# Talos_ES_CTRL_Schematics.net
KiCad netlist of a schematic drawn in EasyEDA
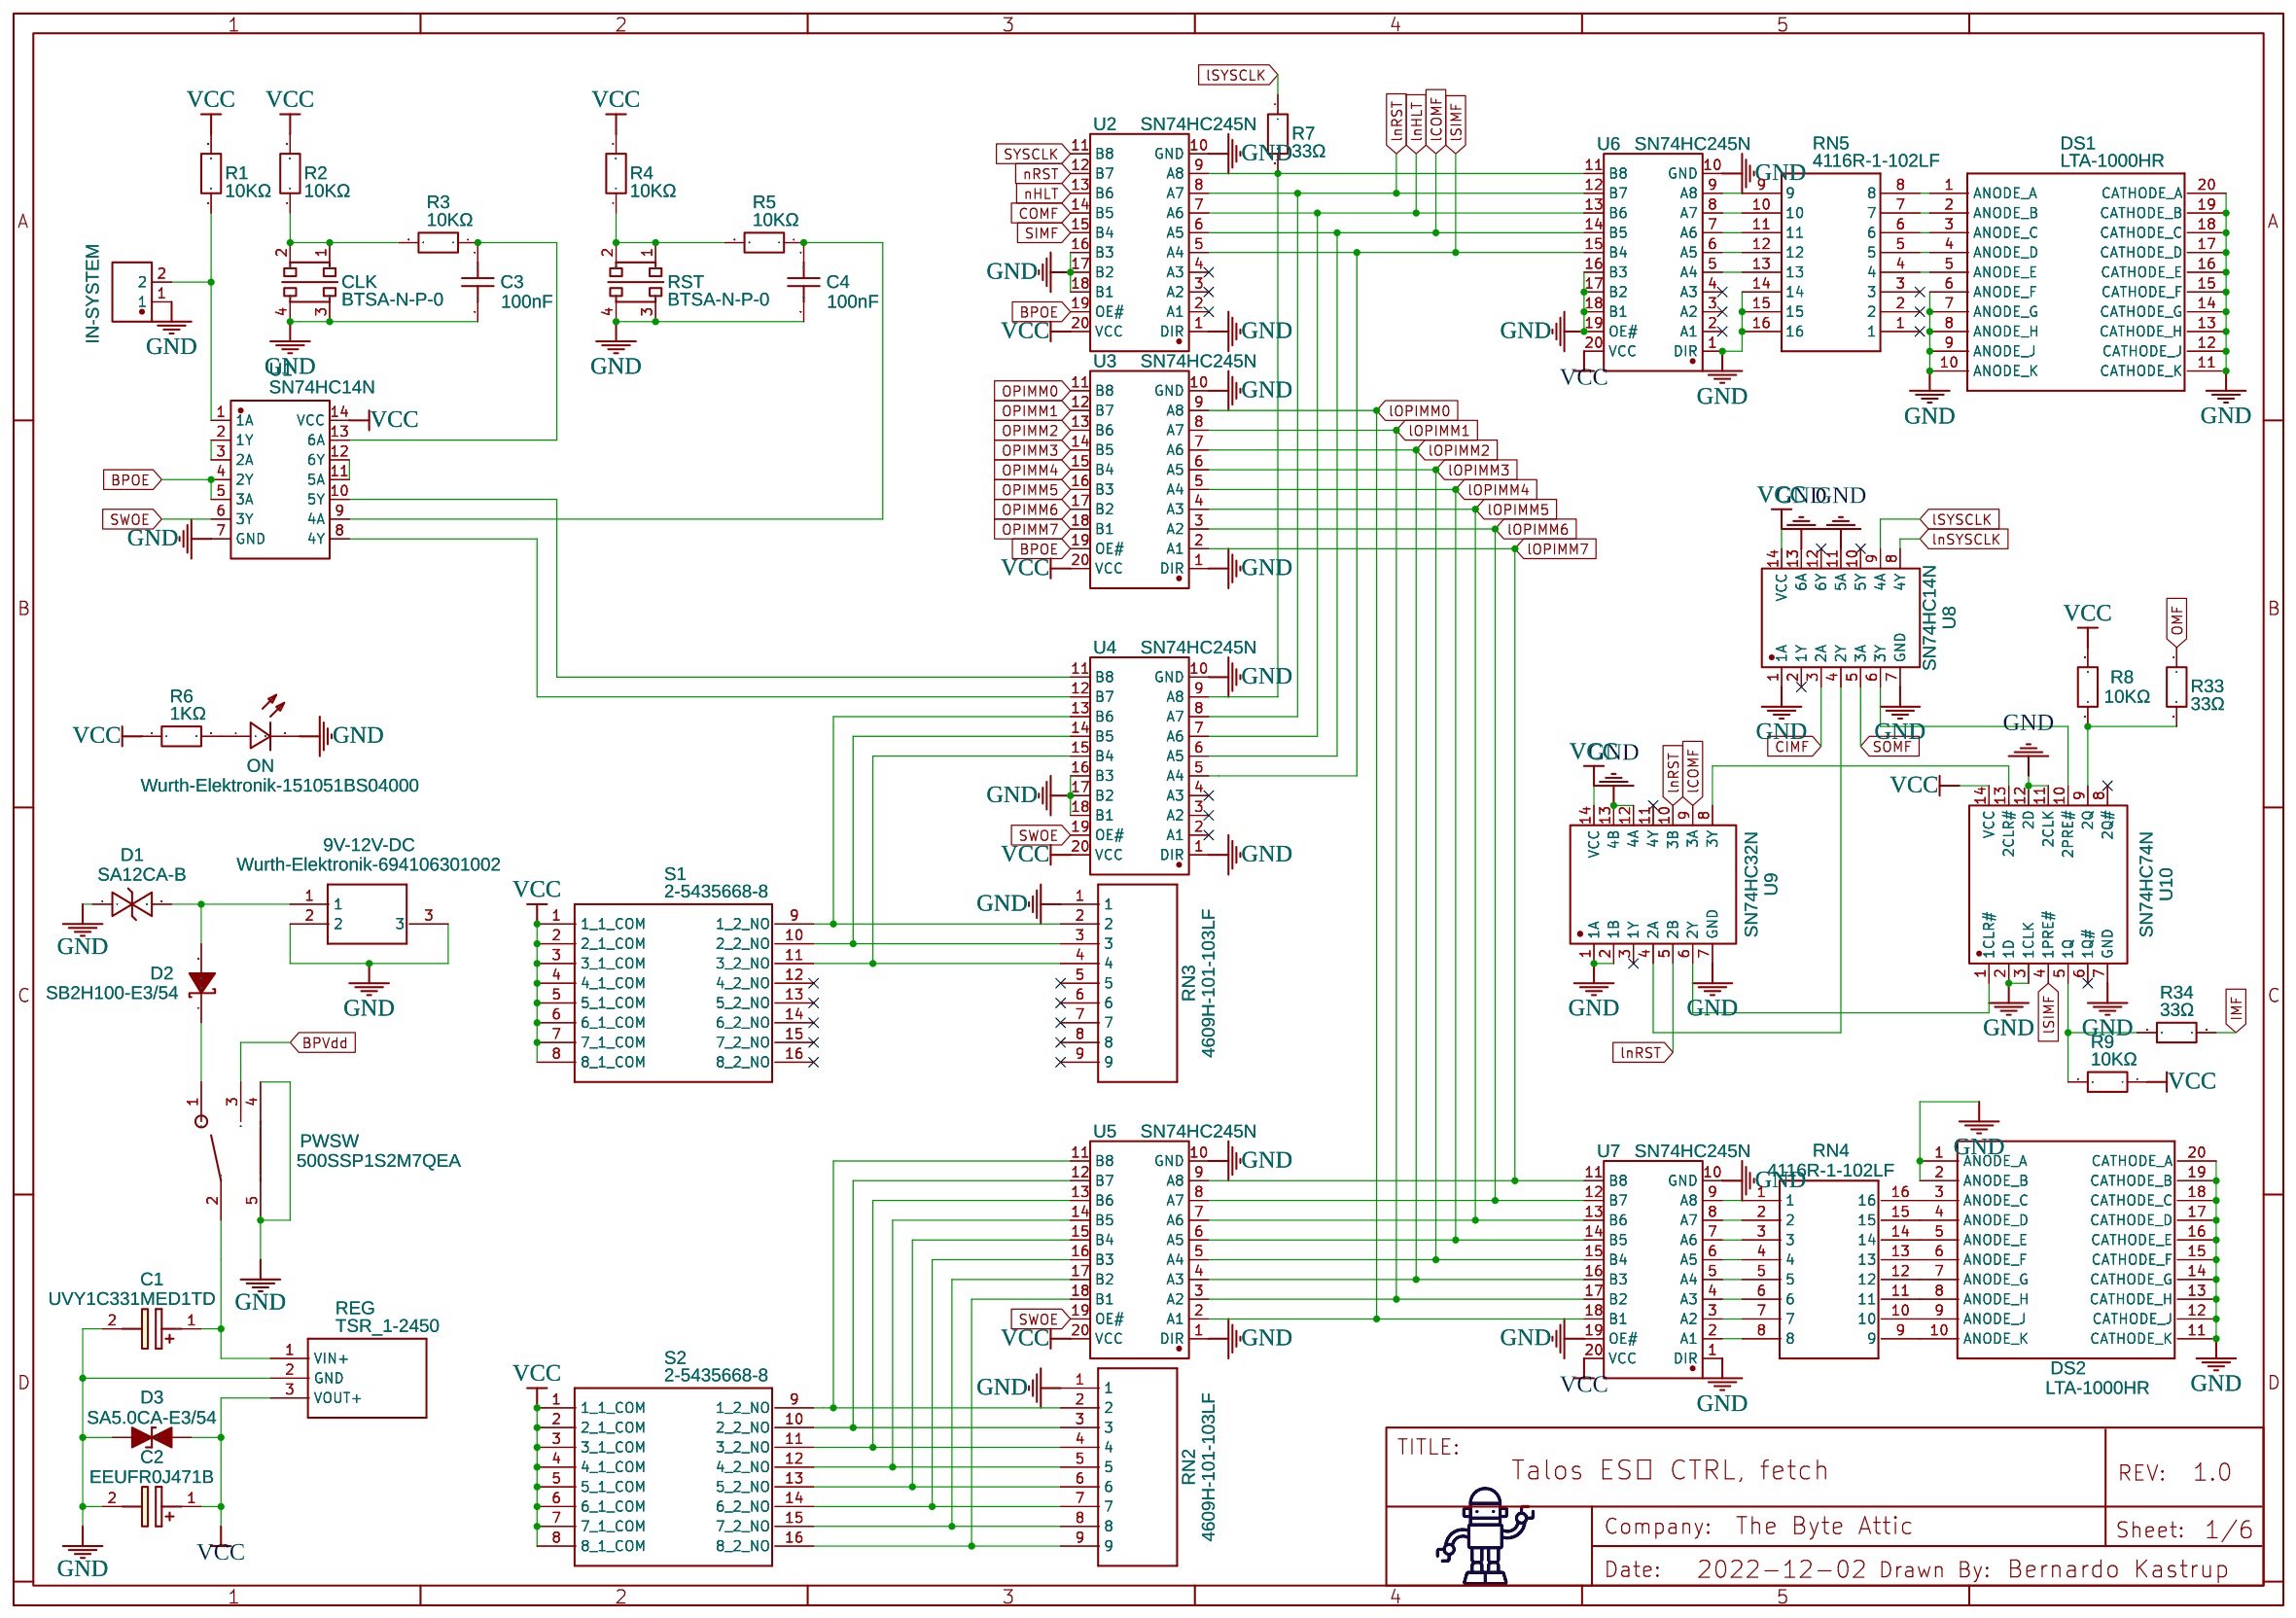
[diagram p0: FETCH]
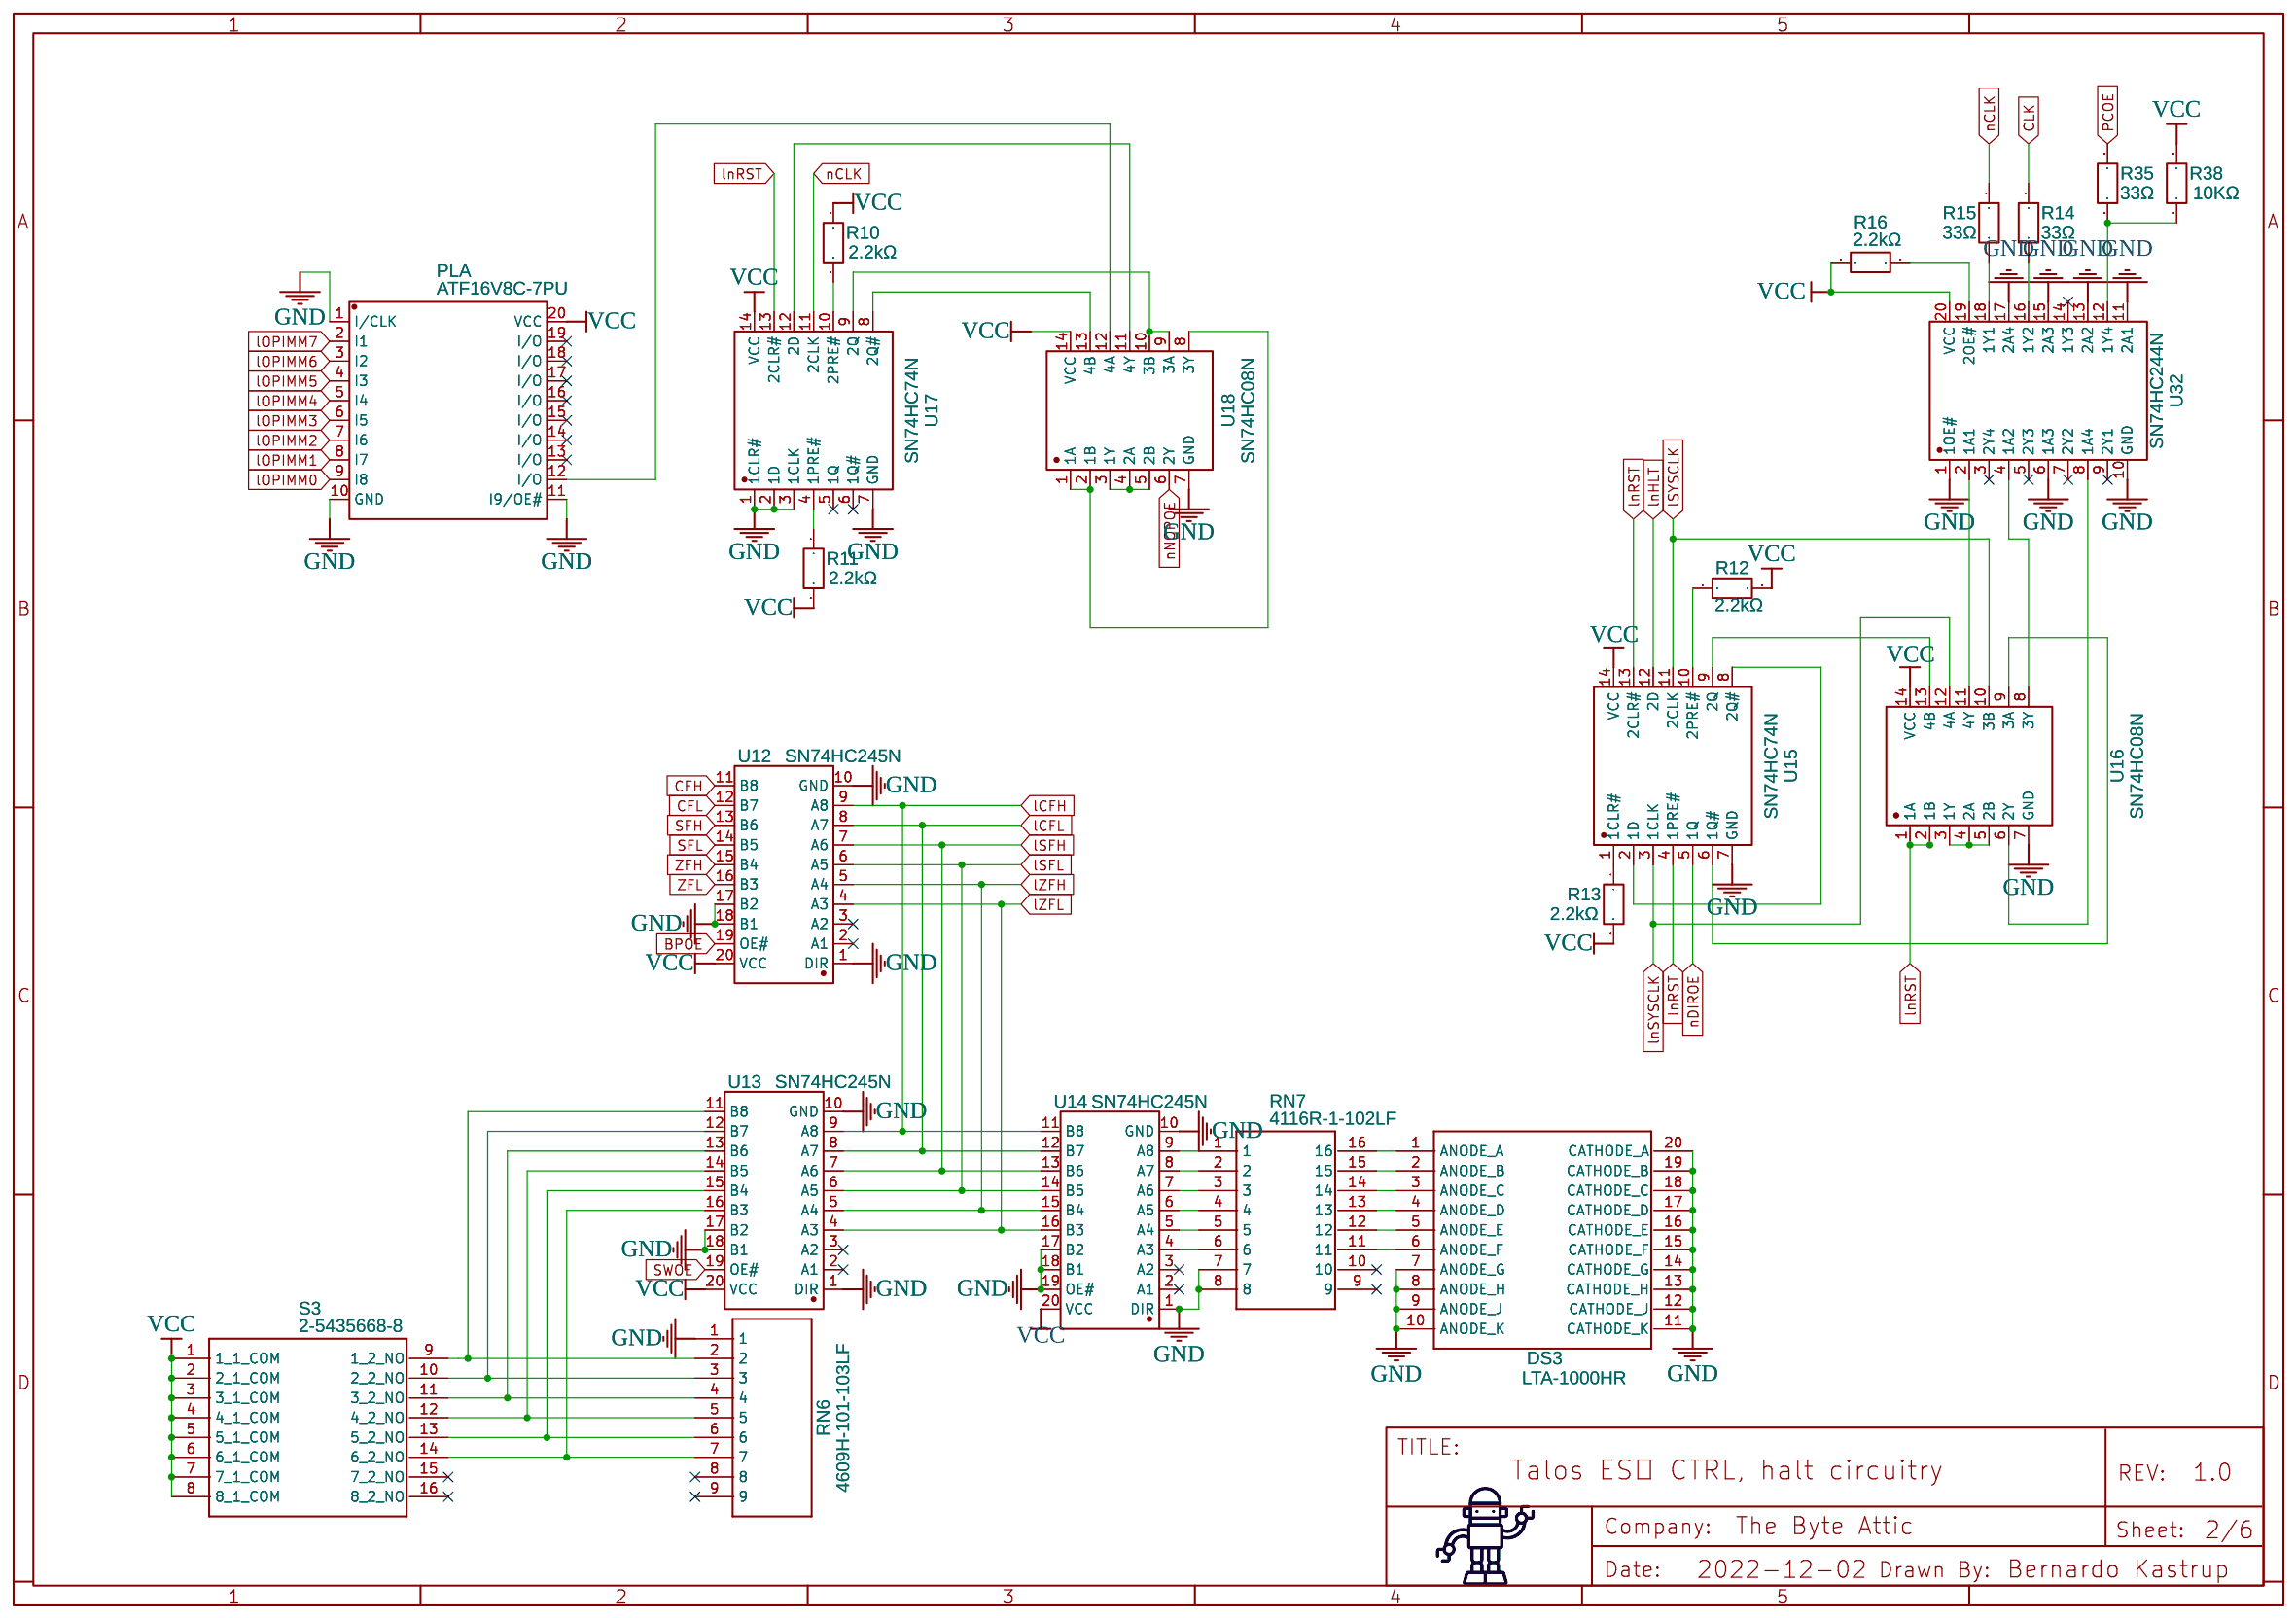
[diagram p1: HALT]
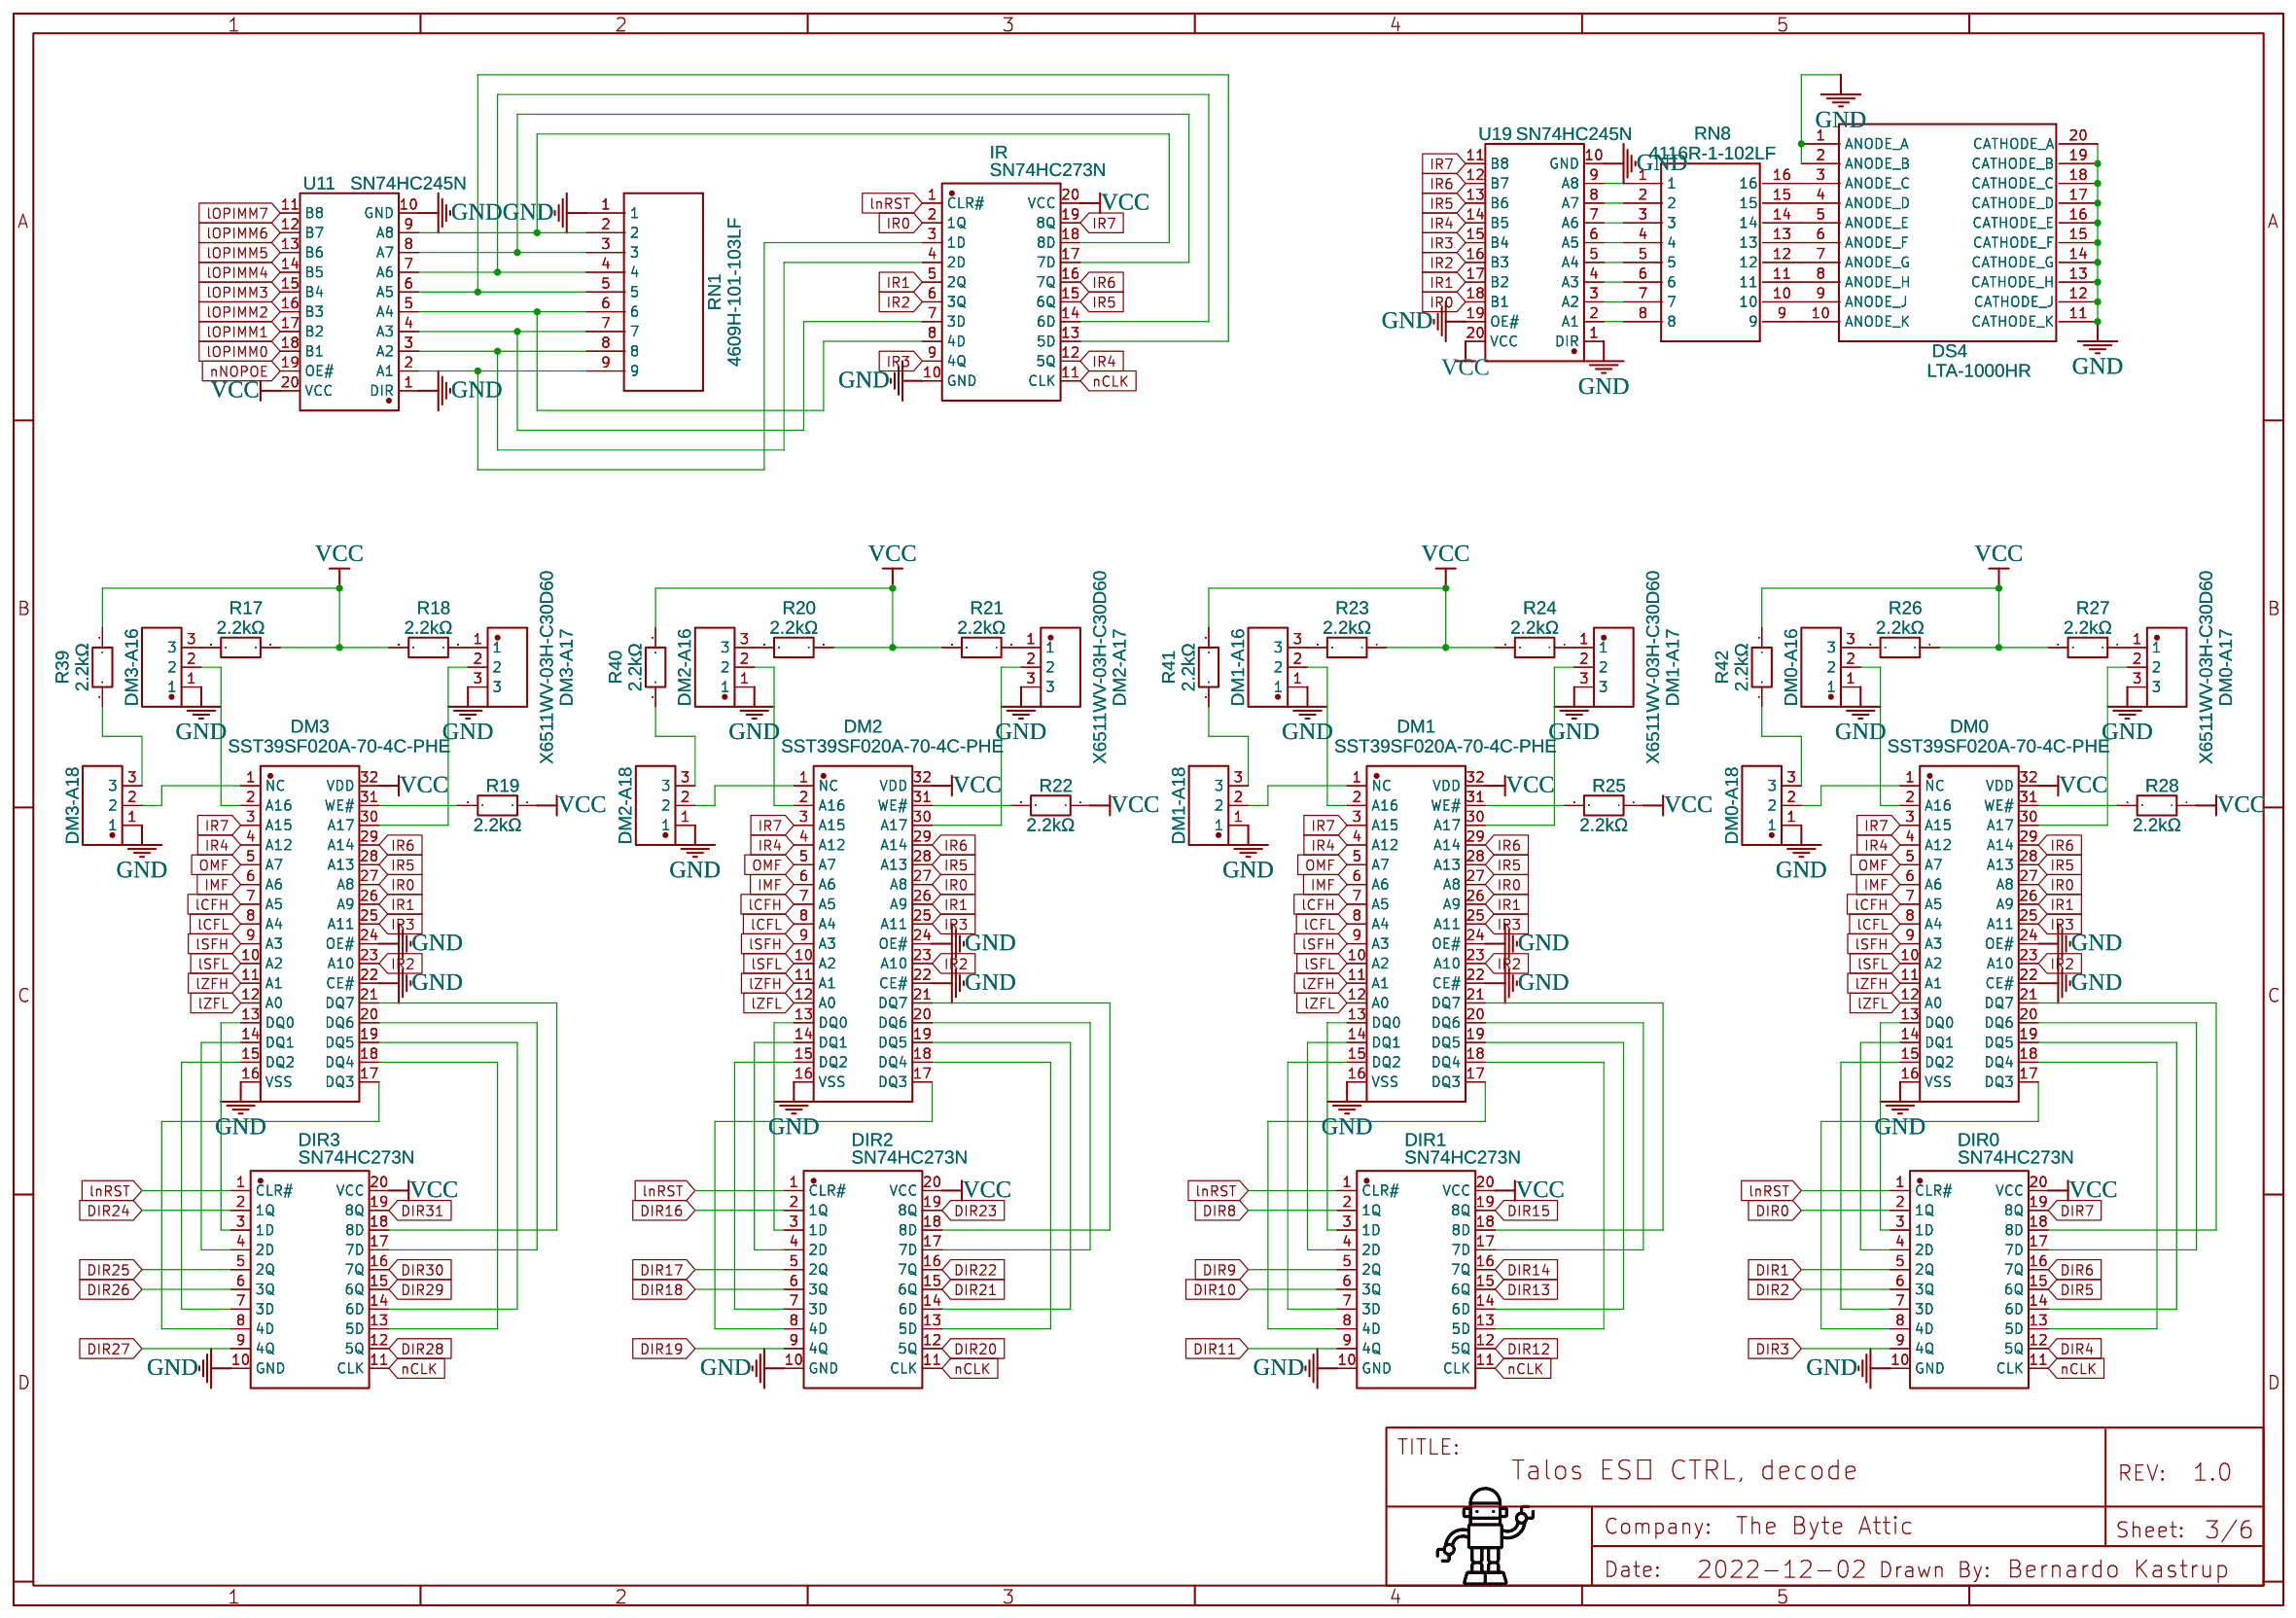
[diagram p2: DECODE]
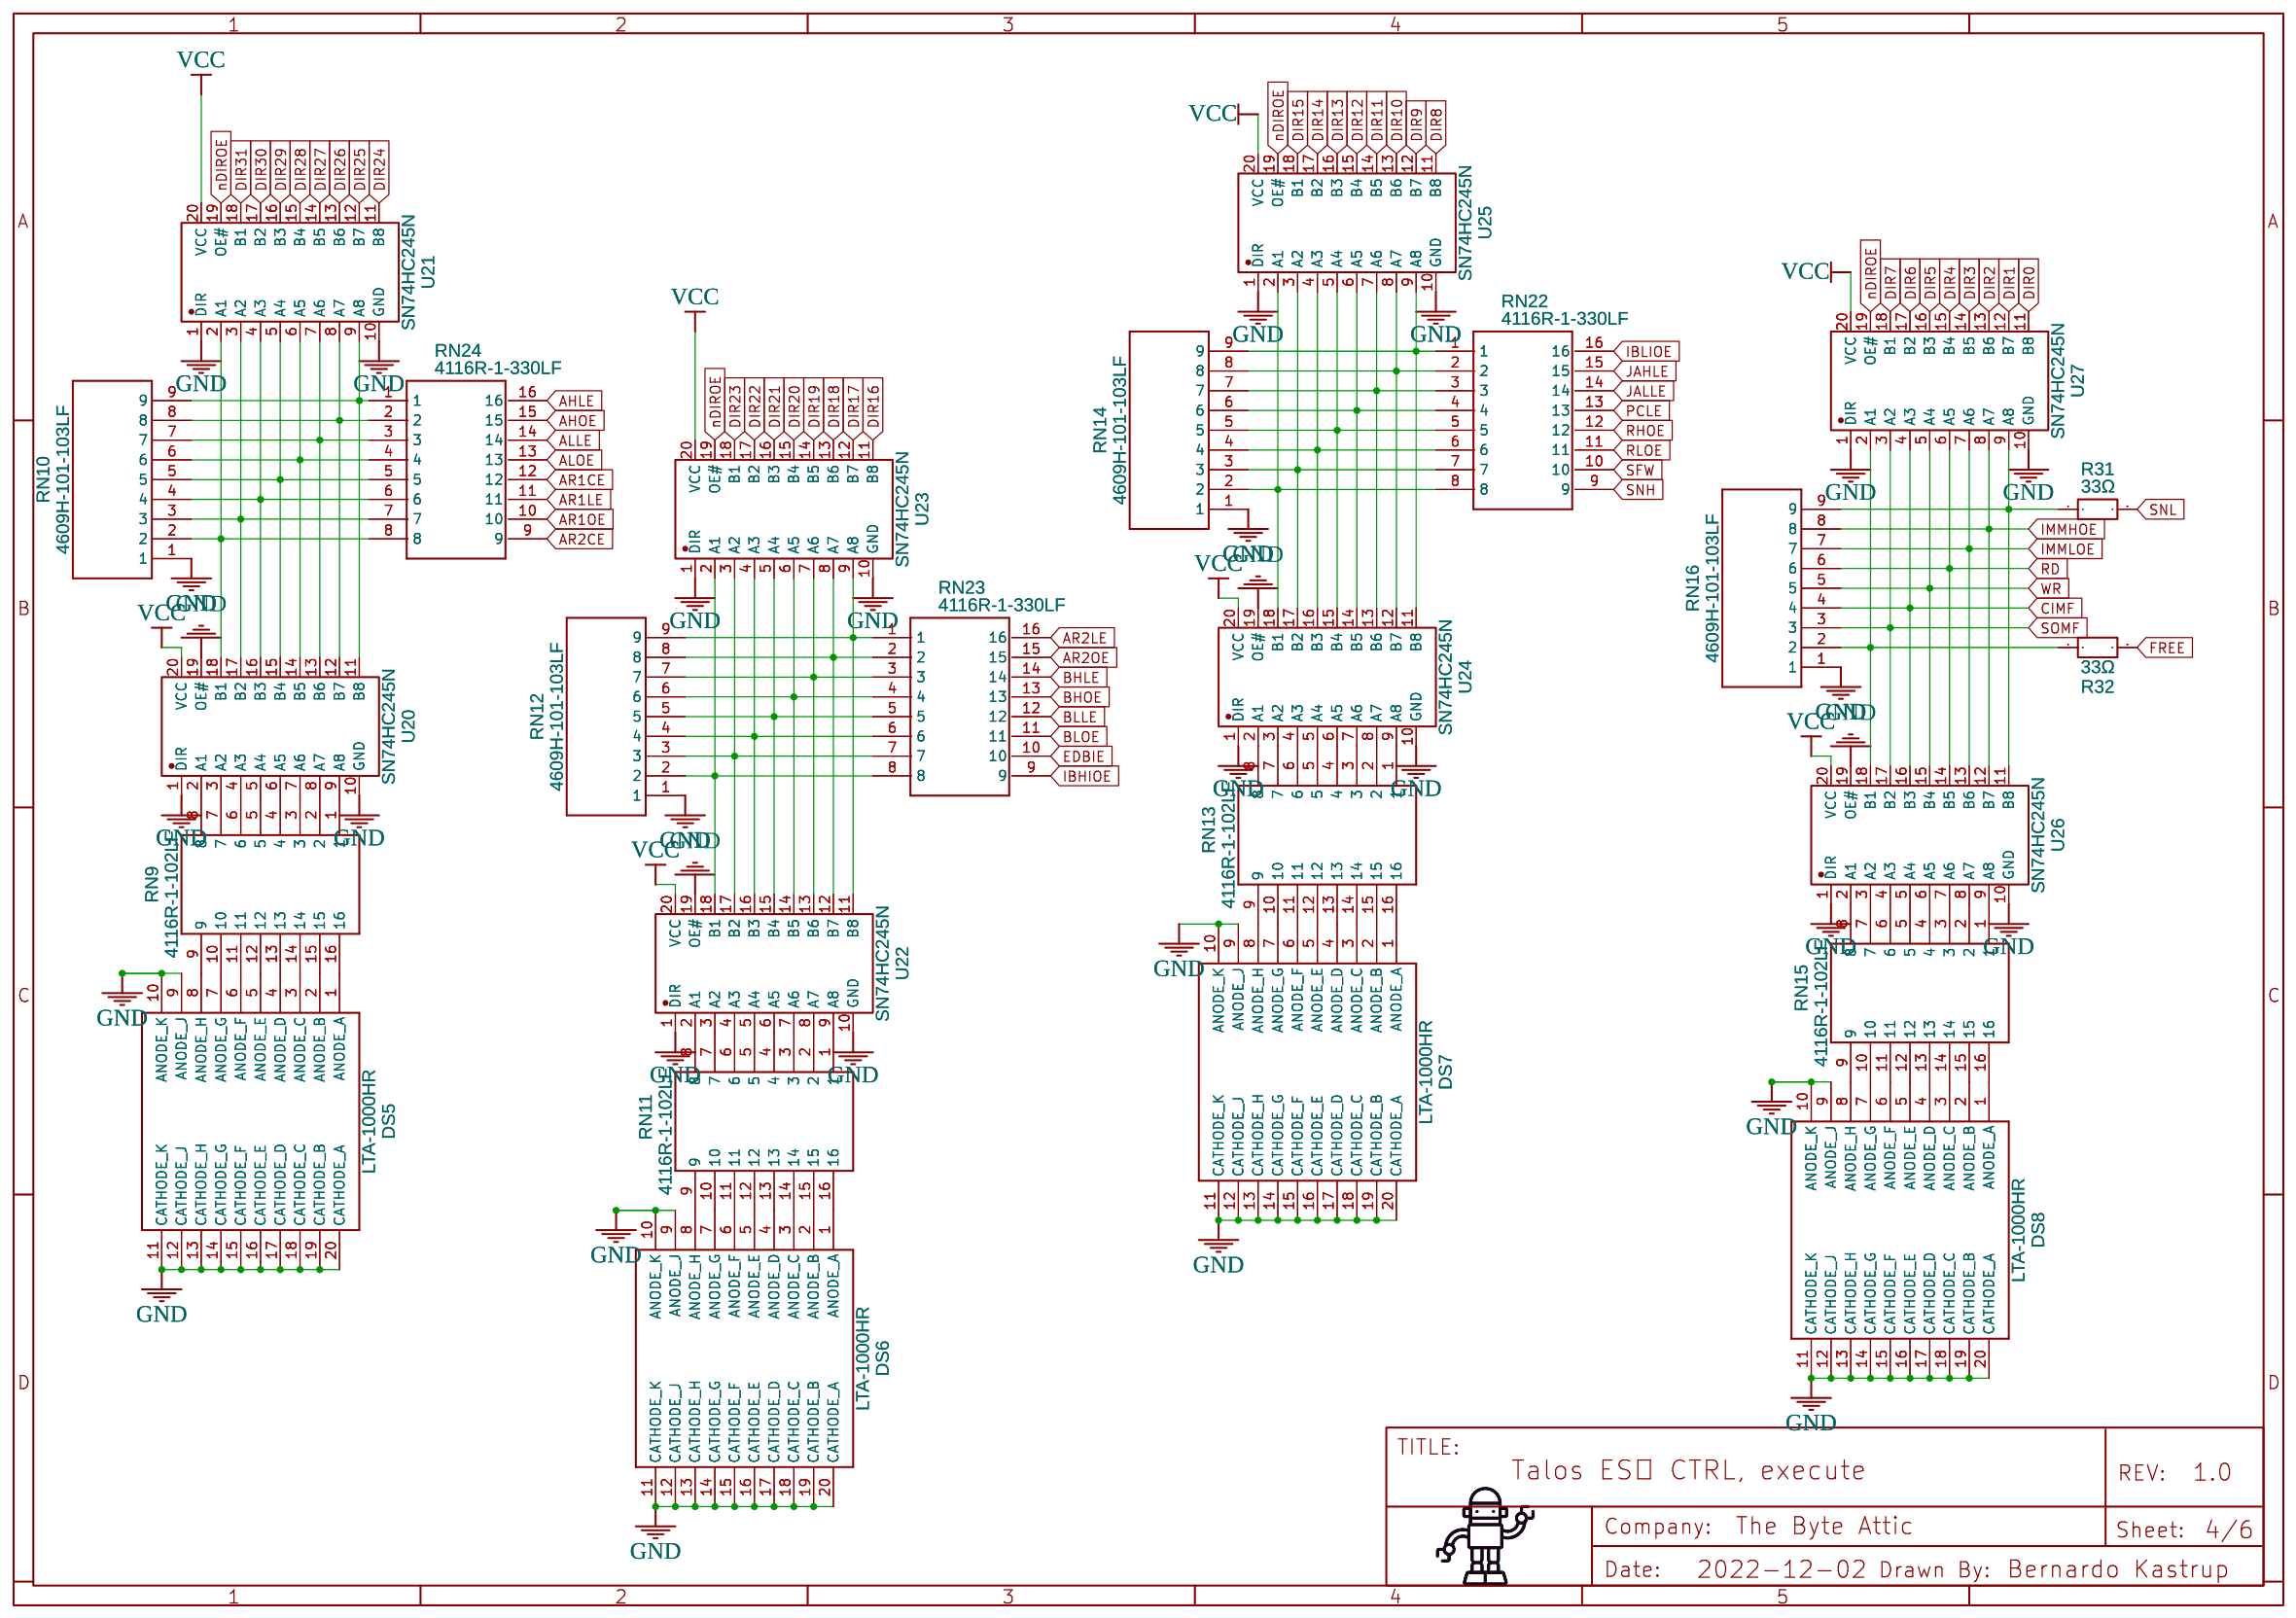
[diagram p3: EXECUTE]
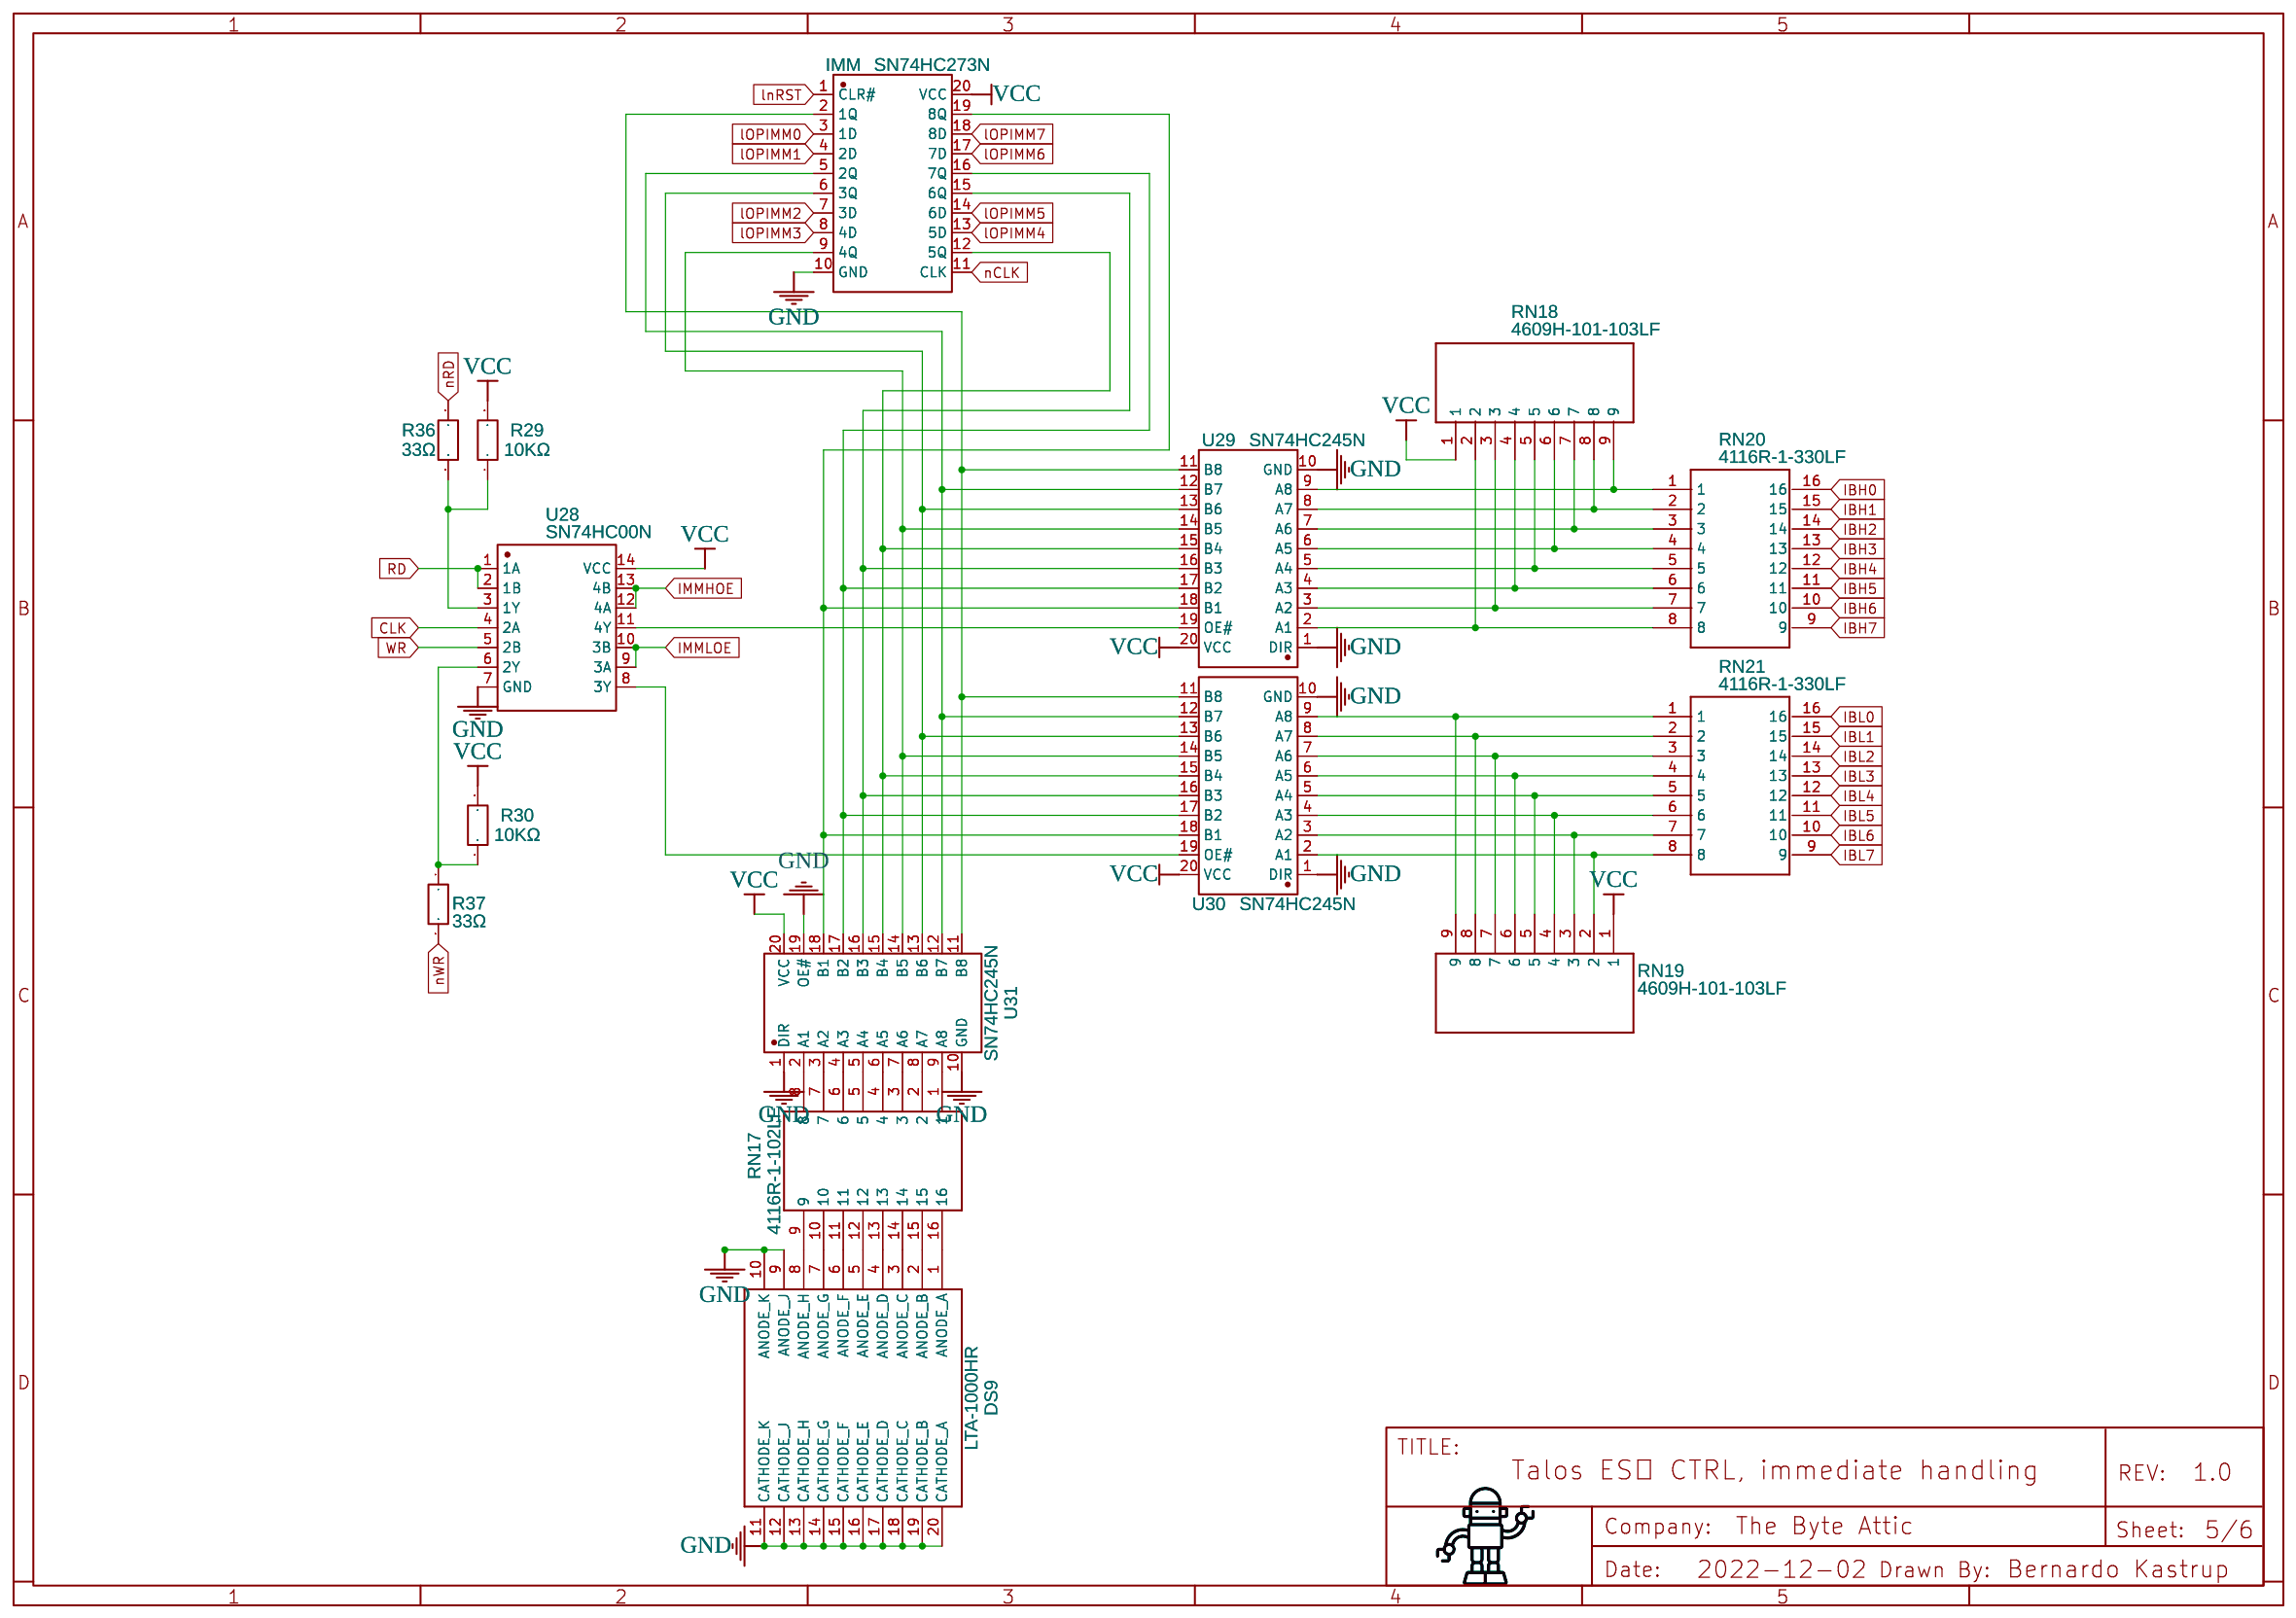
[diagram p4: IMMEDIATE]
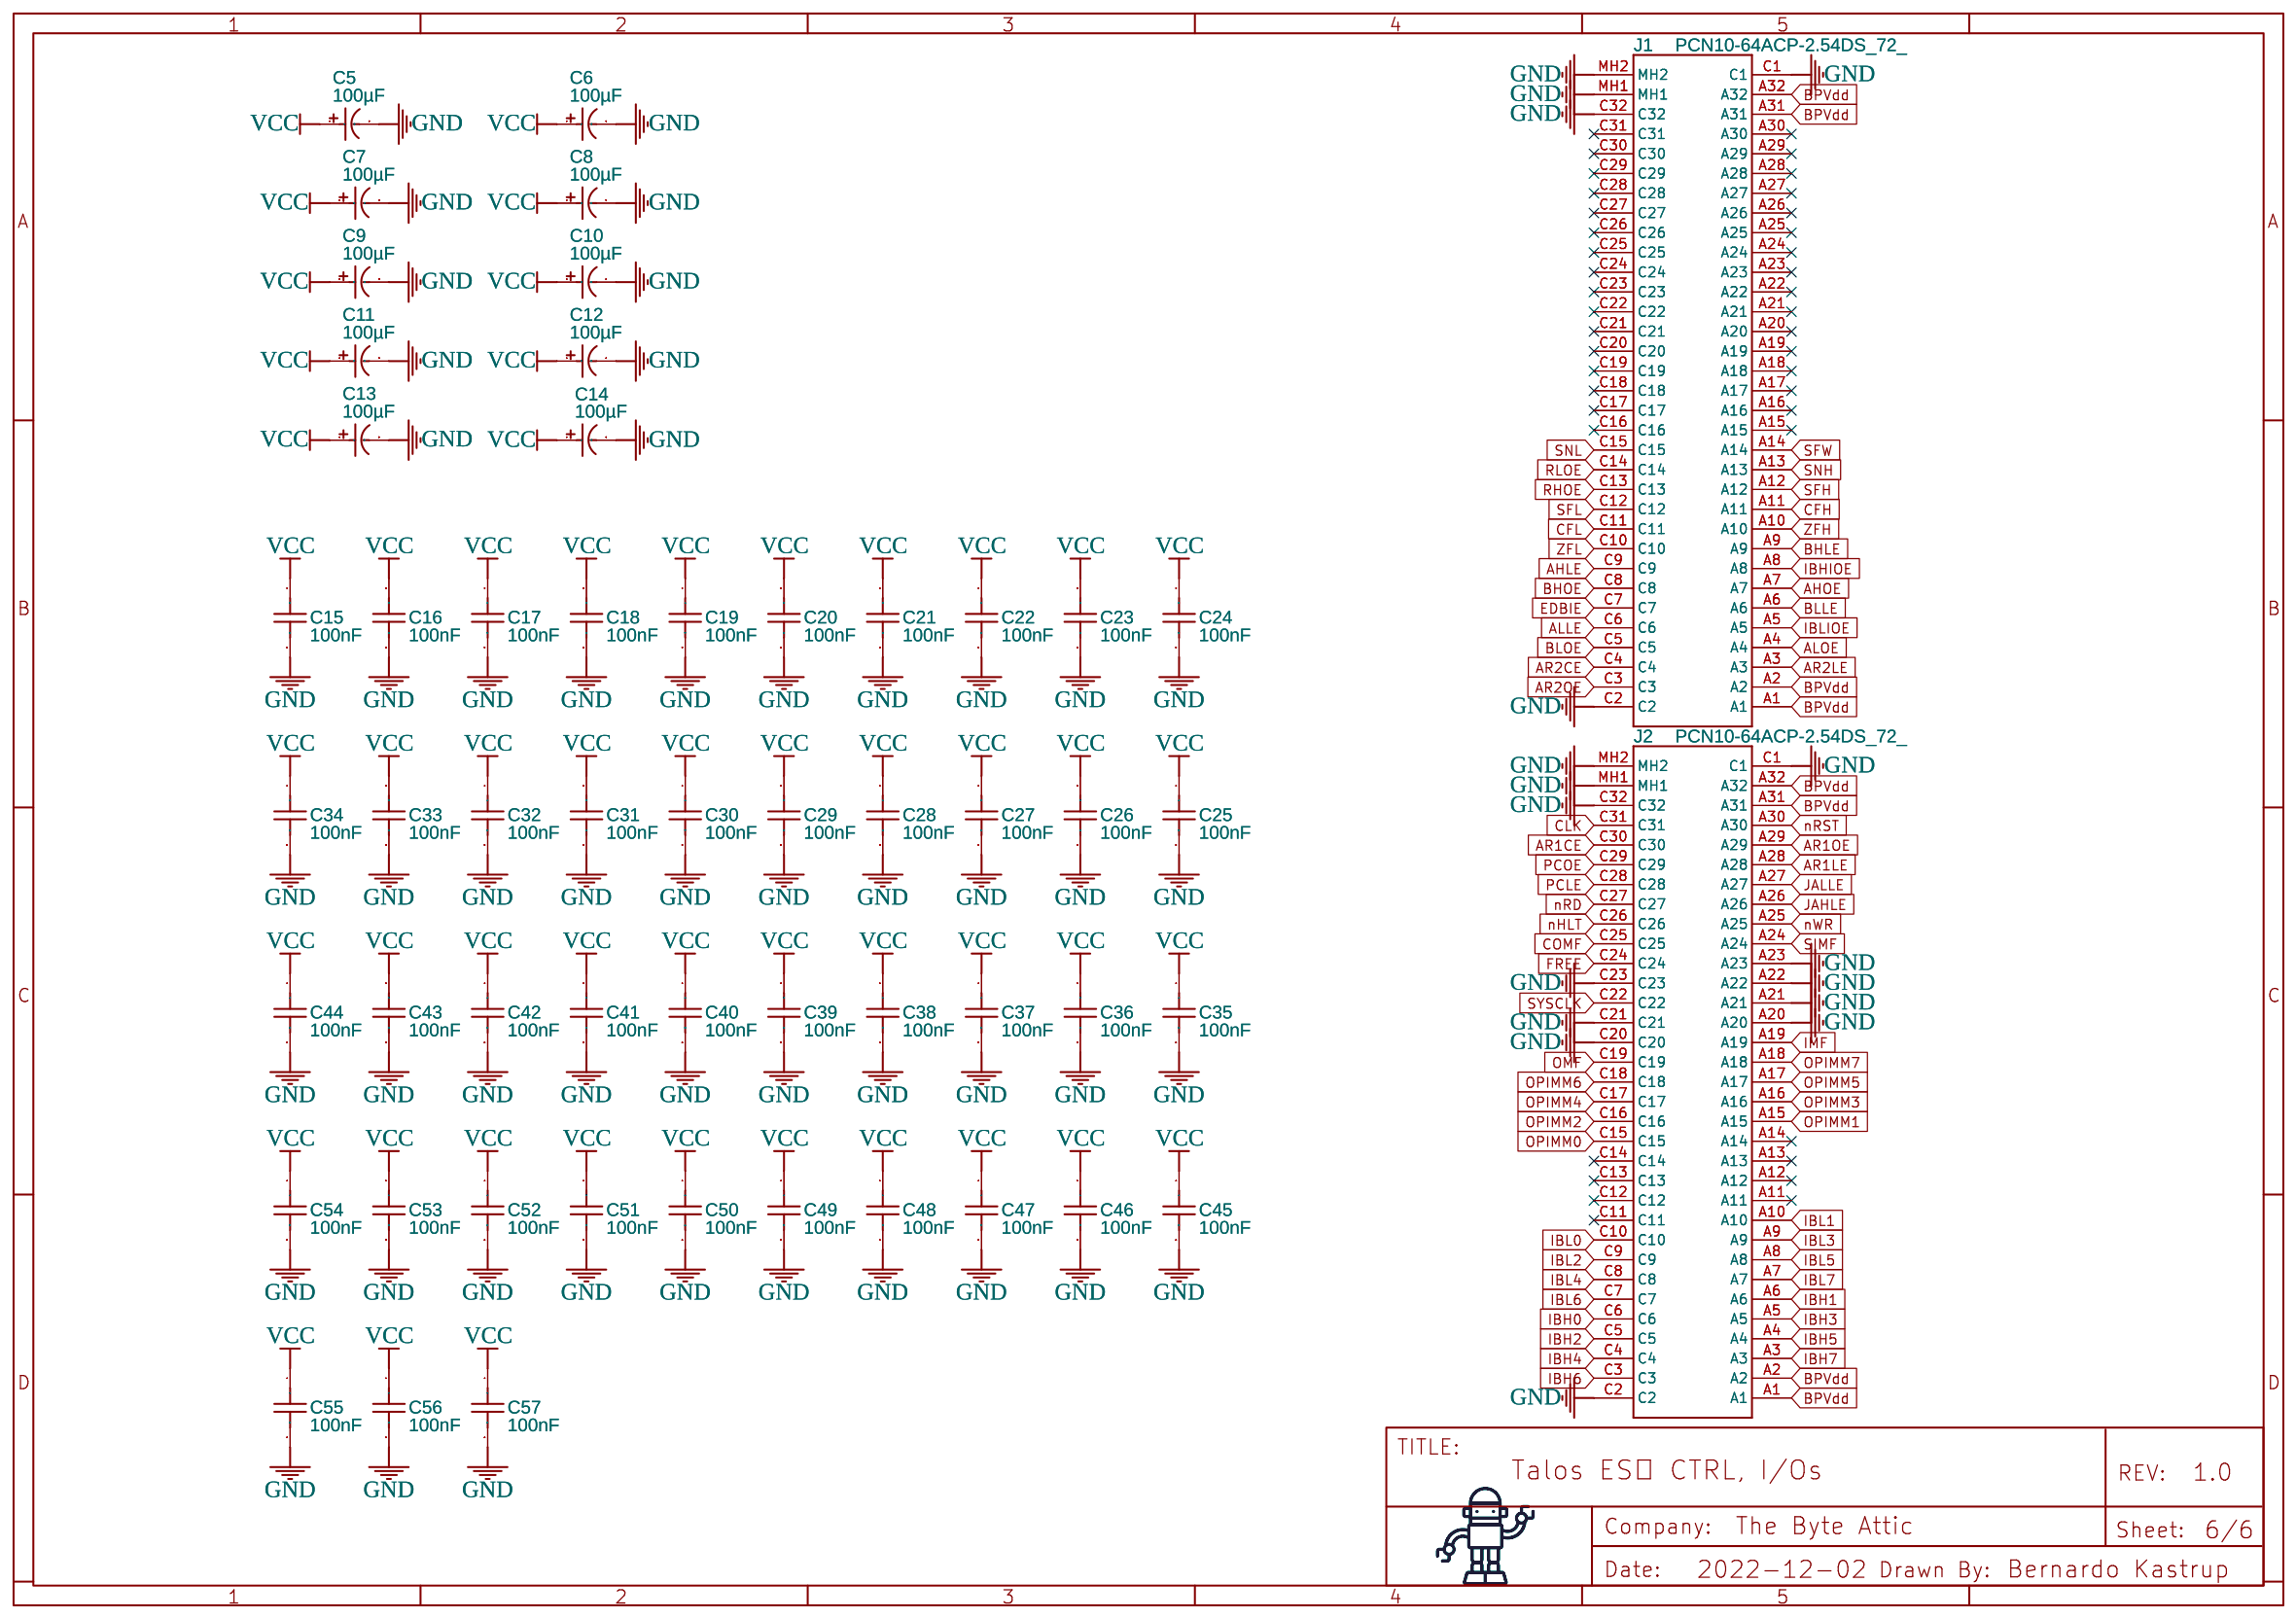
[diagram p5: I/O]

(export (version "E")
  (design (tool "Eeschema 10.0.6"))
  (components
    (comp (ref "9V-12V-DC")
      (value "Wurth-Elektronik-694106301002")
      (libsource (lib "") (part "KLDX-0202-AP-LT"))
    )
    (comp (ref "C1")
      (value "UVY1C331MED1TD")
      (fields (field (name "BOM_Supplier Part") "647-UVY1C331MED1TD"))
      (libsource (lib "") (part "EEUFR0J471B"))
    )
    (comp (ref "C2")
      (value "EEUFR0J471B")
      (fields
        (field (name "BOM_Manufacturer Part") "EEU-FR0J471B")
        (field (name "BOM_Supplier Part") "667-EEU-FR0J471B")
      )
      (libsource (lib "") (part "EEUFR0J471B"))
    )
    (comp (ref "C3")
      (value "100nF")
      (fields
        (field (name "BOM_Manufacturer Part") "K104M15X7RF5TH5")
        (field (name "BOM_Supplier Part") "C499573")
      )
      (libsource (lib "") (part "K104M15X7RF5TH5"))
    )
    (comp (ref "C4")
      (value "100nF")
      (fields
        (field (name "BOM_Manufacturer Part") "K104M15X7RF5TH5")
        (field (name "BOM_Supplier Part") "C499573")
      )
      (libsource (lib "") (part "K104M15X7RF5TH5"))
    )
    (comp (ref "CLK")
      (value "BTSA-N-P-0")
      (fields (field (name "BOM_Supplier Part") "C2693689"))
      (libsource (lib "") (part "BTSA-N-P-0_1"))
    )
    (comp (ref "D1")
      (value "SA12CA-B")
      (fields (field (name "BOM_Supplier Part") "C1666306"))
      (libsource (lib "") (part "SA12CA-B"))
    )
    (comp (ref "D2")
      (value "SB2H100-E3/54")
      (fields (field (name "BOM_Manufacturer Part") "1N5818G") (field (name "BOM_Supplier Part") "C232462"))
      (libsource (lib "") (part "1N5818G"))
    )
    (comp (ref "D3")
      (value "SA5.0CA-E3/54")
      (fields (field (name "BOM_Supplier Part") "C1973200"))
      (libsource (lib "") (part "SA5.0CA-E3/54"))
    )
    (comp (ref "DS1") (value "LTA-1000HR") (libsource (lib "") (part "LTA-1000HR")))
    (comp (ref "DS2") (value "LTA-1000HR") (libsource (lib "") (part "LTA-1000HR")))
    (comp (ref "IN-SYSTEM")
      (value "22-28-4020")
      (fields (field (name "BOM_Supplier Part") "C234182"))
      (libsource (lib "") (part "22-28-4020"))
    )
    (comp (ref "ON")
      (value "Wurth-Elektronik-151051BS04000")
      (fields
        (field (name "BOM_Manufacturer Part") "TJ-L3FYWGHRMFCSFLC2R-A5")
        (field (name "BOM_Supplier Part") "C331041")
      )
      (libsource (lib "") (part "TJ-L3FYWGHRMFCSFLC2R-A5"))
    )
    (comp (ref "PWSW")
      (value "500SSP1S2M7QEA")
      (fields (field (name "BOM_Supplier Part") "C273380"))
      (libsource (lib "") (part "500SSP1S2M7QEA"))
    )
    (comp (ref "R1")
      (value "10KΩ")
      (fields
        (field (name "BOM_Manufacturer Part") "MF1/4W-1Ω±1%T52")
        (field (name "BOM_Supplier Part") "C713947")
      )
      (libsource (lib "") (part "MF1/4W-1Ω±1%T52_1"))
    )
    (comp (ref "R2")
      (value "10KΩ")
      (fields
        (field (name "BOM_Manufacturer Part") "MF1/4W-1Ω±1%T52")
        (field (name "BOM_Supplier Part") "C713947")
      )
      (libsource (lib "") (part "MF1/4W-1Ω±1%T52_1"))
    )
    (comp (ref "R3")
      (value "10KΩ")
      (fields
        (field (name "BOM_Manufacturer Part") "MF1/4W-1Ω±1%T52")
        (field (name "BOM_Supplier Part") "C713947")
      )
      (libsource (lib "") (part "MF1/4W-1Ω±1%T52_3"))
    )
    (comp (ref "R4")
      (value "10KΩ")
      (fields
        (field (name "BOM_Manufacturer Part") "MF1/4W-1Ω±1%T52")
        (field (name "BOM_Supplier Part") "C713947")
      )
      (libsource (lib "") (part "MF1/4W-1Ω±1%T52_1"))
    )
    (comp (ref "R5")
      (value "10KΩ")
      (fields
        (field (name "BOM_Manufacturer Part") "MF1/4W-1Ω±1%T52")
        (field (name "BOM_Supplier Part") "C713947")
      )
      (libsource (lib "") (part "MF1/4W-1Ω±1%T52_3"))
    )
    (comp (ref "R6")
      (value "1KΩ")
      (fields
        (field (name "BOM_Manufacturer Part") "YR1B1K0CC")
        (field (name "BOM_Supplier Part") "C1364308")
      )
      (libsource (lib "") (part "YR1B1K0CC"))
    )
    (comp (ref "R7") (value "33Ω") (libsource (lib "") (part "MF1/4W-1Ω±1%T52")))
    (comp (ref "R8")
      (value "10KΩ")
      (fields
        (field (name "BOM_Manufacturer Part") "MF1/4W-1Ω±1%T52")
        (field (name "BOM_Supplier Part") "C713947")
      )
      (libsource (lib "") (part "MF1/4W-1Ω±1%T52_1"))
    )
    (comp (ref "R9")
      (value "10KΩ")
      (fields
        (field (name "BOM_Manufacturer Part") "MF1/4W-1Ω±1%T52")
        (field (name "BOM_Supplier Part") "C713947")
      )
      (libsource (lib "") (part "MF1/4W-1Ω±1%T52_3"))
    )
    (comp (ref "R33") (value "33Ω") (libsource (lib "") (part "MF1/4W-1Ω±1%T52")))
    (comp (ref "R34") (value "33Ω") (libsource (lib "") (part "MF1/4W-1Ω±1%T52_2")))
    (comp (ref "REG") (value "TSR_1-2450") (libsource (lib "") (part "TSR_1-2450")))
    (comp (ref "RN2") (value "4609H-101-103LF") (libsource (lib "") (part "4609H-101-103LF")))
    (comp (ref "RN3") (value "4609H-101-103LF") (libsource (lib "") (part "4609H-101-103LF")))
    (comp (ref "RN4") (value "4116R-1-102LF") (libsource (lib "") (part "4116R-1-102LF")))
    (comp (ref "RN5") (value "4116R-1-102LF") (libsource (lib "") (part "4116R-1-102LF_1")))
    (comp (ref "RST")
      (value "BTSA-N-P-0")
      (fields (field (name "BOM_Supplier Part") "C2693689"))
      (libsource (lib "") (part "BTSA-N-P-0"))
    )
    (comp (ref "S1") (value "2-5435668-8") (libsource (lib "") (part "2-5435668-8")))
    (comp (ref "S2") (value "2-5435668-8") (libsource (lib "") (part "2-5435668-8")))
    (comp (ref "U1")
      (value "SN74HC14N")
      (fields (field (name "BOM_Supplier Part") "C2907"))
      (libsource (lib "") (part "SN74HC14N_1"))
    )
    (comp (ref "U2")
      (value "SN74HC245N")
      (fields (field (name "BOM_Supplier Part") "C2899"))
      (libsource (lib "") (part "SN74HC245N"))
    )
    (comp (ref "U3")
      (value "SN74HC245N")
      (fields (field (name "BOM_Supplier Part") "C2899"))
      (libsource (lib "") (part "SN74HC245N"))
    )
    (comp (ref "U4")
      (value "SN74HC245N")
      (fields (field (name "BOM_Supplier Part") "C2899"))
      (libsource (lib "") (part "SN74HC245N"))
    )
    (comp (ref "U5")
      (value "SN74HC245N")
      (fields (field (name "BOM_Supplier Part") "C2899"))
      (libsource (lib "") (part "SN74HC245N"))
    )
    (comp (ref "U6")
      (value "SN74HC245N")
      (fields (field (name "BOM_Supplier Part") "C2899"))
      (libsource (lib "") (part "SN74HC245N"))
    )
    (comp (ref "U7")
      (value "SN74HC245N")
      (fields (field (name "BOM_Supplier Part") "C2899"))
      (libsource (lib "") (part "SN74HC245N"))
    )
    (comp (ref "U8")
      (value "SN74HC14N")
      (fields (field (name "BOM_Supplier Part") "C2907"))
      (libsource (lib "") (part "SN74HC14N"))
    )
    (comp (ref "U9")
      (value "SN74HC32N")
      (fields (field (name "BOM_Supplier Part") "C2894"))
      (libsource (lib "") (part "SN74HC32N"))
    )
    (comp (ref "U10")
      (value "SN74HC74N")
      (fields (field (name "BOM_Supplier Part") "C2895"))
      (libsource (lib "") (part "SN74HC74N"))
    )
    (comp (ref "DS3") (value "LTA-1000HR") (libsource (lib "") (part "LTA-1000HR")))
    (comp (ref "PLA")
      (value "ATF16V8C-7PU")
      (fields (field (name "BOM_Supplier Part") "C613484"))
      (libsource (lib "") (part "ATF16V8C-7PU"))
    )
    (comp (ref "R10")
      (value "2.2kΩ")
      (fields
        (field (name "BOM_Manufacturer Part") "MF1/4W-2.2KΩ±1%T52")
        (field (name "BOM_Supplier Part") "C714002")
      )
      (libsource (lib "") (part "MF1/4W-2.2KΩ±1%T52_1"))
    )
    (comp (ref "R11")
      (value "2.2kΩ")
      (fields
        (field (name "BOM_Manufacturer Part") "MF1/4W-2.2KΩ±1%T52")
        (field (name "BOM_Supplier Part") "C714002")
      )
      (libsource (lib "") (part "MF1/4W-2.2KΩ±1%T52_1"))
    )
    (comp (ref "R12")
      (value "2.2kΩ")
      (fields
        (field (name "BOM_Manufacturer Part") "MF1/4W-2.2KΩ±1%T52")
        (field (name "BOM_Supplier Part") "C714002")
      )
      (libsource (lib "") (part "MF1/4W-2.2KΩ±1%T52"))
    )
    (comp (ref "R13")
      (value "2.2kΩ")
      (fields
        (field (name "BOM_Manufacturer Part") "MF1/4W-2.2KΩ±1%T52")
        (field (name "BOM_Supplier Part") "C714002")
      )
      (libsource (lib "") (part "MF1/4W-2.2KΩ±1%T52_1"))
    )
    (comp (ref "R14") (value "33Ω") (libsource (lib "") (part "MF1/4W-1Ω±1%T52")))
    (comp (ref "R15") (value "33Ω") (libsource (lib "") (part "MF1/4W-1Ω±1%T52")))
    (comp (ref "R16")
      (value "2.2kΩ")
      (fields
        (field (name "BOM_Manufacturer Part") "MF1/4W-2.2KΩ±1%T52")
        (field (name "BOM_Supplier Part") "C714002")
      )
      (libsource (lib "") (part "MF1/4W-2.2KΩ±1%T52"))
    )
    (comp (ref "R35") (value "33Ω") (libsource (lib "") (part "MF1/4W-1Ω±1%T52_1")))
    (comp (ref "R38")
      (value "10KΩ")
      (fields
        (field (name "BOM_Manufacturer Part") "MF1/4W-1Ω±1%T52")
        (field (name "BOM_Supplier Part") "C713947")
      )
      (libsource (lib "") (part "MF1/4W-1Ω±1%T52_1"))
    )
    (comp (ref "RN6") (value "4609H-101-103LF") (libsource (lib "") (part "4609H-101-103LF")))
    (comp (ref "RN7") (value "4116R-1-102LF") (libsource (lib "") (part "4116R-1-102LF")))
    (comp (ref "S3") (value "2-5435668-8") (libsource (lib "") (part "2-5435668-8")))
    (comp (ref "U12")
      (value "SN74HC245N")
      (fields (field (name "BOM_Supplier Part") "C2899"))
      (libsource (lib "") (part "SN74HC245N"))
    )
    (comp (ref "U13")
      (value "SN74HC245N")
      (fields (field (name "BOM_Supplier Part") "C2899"))
      (libsource (lib "") (part "SN74HC245N"))
    )
    (comp (ref "U14")
      (value "SN74HC245N")
      (fields (field (name "BOM_Supplier Part") "C2899"))
      (libsource (lib "") (part "SN74HC245N"))
    )
    (comp (ref "U15")
      (value "SN74HC74N")
      (fields (field (name "BOM_Supplier Part") "C2895"))
      (libsource (lib "") (part "SN74HC74N"))
    )
    (comp (ref "U16")
      (value "SN74HC08N")
      (fields (field (name "BOM_Supplier Part") "C2887"))
      (libsource (lib "") (part "SN74HC08N"))
    )
    (comp (ref "U17")
      (value "SN74HC74N")
      (fields (field (name "BOM_Supplier Part") "C2895"))
      (libsource (lib "") (part "SN74HC74N"))
    )
    (comp (ref "U18")
      (value "SN74HC08N")
      (fields (field (name "BOM_Supplier Part") "C2887"))
      (libsource (lib "") (part "SN74HC08N"))
    )
    (comp (ref "U32")
      (value "SN74HC244N")
      (fields (field (name "BOM_Supplier Part") "C2912"))
      (libsource (lib "") (part "SN74HC244N"))
    )
    (comp (ref "DIR0")
      (value "SN74HC273N")
      (fields (field (name "BOM_Supplier Part") "C5238"))
      (libsource (lib "") (part "SN74HC273N_1"))
    )
    (comp (ref "DIR1")
      (value "SN74HC273N")
      (fields (field (name "BOM_Supplier Part") "C5238"))
      (libsource (lib "") (part "SN74HC273N_1"))
    )
    (comp (ref "DIR2")
      (value "SN74HC273N")
      (fields (field (name "BOM_Supplier Part") "C5238"))
      (libsource (lib "") (part "SN74HC273N_1"))
    )
    (comp (ref "DIR3")
      (value "SN74HC273N")
      (fields (field (name "BOM_Supplier Part") "C5238"))
      (libsource (lib "") (part "SN74HC273N_1"))
    )
    (comp (ref "DM0")
      (value "SST39SF020A-70-4C-PHE")
      (fields (field (name "BOM_Supplier Part") "C643681"))
      (libsource (lib "") (part "SST39SF020A-70-4C-PHE"))
    )
    (comp (ref "DM0-A16")
      (value "X6511WV-03H-C30D60")
      (fields (field (name "BOM_Supplier Part") "C706875"))
      (libsource (lib "") (part "X6511WV-03H-C30D60_1"))
    )
    (comp (ref "DM0-A17")
      (value "X6511WV-03H-C30D60")
      (fields (field (name "BOM_Supplier Part") "C706875"))
      (libsource (lib "") (part "X6511WV-03H-C30D60_6"))
    )
    (comp (ref "DM0-A18")
      (value "X6511WV-03H-C30D60")
      (fields (field (name "BOM_Supplier Part") "C706875"))
      (libsource (lib "") (part "X6511WV-03H-C30D60_1"))
    )
    (comp (ref "DM1")
      (value "SST39SF020A-70-4C-PHE")
      (fields (field (name "BOM_Supplier Part") "C643681"))
      (libsource (lib "") (part "SST39SF020A-70-4C-PHE"))
    )
    (comp (ref "DM1-A16")
      (value "X6511WV-03H-C30D60")
      (fields (field (name "BOM_Supplier Part") "C706875"))
      (libsource (lib "") (part "X6511WV-03H-C30D60_2"))
    )
    (comp (ref "DM1-A17")
      (value "X6511WV-03H-C30D60")
      (fields (field (name "BOM_Supplier Part") "C706875"))
      (libsource (lib "") (part "X6511WV-03H-C30D60_5"))
    )
    (comp (ref "DM1-A18")
      (value "X6511WV-03H-C30D60")
      (fields (field (name "BOM_Supplier Part") "C706875"))
      (libsource (lib "") (part "X6511WV-03H-C30D60_2"))
    )
    (comp (ref "DM2")
      (value "SST39SF020A-70-4C-PHE")
      (fields (field (name "BOM_Supplier Part") "C643681"))
      (libsource (lib "") (part "SST39SF020A-70-4C-PHE"))
    )
    (comp (ref "DM2-A16")
      (value "X6511WV-03H-C30D60")
      (fields (field (name "BOM_Supplier Part") "C706875"))
      (libsource (lib "") (part "X6511WV-03H-C30D60_4"))
    )
    (comp (ref "DM2-A17")
      (value "X6511WV-03H-C30D60")
      (fields (field (name "BOM_Supplier Part") "C706875"))
      (libsource (lib "") (part "X6511WV-03H-C30D60_7"))
    )
    (comp (ref "DM2-A18")
      (value "X6511WV-03H-C30D60")
      (fields (field (name "BOM_Supplier Part") "C706875"))
      (libsource (lib "") (part "X6511WV-03H-C30D60_4"))
    )
    (comp (ref "DM3")
      (value "SST39SF020A-70-4C-PHE")
      (fields (field (name "BOM_Supplier Part") "C643681"))
      (libsource (lib "") (part "SST39SF020A-70-4C-PHE"))
    )
    (comp (ref "DM3-A16")
      (value "X6511WV-03H-C30D60")
      (fields (field (name "BOM_Supplier Part") "C706875"))
      (libsource (lib "") (part "X6511WV-03H-C30D60"))
    )
    (comp (ref "DM3-A17")
      (value "X6511WV-03H-C30D60")
      (fields (field (name "BOM_Supplier Part") "C706875"))
      (libsource (lib "") (part "X6511WV-03H-C30D60_3"))
    )
    (comp (ref "DM3-A18")
      (value "X6511WV-03H-C30D60")
      (fields (field (name "BOM_Supplier Part") "C706875"))
      (libsource (lib "") (part "X6511WV-03H-C30D60"))
    )
    (comp (ref "DS4") (value "LTA-1000HR") (libsource (lib "") (part "LTA-1000HR")))
    (comp (ref "IR")
      (value "SN74HC273N")
      (fields (field (name "BOM_Supplier Part") "C5238"))
      (libsource (lib "") (part "SN74HC273N"))
    )
    (comp (ref "R17")
      (value "2.2kΩ")
      (fields
        (field (name "BOM_Manufacturer Part") "MF1/4W-2.2KΩ±1%T52")
        (field (name "BOM_Supplier Part") "C714002")
      )
      (libsource (lib "") (part "MF1/4W-2.2KΩ±1%T52_1"))
    )
    (comp (ref "R18")
      (value "2.2kΩ")
      (fields
        (field (name "BOM_Manufacturer Part") "MF1/4W-2.2KΩ±1%T52")
        (field (name "BOM_Supplier Part") "C714002")
      )
      (libsource (lib "") (part "MF1/4W-2.2KΩ±1%T52_1"))
    )
    (comp (ref "R19")
      (value "2.2kΩ")
      (fields
        (field (name "BOM_Manufacturer Part") "MF1/4W-2.2KΩ±1%T52")
        (field (name "BOM_Supplier Part") "C714002")
      )
      (libsource (lib "") (part "MF1/4W-2.2KΩ±1%T52_1"))
    )
    (comp (ref "R20")
      (value "2.2kΩ")
      (fields
        (field (name "BOM_Manufacturer Part") "MF1/4W-2.2KΩ±1%T52")
        (field (name "BOM_Supplier Part") "C714002")
      )
      (libsource (lib "") (part "MF1/4W-2.2KΩ±1%T52_1"))
    )
    (comp (ref "R21")
      (value "2.2kΩ")
      (fields
        (field (name "BOM_Manufacturer Part") "MF1/4W-2.2KΩ±1%T52")
        (field (name "BOM_Supplier Part") "C714002")
      )
      (libsource (lib "") (part "MF1/4W-2.2KΩ±1%T52_1"))
    )
    (comp (ref "R22")
      (value "2.2kΩ")
      (fields
        (field (name "BOM_Manufacturer Part") "MF1/4W-2.2KΩ±1%T52")
        (field (name "BOM_Supplier Part") "C714002")
      )
      (libsource (lib "") (part "MF1/4W-2.2KΩ±1%T52_1"))
    )
    (comp (ref "R23")
      (value "2.2kΩ")
      (fields
        (field (name "BOM_Manufacturer Part") "MF1/4W-2.2KΩ±1%T52")
        (field (name "BOM_Supplier Part") "C714002")
      )
      (libsource (lib "") (part "MF1/4W-2.2KΩ±1%T52_1"))
    )
    (comp (ref "R24")
      (value "2.2kΩ")
      (fields
        (field (name "BOM_Manufacturer Part") "MF1/4W-2.2KΩ±1%T52")
        (field (name "BOM_Supplier Part") "C714002")
      )
      (libsource (lib "") (part "MF1/4W-2.2KΩ±1%T52_1"))
    )
    (comp (ref "R25")
      (value "2.2kΩ")
      (fields
        (field (name "BOM_Manufacturer Part") "MF1/4W-2.2KΩ±1%T52")
        (field (name "BOM_Supplier Part") "C714002")
      )
      (libsource (lib "") (part "MF1/4W-2.2KΩ±1%T52_1"))
    )
    (comp (ref "R26")
      (value "2.2kΩ")
      (fields
        (field (name "BOM_Manufacturer Part") "MF1/4W-2.2KΩ±1%T52")
        (field (name "BOM_Supplier Part") "C714002")
      )
      (libsource (lib "") (part "MF1/4W-2.2KΩ±1%T52_1"))
    )
    (comp (ref "R27")
      (value "2.2kΩ")
      (fields
        (field (name "BOM_Manufacturer Part") "MF1/4W-2.2KΩ±1%T52")
        (field (name "BOM_Supplier Part") "C714002")
      )
      (libsource (lib "") (part "MF1/4W-2.2KΩ±1%T52_1"))
    )
    (comp (ref "R28")
      (value "2.2kΩ")
      (fields
        (field (name "BOM_Manufacturer Part") "MF1/4W-2.2KΩ±1%T52")
        (field (name "BOM_Supplier Part") "C714002")
      )
      (libsource (lib "") (part "MF1/4W-2.2KΩ±1%T52_1"))
    )
    (comp (ref "R39")
      (value "2.2kΩ")
      (fields
        (field (name "BOM_Manufacturer Part") "MF1/4W-2.2KΩ±1%T52")
        (field (name "BOM_Supplier Part") "C714002")
      )
      (libsource (lib "") (part "MF1/4W-2.2KΩ±1%T52"))
    )
    (comp (ref "R40")
      (value "2.2kΩ")
      (fields
        (field (name "BOM_Manufacturer Part") "MF1/4W-2.2KΩ±1%T52")
        (field (name "BOM_Supplier Part") "C714002")
      )
      (libsource (lib "") (part "MF1/4W-2.2KΩ±1%T52"))
    )
    (comp (ref "R41")
      (value "2.2kΩ")
      (fields
        (field (name "BOM_Manufacturer Part") "MF1/4W-2.2KΩ±1%T52")
        (field (name "BOM_Supplier Part") "C714002")
      )
      (libsource (lib "") (part "MF1/4W-2.2KΩ±1%T52"))
    )
    (comp (ref "R42")
      (value "2.2kΩ")
      (fields
        (field (name "BOM_Manufacturer Part") "MF1/4W-2.2KΩ±1%T52")
        (field (name "BOM_Supplier Part") "C714002")
      )
      (libsource (lib "") (part "MF1/4W-2.2KΩ±1%T52"))
    )
    (comp (ref "RN1") (value "4609H-101-103LF") (libsource (lib "") (part "4609H-101-103LF")))
    (comp (ref "RN8") (value "4116R-1-102LF") (libsource (lib "") (part "4116R-1-102LF")))
    (comp (ref "U11")
      (value "SN74HC245N")
      (fields (field (name "BOM_Supplier Part") "C2899"))
      (libsource (lib "") (part "SN74HC245N"))
    )
    (comp (ref "U19")
      (value "SN74HC245N")
      (fields (field (name "BOM_Supplier Part") "C2899"))
      (libsource (lib "") (part "SN74HC245N"))
    )
    (comp (ref "DS5") (value "LTA-1000HR") (libsource (lib "") (part "LTA-1000HR")))
    (comp (ref "DS6") (value "LTA-1000HR") (libsource (lib "") (part "LTA-1000HR")))
    (comp (ref "DS7") (value "LTA-1000HR") (libsource (lib "") (part "LTA-1000HR")))
    (comp (ref "DS8") (value "LTA-1000HR") (libsource (lib "") (part "LTA-1000HR")))
    (comp (ref "R31") (value "33Ω") (libsource (lib "") (part "MF1/4W-1Ω±1%T52")))
    (comp (ref "R32") (value "33Ω") (libsource (lib "") (part "MF1/4W-1Ω±1%T52")))
    (comp (ref "RN9") (value "4116R-1-102LF") (libsource (lib "") (part "4116R-1-102LF")))
    (comp (ref "RN10") (value "4609H-101-103LF") (libsource (lib "") (part "4609H-101-103LF")))
    (comp (ref "RN11") (value "4116R-1-102LF") (libsource (lib "") (part "4116R-1-102LF")))
    (comp (ref "RN12") (value "4609H-101-103LF") (libsource (lib "") (part "4609H-101-103LF")))
    (comp (ref "RN13") (value "4116R-1-102LF") (libsource (lib "") (part "4116R-1-102LF")))
    (comp (ref "RN14") (value "4609H-101-103LF") (libsource (lib "") (part "4609H-101-103LF")))
    (comp (ref "RN15") (value "4116R-1-102LF") (libsource (lib "") (part "4116R-1-102LF")))
    (comp (ref "RN16") (value "4609H-101-103LF") (libsource (lib "") (part "4609H-101-103LF")))
    (comp (ref "RN22") (value "4116R-1-330LF") (libsource (lib "") (part "4116R-1-330LF")))
    (comp (ref "RN23") (value "4116R-1-330LF") (libsource (lib "") (part "4116R-1-330LF")))
    (comp (ref "RN24") (value "4116R-1-330LF") (libsource (lib "") (part "4116R-1-330LF")))
    (comp (ref "U20")
      (value "SN74HC245N")
      (fields (field (name "BOM_Supplier Part") "C2899"))
      (libsource (lib "") (part "SN74HC245N"))
    )
    (comp (ref "U21")
      (value "SN74HC245N")
      (fields (field (name "BOM_Supplier Part") "C2899"))
      (libsource (lib "") (part "SN74HC245N"))
    )
    (comp (ref "U22")
      (value "SN74HC245N")
      (fields (field (name "BOM_Supplier Part") "C2899"))
      (libsource (lib "") (part "SN74HC245N"))
    )
    (comp (ref "U23")
      (value "SN74HC245N")
      (fields (field (name "BOM_Supplier Part") "C2899"))
      (libsource (lib "") (part "SN74HC245N"))
    )
    (comp (ref "U24")
      (value "SN74HC245N")
      (fields (field (name "BOM_Supplier Part") "C2899"))
      (libsource (lib "") (part "SN74HC245N"))
    )
    (comp (ref "U25")
      (value "SN74HC245N")
      (fields (field (name "BOM_Supplier Part") "C2899"))
      (libsource (lib "") (part "SN74HC245N"))
    )
    (comp (ref "U26")
      (value "SN74HC245N")
      (fields (field (name "BOM_Supplier Part") "C2899"))
      (libsource (lib "") (part "SN74HC245N"))
    )
    (comp (ref "U27")
      (value "SN74HC245N")
      (fields (field (name "BOM_Supplier Part") "C2899"))
      (libsource (lib "") (part "SN74HC245N"))
    )
    (comp (ref "DS9") (value "LTA-1000HR") (libsource (lib "") (part "LTA-1000HR")))
    (comp (ref "IMM")
      (value "SN74HC273N")
      (fields (field (name "BOM_Supplier Part") "C5238"))
      (libsource (lib "") (part "SN74HC273N"))
    )
    (comp (ref "R29")
      (value "10KΩ")
      (fields
        (field (name "BOM_Manufacturer Part") "MF1/4W-1Ω±1%T52")
        (field (name "BOM_Supplier Part") "C713947")
      )
      (libsource (lib "") (part "MF1/4W-1Ω±1%T52"))
    )
    (comp (ref "R30")
      (value "10KΩ")
      (fields
        (field (name "BOM_Manufacturer Part") "MF1/4W-1Ω±1%T52")
        (field (name "BOM_Supplier Part") "C713947")
      )
      (libsource (lib "") (part "MF1/4W-1Ω±1%T52"))
    )
    (comp (ref "R36") (value "33Ω") (libsource (lib "") (part "MF1/4W-1Ω±1%T52_1")))
    (comp (ref "R37") (value "33Ω") (libsource (lib "") (part "MF1/4W-1Ω±1%T52_1")))
    (comp (ref "RN17") (value "4116R-1-102LF") (libsource (lib "") (part "4116R-1-102LF")))
    (comp (ref "RN18") (value "4609H-101-103LF") (libsource (lib "") (part "4609H-101-103LF")))
    (comp (ref "RN19") (value "4609H-101-103LF") (libsource (lib "") (part "4609H-101-103LF_1")))
    (comp (ref "RN20") (value "4116R-1-330LF") (libsource (lib "") (part "4116R-1-330LF")))
    (comp (ref "RN21") (value "4116R-1-330LF") (libsource (lib "") (part "4116R-1-330LF")))
    (comp (ref "U28")
      (value "SN74HC00N")
      (fields (field (name "BOM_Supplier Part") "C2902"))
      (libsource (lib "") (part "SN74HC00N"))
    )
    (comp (ref "U29")
      (value "SN74HC245N")
      (fields (field (name "BOM_Supplier Part") "C2899"))
      (libsource (lib "") (part "SN74HC245N"))
    )
    (comp (ref "U30")
      (value "SN74HC245N")
      (fields (field (name "BOM_Supplier Part") "C2899"))
      (libsource (lib "") (part "SN74HC245N"))
    )
    (comp (ref "U31")
      (value "SN74HC245N")
      (fields (field (name "BOM_Supplier Part") "C2899"))
      (libsource (lib "") (part "SN74HC245N_1"))
    )
    (comp (ref "C5")
      (value "100µF")
      (fields
        (field (name "BOM_Manufacturer Part") "UHE1E101MED1TD")
        (field (name "BOM_Supplier Part") "C116227")
      )
      (libsource (lib "") (part "UHE1E101MED1TD"))
    )
    (comp (ref "C6")
      (value "100µF")
      (fields
        (field (name "BOM_Manufacturer Part") "UHE1E101MED1TD")
        (field (name "BOM_Supplier Part") "C116227")
      )
      (libsource (lib "") (part "UHE1E101MED1TD"))
    )
    (comp (ref "C7")
      (value "100µF")
      (fields
        (field (name "BOM_Manufacturer Part") "UHE1E101MED1TD")
        (field (name "BOM_Supplier Part") "C116227")
      )
      (libsource (lib "") (part "UHE1E101MED1TD"))
    )
    (comp (ref "C8")
      (value "100µF")
      (fields
        (field (name "BOM_Manufacturer Part") "UHE1E101MED1TD")
        (field (name "BOM_Supplier Part") "C116227")
      )
      (libsource (lib "") (part "UHE1E101MED1TD"))
    )
    (comp (ref "C9")
      (value "100µF")
      (fields
        (field (name "BOM_Manufacturer Part") "UHE1E101MED1TD")
        (field (name "BOM_Supplier Part") "C116227")
      )
      (libsource (lib "") (part "UHE1E101MED1TD"))
    )
    (comp (ref "C10")
      (value "100µF")
      (fields
        (field (name "BOM_Manufacturer Part") "UHE1E101MED1TD")
        (field (name "BOM_Supplier Part") "C116227")
      )
      (libsource (lib "") (part "UHE1E101MED1TD"))
    )
    (comp (ref "C11")
      (value "100µF")
      (fields
        (field (name "BOM_Manufacturer Part") "UHE1E101MED1TD")
        (field (name "BOM_Supplier Part") "C116227")
      )
      (libsource (lib "") (part "UHE1E101MED1TD"))
    )
    (comp (ref "C12")
      (value "100µF")
      (fields
        (field (name "BOM_Manufacturer Part") "UHE1E101MED1TD")
        (field (name "BOM_Supplier Part") "C116227")
      )
      (libsource (lib "") (part "UHE1E101MED1TD"))
    )
    (comp (ref "C13")
      (value "100µF")
      (fields
        (field (name "BOM_Manufacturer Part") "UHE1E101MED1TD")
        (field (name "BOM_Supplier Part") "C116227")
      )
      (libsource (lib "") (part "UHE1E101MED1TD"))
    )
    (comp (ref "C14")
      (value "100µF")
      (fields
        (field (name "BOM_Manufacturer Part") "UHE1E101MED1TD")
        (field (name "BOM_Supplier Part") "C116227")
      )
      (libsource (lib "") (part "UHE1E101MED1TD"))
    )
    (comp (ref "C15")
      (value "100nF")
      (fields
        (field (name "BOM_Manufacturer Part") "K104M15X7RF5TH5")
        (field (name "BOM_Supplier Part") "C499573")
      )
      (libsource (lib "") (part "K104M15X7RF5TH5"))
    )
    (comp (ref "C16")
      (value "100nF")
      (fields
        (field (name "BOM_Manufacturer Part") "K104M15X7RF5TH5")
        (field (name "BOM_Supplier Part") "C499573")
      )
      (libsource (lib "") (part "K104M15X7RF5TH5"))
    )
    (comp (ref "C17")
      (value "100nF")
      (fields
        (field (name "BOM_Manufacturer Part") "K104M15X7RF5TH5")
        (field (name "BOM_Supplier Part") "C499573")
      )
      (libsource (lib "") (part "K104M15X7RF5TH5"))
    )
    (comp (ref "C18")
      (value "100nF")
      (fields
        (field (name "BOM_Manufacturer Part") "K104M15X7RF5TH5")
        (field (name "BOM_Supplier Part") "C499573")
      )
      (libsource (lib "") (part "K104M15X7RF5TH5"))
    )
    (comp (ref "C19")
      (value "100nF")
      (fields
        (field (name "BOM_Manufacturer Part") "K104M15X7RF5TH5")
        (field (name "BOM_Supplier Part") "C499573")
      )
      (libsource (lib "") (part "K104M15X7RF5TH5"))
    )
    (comp (ref "C20")
      (value "100nF")
      (fields
        (field (name "BOM_Manufacturer Part") "K104M15X7RF5TH5")
        (field (name "BOM_Supplier Part") "C499573")
      )
      (libsource (lib "") (part "K104M15X7RF5TH5"))
    )
    (comp (ref "C21")
      (value "100nF")
      (fields
        (field (name "BOM_Manufacturer Part") "K104M15X7RF5TH5")
        (field (name "BOM_Supplier Part") "C499573")
      )
      (libsource (lib "") (part "K104M15X7RF5TH5"))
    )
    (comp (ref "C22")
      (value "100nF")
      (fields
        (field (name "BOM_Manufacturer Part") "K104M15X7RF5TH5")
        (field (name "BOM_Supplier Part") "C499573")
      )
      (libsource (lib "") (part "K104M15X7RF5TH5"))
    )
    (comp (ref "C23")
      (value "100nF")
      (fields
        (field (name "BOM_Manufacturer Part") "K104M15X7RF5TH5")
        (field (name "BOM_Supplier Part") "C499573")
      )
      (libsource (lib "") (part "K104M15X7RF5TH5"))
    )
    (comp (ref "C24")
      (value "100nF")
      (fields
        (field (name "BOM_Manufacturer Part") "K104M15X7RF5TH5")
        (field (name "BOM_Supplier Part") "C499573")
      )
      (libsource (lib "") (part "K104M15X7RF5TH5"))
    )
    (comp (ref "C25")
      (value "100nF")
      (fields
        (field (name "BOM_Manufacturer Part") "K104M15X7RF5TH5")
        (field (name "BOM_Supplier Part") "C499573")
      )
      (libsource (lib "") (part "K104M15X7RF5TH5"))
    )
    (comp (ref "C26")
      (value "100nF")
      (fields
        (field (name "BOM_Manufacturer Part") "K104M15X7RF5TH5")
        (field (name "BOM_Supplier Part") "C499573")
      )
      (libsource (lib "") (part "K104M15X7RF5TH5"))
    )
    (comp (ref "C27")
      (value "100nF")
      (fields
        (field (name "BOM_Manufacturer Part") "K104M15X7RF5TH5")
        (field (name "BOM_Supplier Part") "C499573")
      )
      (libsource (lib "") (part "K104M15X7RF5TH5"))
    )
    (comp (ref "C28")
      (value "100nF")
      (fields
        (field (name "BOM_Manufacturer Part") "K104M15X7RF5TH5")
        (field (name "BOM_Supplier Part") "C499573")
      )
      (libsource (lib "") (part "K104M15X7RF5TH5"))
    )
    (comp (ref "C29")
      (value "100nF")
      (fields
        (field (name "BOM_Manufacturer Part") "K104M15X7RF5TH5")
        (field (name "BOM_Supplier Part") "C499573")
      )
      (libsource (lib "") (part "K104M15X7RF5TH5"))
    )
    (comp (ref "C30")
      (value "100nF")
      (fields
        (field (name "BOM_Manufacturer Part") "K104M15X7RF5TH5")
        (field (name "BOM_Supplier Part") "C499573")
      )
      (libsource (lib "") (part "K104M15X7RF5TH5"))
    )
    (comp (ref "C31")
      (value "100nF")
      (fields
        (field (name "BOM_Manufacturer Part") "K104M15X7RF5TH5")
        (field (name "BOM_Supplier Part") "C499573")
      )
      (libsource (lib "") (part "K104M15X7RF5TH5"))
    )
    (comp (ref "C32")
      (value "100nF")
      (fields
        (field (name "BOM_Manufacturer Part") "K104M15X7RF5TH5")
        (field (name "BOM_Supplier Part") "C499573")
      )
      (libsource (lib "") (part "K104M15X7RF5TH5"))
    )
    (comp (ref "C33")
      (value "100nF")
      (fields
        (field (name "BOM_Manufacturer Part") "K104M15X7RF5TH5")
        (field (name "BOM_Supplier Part") "C499573")
      )
      (libsource (lib "") (part "K104M15X7RF5TH5"))
    )
    (comp (ref "C34")
      (value "100nF")
      (fields
        (field (name "BOM_Manufacturer Part") "K104M15X7RF5TH5")
        (field (name "BOM_Supplier Part") "C499573")
      )
      (libsource (lib "") (part "K104M15X7RF5TH5"))
    )
    (comp (ref "C35")
      (value "100nF")
      (fields
        (field (name "BOM_Manufacturer Part") "K104M15X7RF5TH5")
        (field (name "BOM_Supplier Part") "C499573")
      )
      (libsource (lib "") (part "K104M15X7RF5TH5"))
    )
    (comp (ref "C36")
      (value "100nF")
      (fields
        (field (name "BOM_Manufacturer Part") "K104M15X7RF5TH5")
        (field (name "BOM_Supplier Part") "C499573")
      )
      (libsource (lib "") (part "K104M15X7RF5TH5"))
    )
    (comp (ref "C37")
      (value "100nF")
      (fields
        (field (name "BOM_Manufacturer Part") "K104M15X7RF5TH5")
        (field (name "BOM_Supplier Part") "C499573")
      )
      (libsource (lib "") (part "K104M15X7RF5TH5"))
    )
    (comp (ref "C38")
      (value "100nF")
      (fields
        (field (name "BOM_Manufacturer Part") "K104M15X7RF5TH5")
        (field (name "BOM_Supplier Part") "C499573")
      )
      (libsource (lib "") (part "K104M15X7RF5TH5"))
    )
    (comp (ref "C39")
      (value "100nF")
      (fields
        (field (name "BOM_Manufacturer Part") "K104M15X7RF5TH5")
        (field (name "BOM_Supplier Part") "C499573")
      )
      (libsource (lib "") (part "K104M15X7RF5TH5"))
    )
    (comp (ref "C40")
      (value "100nF")
      (fields
        (field (name "BOM_Manufacturer Part") "K104M15X7RF5TH5")
        (field (name "BOM_Supplier Part") "C499573")
      )
      (libsource (lib "") (part "K104M15X7RF5TH5"))
    )
    (comp (ref "C41")
      (value "100nF")
      (fields
        (field (name "BOM_Manufacturer Part") "K104M15X7RF5TH5")
        (field (name "BOM_Supplier Part") "C499573")
      )
      (libsource (lib "") (part "K104M15X7RF5TH5"))
    )
    (comp (ref "C42")
      (value "100nF")
      (fields
        (field (name "BOM_Manufacturer Part") "K104M15X7RF5TH5")
        (field (name "BOM_Supplier Part") "C499573")
      )
      (libsource (lib "") (part "K104M15X7RF5TH5"))
    )
    (comp (ref "C43")
      (value "100nF")
      (fields
        (field (name "BOM_Manufacturer Part") "K104M15X7RF5TH5")
        (field (name "BOM_Supplier Part") "C499573")
      )
      (libsource (lib "") (part "K104M15X7RF5TH5"))
    )
    (comp (ref "C44")
      (value "100nF")
      (fields
        (field (name "BOM_Manufacturer Part") "K104M15X7RF5TH5")
        (field (name "BOM_Supplier Part") "C499573")
      )
      (libsource (lib "") (part "K104M15X7RF5TH5"))
    )
    (comp (ref "C45")
      (value "100nF")
      (fields
        (field (name "BOM_Manufacturer Part") "K104M15X7RF5TH5")
        (field (name "BOM_Supplier Part") "C499573")
      )
      (libsource (lib "") (part "K104M15X7RF5TH5"))
    )
    (comp (ref "C46")
      (value "100nF")
      (fields
        (field (name "BOM_Manufacturer Part") "K104M15X7RF5TH5")
        (field (name "BOM_Supplier Part") "C499573")
      )
      (libsource (lib "") (part "K104M15X7RF5TH5"))
    )
    (comp (ref "C47")
      (value "100nF")
      (fields
        (field (name "BOM_Manufacturer Part") "K104M15X7RF5TH5")
        (field (name "BOM_Supplier Part") "C499573")
      )
      (libsource (lib "") (part "K104M15X7RF5TH5"))
    )
    (comp (ref "C48")
      (value "100nF")
      (fields
        (field (name "BOM_Manufacturer Part") "K104M15X7RF5TH5")
        (field (name "BOM_Supplier Part") "C499573")
      )
      (libsource (lib "") (part "K104M15X7RF5TH5"))
    )
    (comp (ref "C49")
      (value "100nF")
      (fields
        (field (name "BOM_Manufacturer Part") "K104M15X7RF5TH5")
        (field (name "BOM_Supplier Part") "C499573")
      )
      (libsource (lib "") (part "K104M15X7RF5TH5"))
    )
    (comp (ref "C50")
      (value "100nF")
      (fields
        (field (name "BOM_Manufacturer Part") "K104M15X7RF5TH5")
        (field (name "BOM_Supplier Part") "C499573")
      )
      (libsource (lib "") (part "K104M15X7RF5TH5"))
    )
    (comp (ref "C51")
      (value "100nF")
      (fields
        (field (name "BOM_Manufacturer Part") "K104M15X7RF5TH5")
        (field (name "BOM_Supplier Part") "C499573")
      )
      (libsource (lib "") (part "K104M15X7RF5TH5"))
    )
    (comp (ref "C52")
      (value "100nF")
      (fields
        (field (name "BOM_Manufacturer Part") "K104M15X7RF5TH5")
        (field (name "BOM_Supplier Part") "C499573")
      )
      (libsource (lib "") (part "K104M15X7RF5TH5"))
    )
    (comp (ref "C53")
      (value "100nF")
      (fields
        (field (name "BOM_Manufacturer Part") "K104M15X7RF5TH5")
        (field (name "BOM_Supplier Part") "C499573")
      )
      (libsource (lib "") (part "K104M15X7RF5TH5"))
    )
    (comp (ref "C54")
      (value "100nF")
      (fields
        (field (name "BOM_Manufacturer Part") "K104M15X7RF5TH5")
        (field (name "BOM_Supplier Part") "C499573")
      )
      (libsource (lib "") (part "K104M15X7RF5TH5"))
    )
    (comp (ref "C55")
      (value "100nF")
      (fields
        (field (name "BOM_Manufacturer Part") "K104M15X7RF5TH5")
        (field (name "BOM_Supplier Part") "C499573")
      )
      (libsource (lib "") (part "K104M15X7RF5TH5"))
    )
    (comp (ref "C56")
      (value "100nF")
      (fields
        (field (name "BOM_Manufacturer Part") "K104M15X7RF5TH5")
        (field (name "BOM_Supplier Part") "C499573")
      )
      (libsource (lib "") (part "K104M15X7RF5TH5"))
    )
    (comp (ref "C57")
      (value "100nF")
      (fields
        (field (name "BOM_Manufacturer Part") "K104M15X7RF5TH5")
        (field (name "BOM_Supplier Part") "C499573")
      )
      (libsource (lib "") (part "K104M15X7RF5TH5"))
    )
    (comp (ref "J1") (value "PCN10-64ACP-2.54DS_72_") (libsource (lib "") (part "PCN10-64ACP-2.54DS_72_")))
    (comp (ref "J2") (value "PCN10-64ACP-2.54DS_72_") (libsource (lib "") (part "PCN10-64ACP-2.54DS_72_")))
  )
  (nets
    (net (code "1") (name "AHLE") (class "Default")
      (node (ref "J1") (pin "C9") (pinfunction "C9_C9") (pintype "bidirectional"))
      (node (ref "RN24") (pin "16") (pinfunction "16_16") (pintype "bidirectional"))
    )
    (net (code "2") (name "AHOE") (class "Default")
      (node (ref "J1") (pin "A7") (pinfunction "A7_A7") (pintype "bidirectional"))
      (node (ref "RN24") (pin "15") (pinfunction "15_15") (pintype "bidirectional"))
    )
    (net (code "3") (name "ALLE") (class "Default")
      (node (ref "J1") (pin "C6") (pinfunction "C6_C6") (pintype "bidirectional"))
      (node (ref "RN24") (pin "14") (pinfunction "14_14") (pintype "bidirectional"))
    )
    (net (code "4") (name "ALOE") (class "Default")
      (node (ref "J1") (pin "A4") (pinfunction "A4_A4") (pintype "bidirectional"))
      (node (ref "RN24") (pin "13") (pinfunction "13_13") (pintype "bidirectional"))
    )
    (net (code "5") (name "AR1CE") (class "Default")
      (node (ref "J2") (pin "C30") (pinfunction "C30_C30") (pintype "bidirectional"))
      (node (ref "RN24") (pin "12") (pinfunction "12_12") (pintype "bidirectional"))
    )
    (net (code "6") (name "AR1LE") (class "Default")
      (node (ref "J2") (pin "A28") (pinfunction "A28_A28") (pintype "bidirectional"))
      (node (ref "RN24") (pin "11") (pinfunction "11_11") (pintype "bidirectional"))
    )
    (net (code "7") (name "AR1OE") (class "Default")
      (node (ref "J2") (pin "A29") (pinfunction "A29_A29") (pintype "bidirectional"))
      (node (ref "RN24") (pin "10") (pinfunction "10_10") (pintype "bidirectional"))
    )
    (net (code "8") (name "AR2CE") (class "Default")
      (node (ref "J1") (pin "C4") (pinfunction "C4_C4") (pintype "bidirectional"))
      (node (ref "RN24") (pin "9") (pinfunction "9_9") (pintype "bidirectional"))
    )
    (net (code "9") (name "AR2LE") (class "Default")
      (node (ref "J1") (pin "A3") (pinfunction "A3_A3") (pintype "bidirectional"))
      (node (ref "RN23") (pin "16") (pinfunction "16_16") (pintype "bidirectional"))
    )
    (net (code "10") (name "AR2OE") (class "Default")
      (node (ref "J1") (pin "C3") (pinfunction "C3_C3") (pintype "bidirectional"))
      (node (ref "RN23") (pin "15") (pinfunction "15_15") (pintype "bidirectional"))
    )
    (net (code "11") (name "BHLE") (class "Default")
      (node (ref "J1") (pin "A9") (pinfunction "A9_A9") (pintype "bidirectional"))
      (node (ref "RN23") (pin "14") (pinfunction "14_14") (pintype "bidirectional"))
    )
    (net (code "12") (name "BHOE") (class "Default")
      (node (ref "J1") (pin "C8") (pinfunction "C8_C8") (pintype "bidirectional"))
      (node (ref "RN23") (pin "13") (pinfunction "13_13") (pintype "bidirectional"))
    )
    (net (code "13") (name "BLLE") (class "Default")
      (node (ref "J1") (pin "A6") (pinfunction "A6_A6") (pintype "bidirectional"))
      (node (ref "RN23") (pin "12") (pinfunction "12_12") (pintype "bidirectional"))
    )
    (net (code "14") (name "BLOE") (class "Default")
      (node (ref "J1") (pin "C5") (pinfunction "C5_C5") (pintype "bidirectional"))
      (node (ref "RN23") (pin "11") (pinfunction "11_11") (pintype "bidirectional"))
    )
    (net (code "15") (name "BPOE") (class "Default")
      (node (ref "U1") (pin "4") (pinfunction "2Y_4") (pintype "unspecified"))
      (node (ref "U1") (pin "5") (pinfunction "3A_5") (pintype "unspecified"))
      (node (ref "U12") (pin "19") (pinfunction "OE#_19") (pintype "unspecified"))
      (node (ref "U2") (pin "19") (pinfunction "OE#_19") (pintype "unspecified"))
      (node (ref "U3") (pin "19") (pinfunction "OE#_19") (pintype "unspecified"))
    )
    (net (code "16") (name "BPVdd") (class "Default")
      (node (ref "J1") (pin "A1") (pinfunction "A1_A1") (pintype "bidirectional"))
      (node (ref "J1") (pin "A2") (pinfunction "A2_A2") (pintype "bidirectional"))
      (node (ref "J1") (pin "A31") (pinfunction "A31_A31") (pintype "bidirectional"))
      (node (ref "J1") (pin "A32") (pinfunction "A32_A32") (pintype "bidirectional"))
      (node (ref "J2") (pin "A1") (pinfunction "A1_A1") (pintype "bidirectional"))
      (node (ref "J2") (pin "A2") (pinfunction "A2_A2") (pintype "bidirectional"))
      (node (ref "J2") (pin "A31") (pinfunction "A31_A31") (pintype "bidirectional"))
      (node (ref "J2") (pin "A32") (pinfunction "A32_A32") (pintype "bidirectional"))
      (node (ref "PWSW") (pin "3") (pinfunction "3_3") (pintype "input"))
    )
    (net (code "17") (name "CFH") (class "Default")
      (node (ref "J1") (pin "A11") (pinfunction "A11_A11") (pintype "bidirectional"))
      (node (ref "U12") (pin "11") (pinfunction "B8_11") (pintype "unspecified"))
    )
    (net (code "18") (name "CFL") (class "Default")
      (node (ref "J1") (pin "C11") (pinfunction "C11_C11") (pintype "bidirectional"))
      (node (ref "U12") (pin "12") (pinfunction "B7_12") (pintype "unspecified"))
    )
    (net (code "19") (name "CIMF") (class "Default")
      (node (ref "RN16") (pin "4") (pinfunction "4_4") (pintype "bidirectional"))
      (node (ref "U26") (pin "16") (pinfunction "B3_16") (pintype "unspecified"))
      (node (ref "U27") (pin "4") (pinfunction "A3_4") (pintype "unspecified"))
      (node (ref "U8") (pin "3") (pinfunction "2A_3") (pintype "unspecified"))
    )
    (net (code "20") (name "CLK") (class "Default")
      (node (ref "J2") (pin "C31") (pinfunction "C31_C31") (pintype "bidirectional"))
      (node (ref "R14") (pin "1") (pinfunction "1_1") (pintype "unspecified"))
      (node (ref "U28") (pin "4") (pinfunction "2A_4") (pintype "unspecified"))
    )
    (net (code "21") (name "COMF") (class "Default")
      (node (ref "J2") (pin "C25") (pinfunction "C25_C25") (pintype "bidirectional"))
      (node (ref "U2") (pin "14") (pinfunction "B5_14") (pintype "unspecified"))
    )
    (net (code "22") (name "DIR0") (class "Default")
      (node (ref "DIR0") (pin "2") (pinfunction "1Q_2") (pintype "unspecified"))
      (node (ref "U27") (pin "11") (pinfunction "B8_11") (pintype "unspecified"))
    )
    (net (code "23") (name "DIR1") (class "Default")
      (node (ref "DIR0") (pin "5") (pinfunction "2Q_5") (pintype "unspecified"))
      (node (ref "U27") (pin "12") (pinfunction "B7_12") (pintype "unspecified"))
    )
    (net (code "24") (name "DIR2") (class "Default")
      (node (ref "DIR0") (pin "6") (pinfunction "3Q_6") (pintype "unspecified"))
      (node (ref "U27") (pin "13") (pinfunction "B6_13") (pintype "unspecified"))
    )
    (net (code "25") (name "DIR3") (class "Default")
      (node (ref "DIR0") (pin "9") (pinfunction "4Q_9") (pintype "unspecified"))
      (node (ref "U27") (pin "14") (pinfunction "B5_14") (pintype "unspecified"))
    )
    (net (code "26") (name "DIR4") (class "Default")
      (node (ref "DIR0") (pin "12") (pinfunction "5Q_12") (pintype "unspecified"))
      (node (ref "U27") (pin "15") (pinfunction "B4_15") (pintype "unspecified"))
    )
    (net (code "27") (name "DIR5") (class "Default")
      (node (ref "DIR0") (pin "15") (pinfunction "6Q_15") (pintype "unspecified"))
      (node (ref "U27") (pin "16") (pinfunction "B3_16") (pintype "unspecified"))
    )
    (net (code "28") (name "DIR6") (class "Default")
      (node (ref "DIR0") (pin "16") (pinfunction "7Q_16") (pintype "unspecified"))
      (node (ref "U27") (pin "17") (pinfunction "B2_17") (pintype "unspecified"))
    )
    (net (code "29") (name "DIR7") (class "Default")
      (node (ref "DIR0") (pin "19") (pinfunction "8Q_19") (pintype "unspecified"))
      (node (ref "U27") (pin "18") (pinfunction "B1_18") (pintype "unspecified"))
    )
    (net (code "30") (name "DIR8") (class "Default")
      (node (ref "DIR1") (pin "2") (pinfunction "1Q_2") (pintype "unspecified"))
      (node (ref "U25") (pin "11") (pinfunction "B8_11") (pintype "unspecified"))
    )
    (net (code "31") (name "DIR9") (class "Default")
      (node (ref "DIR1") (pin "5") (pinfunction "2Q_5") (pintype "unspecified"))
      (node (ref "U25") (pin "12") (pinfunction "B7_12") (pintype "unspecified"))
    )
    (net (code "32") (name "DIR10") (class "Default")
      (node (ref "DIR1") (pin "6") (pinfunction "3Q_6") (pintype "unspecified"))
      (node (ref "U25") (pin "13") (pinfunction "B6_13") (pintype "unspecified"))
    )
    (net (code "33") (name "DIR11") (class "Default")
      (node (ref "DIR1") (pin "9") (pinfunction "4Q_9") (pintype "unspecified"))
      (node (ref "U25") (pin "14") (pinfunction "B5_14") (pintype "unspecified"))
    )
    (net (code "34") (name "DIR12") (class "Default")
      (node (ref "DIR1") (pin "12") (pinfunction "5Q_12") (pintype "unspecified"))
      (node (ref "U25") (pin "15") (pinfunction "B4_15") (pintype "unspecified"))
    )
    (net (code "35") (name "DIR13") (class "Default")
      (node (ref "DIR1") (pin "15") (pinfunction "6Q_15") (pintype "unspecified"))
      (node (ref "U25") (pin "16") (pinfunction "B3_16") (pintype "unspecified"))
    )
    (net (code "36") (name "DIR14") (class "Default")
      (node (ref "DIR1") (pin "16") (pinfunction "7Q_16") (pintype "unspecified"))
      (node (ref "U25") (pin "17") (pinfunction "B2_17") (pintype "unspecified"))
    )
    (net (code "37") (name "DIR15") (class "Default")
      (node (ref "DIR1") (pin "19") (pinfunction "8Q_19") (pintype "unspecified"))
      (node (ref "U25") (pin "18") (pinfunction "B1_18") (pintype "unspecified"))
    )
    (net (code "38") (name "DIR16") (class "Default")
      (node (ref "DIR2") (pin "2") (pinfunction "1Q_2") (pintype "unspecified"))
      (node (ref "U23") (pin "11") (pinfunction "B8_11") (pintype "unspecified"))
    )
    (net (code "39") (name "DIR17") (class "Default")
      (node (ref "DIR2") (pin "5") (pinfunction "2Q_5") (pintype "unspecified"))
      (node (ref "U23") (pin "12") (pinfunction "B7_12") (pintype "unspecified"))
    )
    (net (code "40") (name "DIR18") (class "Default")
      (node (ref "DIR2") (pin "6") (pinfunction "3Q_6") (pintype "unspecified"))
      (node (ref "U23") (pin "13") (pinfunction "B6_13") (pintype "unspecified"))
    )
    (net (code "41") (name "DIR19") (class "Default")
      (node (ref "DIR2") (pin "9") (pinfunction "4Q_9") (pintype "unspecified"))
      (node (ref "U23") (pin "14") (pinfunction "B5_14") (pintype "unspecified"))
    )
    (net (code "42") (name "DIR20") (class "Default")
      (node (ref "DIR2") (pin "12") (pinfunction "5Q_12") (pintype "unspecified"))
      (node (ref "U23") (pin "15") (pinfunction "B4_15") (pintype "unspecified"))
    )
    (net (code "43") (name "DIR21") (class "Default")
      (node (ref "DIR2") (pin "15") (pinfunction "6Q_15") (pintype "unspecified"))
      (node (ref "U23") (pin "16") (pinfunction "B3_16") (pintype "unspecified"))
    )
    (net (code "44") (name "DIR22") (class "Default")
      (node (ref "DIR2") (pin "16") (pinfunction "7Q_16") (pintype "unspecified"))
      (node (ref "U23") (pin "17") (pinfunction "B2_17") (pintype "unspecified"))
    )
    (net (code "45") (name "DIR23") (class "Default")
      (node (ref "DIR2") (pin "19") (pinfunction "8Q_19") (pintype "unspecified"))
      (node (ref "U23") (pin "18") (pinfunction "B1_18") (pintype "unspecified"))
    )
    (net (code "46") (name "DIR24") (class "Default")
      (node (ref "DIR3") (pin "2") (pinfunction "1Q_2") (pintype "unspecified"))
      (node (ref "U21") (pin "11") (pinfunction "B8_11") (pintype "unspecified"))
    )
    (net (code "47") (name "DIR25") (class "Default")
      (node (ref "DIR3") (pin "5") (pinfunction "2Q_5") (pintype "unspecified"))
      (node (ref "U21") (pin "12") (pinfunction "B7_12") (pintype "unspecified"))
    )
    (net (code "48") (name "DIR26") (class "Default")
      (node (ref "DIR3") (pin "6") (pinfunction "3Q_6") (pintype "unspecified"))
      (node (ref "U21") (pin "13") (pinfunction "B6_13") (pintype "unspecified"))
    )
    (net (code "49") (name "DIR27") (class "Default")
      (node (ref "DIR3") (pin "9") (pinfunction "4Q_9") (pintype "unspecified"))
      (node (ref "U21") (pin "14") (pinfunction "B5_14") (pintype "unspecified"))
    )
    (net (code "50") (name "DIR28") (class "Default")
      (node (ref "DIR3") (pin "12") (pinfunction "5Q_12") (pintype "unspecified"))
      (node (ref "U21") (pin "15") (pinfunction "B4_15") (pintype "unspecified"))
    )
    (net (code "51") (name "DIR29") (class "Default")
      (node (ref "DIR3") (pin "15") (pinfunction "6Q_15") (pintype "unspecified"))
      (node (ref "U21") (pin "16") (pinfunction "B3_16") (pintype "unspecified"))
    )
    (net (code "52") (name "DIR30") (class "Default")
      (node (ref "DIR3") (pin "16") (pinfunction "7Q_16") (pintype "unspecified"))
      (node (ref "U21") (pin "17") (pinfunction "B2_17") (pintype "unspecified"))
    )
    (net (code "53") (name "DIR31") (class "Default")
      (node (ref "DIR3") (pin "19") (pinfunction "8Q_19") (pintype "unspecified"))
      (node (ref "U21") (pin "18") (pinfunction "B1_18") (pintype "unspecified"))
    )
    (net (code "54") (name "EDBIE") (class "Default")
      (node (ref "J1") (pin "C7") (pinfunction "C7_C7") (pintype "bidirectional"))
      (node (ref "RN23") (pin "10") (pinfunction "10_10") (pintype "bidirectional"))
    )
    (net (code "55") (name "FREE") (class "Default")
      (node (ref "J2") (pin "C24") (pinfunction "C24_C24") (pintype "bidirectional"))
      (node (ref "R32") (pin "2") (pinfunction "2_2") (pintype "unspecified"))
    )
    (net (code "56") (name "GND") (class "Default")
      (node (ref "9V-12V-DC") (pin "2") (pinfunction "2_2") (pintype "bidirectional"))
      (node (ref "9V-12V-DC") (pin "3") (pinfunction "3_3") (pintype "bidirectional"))
      (node (ref "C1") (pin "2") (pinfunction "-_2") (pintype "bidirectional"))
      (node (ref "C10") (pin "2") (pinfunction "2_2") (pintype "input"))
      (node (ref "C11") (pin "2") (pinfunction "2_2") (pintype "input"))
      (node (ref "C12") (pin "2") (pinfunction "2_2") (pintype "input"))
      (node (ref "C13") (pin "2") (pinfunction "2_2") (pintype "input"))
      (node (ref "C14") (pin "2") (pinfunction "2_2") (pintype "input"))
      (node (ref "C15") (pin "2") (pinfunction "2_2") (pintype "unspecified"))
      (node (ref "C16") (pin "2") (pinfunction "2_2") (pintype "unspecified"))
      (node (ref "C17") (pin "2") (pinfunction "2_2") (pintype "unspecified"))
      (node (ref "C18") (pin "2") (pinfunction "2_2") (pintype "unspecified"))
      (node (ref "C19") (pin "2") (pinfunction "2_2") (pintype "unspecified"))
      (node (ref "C2") (pin "2") (pinfunction "-_2") (pintype "bidirectional"))
      (node (ref "C20") (pin "2") (pinfunction "2_2") (pintype "unspecified"))
      (node (ref "C21") (pin "2") (pinfunction "2_2") (pintype "unspecified"))
      (node (ref "C22") (pin "2") (pinfunction "2_2") (pintype "unspecified"))
      (node (ref "C23") (pin "2") (pinfunction "2_2") (pintype "unspecified"))
      (node (ref "C24") (pin "2") (pinfunction "2_2") (pintype "unspecified"))
      (node (ref "C25") (pin "2") (pinfunction "2_2") (pintype "unspecified"))
      (node (ref "C26") (pin "2") (pinfunction "2_2") (pintype "unspecified"))
      (node (ref "C27") (pin "2") (pinfunction "2_2") (pintype "unspecified"))
      (node (ref "C28") (pin "2") (pinfunction "2_2") (pintype "unspecified"))
      (node (ref "C29") (pin "2") (pinfunction "2_2") (pintype "unspecified"))
      (node (ref "C3") (pin "2") (pinfunction "2_2") (pintype "unspecified"))
      (node (ref "C30") (pin "2") (pinfunction "2_2") (pintype "unspecified"))
      (node (ref "C31") (pin "2") (pinfunction "2_2") (pintype "unspecified"))
      (node (ref "C32") (pin "2") (pinfunction "2_2") (pintype "unspecified"))
      (node (ref "C33") (pin "2") (pinfunction "2_2") (pintype "unspecified"))
      (node (ref "C34") (pin "2") (pinfunction "2_2") (pintype "unspecified"))
      (node (ref "C35") (pin "2") (pinfunction "2_2") (pintype "unspecified"))
      (node (ref "C36") (pin "2") (pinfunction "2_2") (pintype "unspecified"))
      (node (ref "C37") (pin "2") (pinfunction "2_2") (pintype "unspecified"))
      (node (ref "C38") (pin "2") (pinfunction "2_2") (pintype "unspecified"))
      (node (ref "C39") (pin "2") (pinfunction "2_2") (pintype "unspecified"))
      (node (ref "C4") (pin "2") (pinfunction "2_2") (pintype "unspecified"))
      (node (ref "C40") (pin "2") (pinfunction "2_2") (pintype "unspecified"))
      (node (ref "C41") (pin "2") (pinfunction "2_2") (pintype "unspecified"))
      (node (ref "C42") (pin "2") (pinfunction "2_2") (pintype "unspecified"))
      (node (ref "C43") (pin "2") (pinfunction "2_2") (pintype "unspecified"))
      (node (ref "C44") (pin "2") (pinfunction "2_2") (pintype "unspecified"))
      (node (ref "C45") (pin "2") (pinfunction "2_2") (pintype "unspecified"))
      (node (ref "C46") (pin "2") (pinfunction "2_2") (pintype "unspecified"))
      (node (ref "C47") (pin "2") (pinfunction "2_2") (pintype "unspecified"))
      (node (ref "C48") (pin "2") (pinfunction "2_2") (pintype "unspecified"))
      (node (ref "C49") (pin "2") (pinfunction "2_2") (pintype "unspecified"))
      (node (ref "C5") (pin "2") (pinfunction "2_2") (pintype "input"))
      (node (ref "C50") (pin "2") (pinfunction "2_2") (pintype "unspecified"))
      (node (ref "C51") (pin "2") (pinfunction "2_2") (pintype "unspecified"))
      (node (ref "C52") (pin "2") (pinfunction "2_2") (pintype "unspecified"))
      (node (ref "C53") (pin "2") (pinfunction "2_2") (pintype "unspecified"))
      (node (ref "C54") (pin "2") (pinfunction "2_2") (pintype "unspecified"))
      (node (ref "C55") (pin "2") (pinfunction "2_2") (pintype "unspecified"))
      (node (ref "C56") (pin "2") (pinfunction "2_2") (pintype "unspecified"))
      (node (ref "C57") (pin "2") (pinfunction "2_2") (pintype "unspecified"))
      (node (ref "C6") (pin "2") (pinfunction "2_2") (pintype "input"))
      (node (ref "C7") (pin "2") (pinfunction "2_2") (pintype "input"))
      (node (ref "C8") (pin "2") (pinfunction "2_2") (pintype "input"))
      (node (ref "C9") (pin "2") (pinfunction "2_2") (pintype "input"))
      (node (ref "CLK") (pin "3") (pinfunction "3_3") (pintype "unspecified"))
      (node (ref "CLK") (pin "4") (pinfunction "4_4") (pintype "unspecified"))
      (node (ref "D1") (pin "1") (pinfunction "1_1") (pintype "unspecified"))
      (node (ref "D3") (pin "2") (pinfunction "A_2") (pintype "unspecified"))
      (node (ref "DIR0") (pin "10") (pinfunction "GND_10") (pintype "unspecified"))
      (node (ref "DIR1") (pin "10") (pinfunction "GND_10") (pintype "unspecified"))
      (node (ref "DIR2") (pin "10") (pinfunction "GND_10") (pintype "unspecified"))
      (node (ref "DIR3") (pin "10") (pinfunction "GND_10") (pintype "unspecified"))
      (node (ref "DM0") (pin "16") (pinfunction "VSS_16") (pintype "unspecified"))
      (node (ref "DM0") (pin "22") (pinfunction "CE#_22") (pintype "unspecified"))
      (node (ref "DM0") (pin "24") (pinfunction "OE#_24") (pintype "unspecified"))
      (node (ref "DM0-A16") (pin "1") (pinfunction "1_1") (pintype "unspecified"))
      (node (ref "DM0-A17") (pin "3") (pinfunction "3_3") (pintype "unspecified"))
      (node (ref "DM0-A18") (pin "1") (pinfunction "1_1") (pintype "unspecified"))
      (node (ref "DM1") (pin "16") (pinfunction "VSS_16") (pintype "unspecified"))
      (node (ref "DM1") (pin "22") (pinfunction "CE#_22") (pintype "unspecified"))
      (node (ref "DM1") (pin "24") (pinfunction "OE#_24") (pintype "unspecified"))
      (node (ref "DM1-A16") (pin "1") (pinfunction "1_1") (pintype "unspecified"))
      (node (ref "DM1-A17") (pin "3") (pinfunction "3_3") (pintype "unspecified"))
      (node (ref "DM1-A18") (pin "1") (pinfunction "1_1") (pintype "unspecified"))
      (node (ref "DM2") (pin "16") (pinfunction "VSS_16") (pintype "unspecified"))
      (node (ref "DM2") (pin "22") (pinfunction "CE#_22") (pintype "unspecified"))
      (node (ref "DM2") (pin "24") (pinfunction "OE#_24") (pintype "unspecified"))
      (node (ref "DM2-A16") (pin "1") (pinfunction "1_1") (pintype "unspecified"))
      (node (ref "DM2-A17") (pin "3") (pinfunction "3_3") (pintype "unspecified"))
      (node (ref "DM2-A18") (pin "1") (pinfunction "1_1") (pintype "unspecified"))
      (node (ref "DM3") (pin "16") (pinfunction "VSS_16") (pintype "unspecified"))
      (node (ref "DM3") (pin "22") (pinfunction "CE#_22") (pintype "unspecified"))
      (node (ref "DM3") (pin "24") (pinfunction "OE#_24") (pintype "unspecified"))
      (node (ref "DM3-A16") (pin "1") (pinfunction "1_1") (pintype "unspecified"))
      (node (ref "DM3-A17") (pin "3") (pinfunction "3_3") (pintype "unspecified"))
      (node (ref "DM3-A18") (pin "1") (pinfunction "1_1") (pintype "unspecified"))
      (node (ref "DS1") (pin "10") (pinfunction "ANODE_K_10") (pintype "bidirectional"))
      (node (ref "DS1") (pin "11") (pinfunction "CATHODE_K_11") (pintype "bidirectional"))
      (node (ref "DS1") (pin "12") (pinfunction "CATHODE_J_12") (pintype "bidirectional"))
      (node (ref "DS1") (pin "13") (pinfunction "CATHODE_H_13") (pintype "bidirectional"))
      (node (ref "DS1") (pin "14") (pinfunction "CATHODE_G_14") (pintype "bidirectional"))
      (node (ref "DS1") (pin "15") (pinfunction "CATHODE_F_15") (pintype "bidirectional"))
      (node (ref "DS1") (pin "16") (pinfunction "CATHODE_E_16") (pintype "bidirectional"))
      (node (ref "DS1") (pin "17") (pinfunction "CATHODE_D_17") (pintype "bidirectional"))
      (node (ref "DS1") (pin "18") (pinfunction "CATHODE_C_18") (pintype "bidirectional"))
      (node (ref "DS1") (pin "19") (pinfunction "CATHODE_B_19") (pintype "bidirectional"))
      (node (ref "DS1") (pin "20") (pinfunction "CATHODE_A_20") (pintype "bidirectional"))
      (node (ref "DS1") (pin "6") (pinfunction "ANODE_F_6") (pintype "bidirectional"))
      (node (ref "DS1") (pin "7") (pinfunction "ANODE_G_7") (pintype "bidirectional"))
      (node (ref "DS1") (pin "8") (pinfunction "ANODE_H_8") (pintype "bidirectional"))
      (node (ref "DS1") (pin "9") (pinfunction "ANODE_J_9") (pintype "bidirectional"))
      (node (ref "DS2") (pin "1") (pinfunction "ANODE_A_1") (pintype "bidirectional"))
      (node (ref "DS2") (pin "11") (pinfunction "CATHODE_K_11") (pintype "bidirectional"))
      (node (ref "DS2") (pin "12") (pinfunction "CATHODE_J_12") (pintype "bidirectional"))
      (node (ref "DS2") (pin "13") (pinfunction "CATHODE_H_13") (pintype "bidirectional"))
      (node (ref "DS2") (pin "14") (pinfunction "CATHODE_G_14") (pintype "bidirectional"))
      (node (ref "DS2") (pin "15") (pinfunction "CATHODE_F_15") (pintype "bidirectional"))
      (node (ref "DS2") (pin "16") (pinfunction "CATHODE_E_16") (pintype "bidirectional"))
      (node (ref "DS2") (pin "17") (pinfunction "CATHODE_D_17") (pintype "bidirectional"))
      (node (ref "DS2") (pin "18") (pinfunction "CATHODE_C_18") (pintype "bidirectional"))
      (node (ref "DS2") (pin "19") (pinfunction "CATHODE_B_19") (pintype "bidirectional"))
      (node (ref "DS2") (pin "2") (pinfunction "ANODE_B_2") (pintype "bidirectional"))
      (node (ref "DS2") (pin "20") (pinfunction "CATHODE_A_20") (pintype "bidirectional"))
      (node (ref "DS3") (pin "10") (pinfunction "ANODE_K_10") (pintype "bidirectional"))
      (node (ref "DS3") (pin "11") (pinfunction "CATHODE_K_11") (pintype "bidirectional"))
      (node (ref "DS3") (pin "12") (pinfunction "CATHODE_J_12") (pintype "bidirectional"))
      (node (ref "DS3") (pin "13") (pinfunction "CATHODE_H_13") (pintype "bidirectional"))
      (node (ref "DS3") (pin "14") (pinfunction "CATHODE_G_14") (pintype "bidirectional"))
      (node (ref "DS3") (pin "15") (pinfunction "CATHODE_F_15") (pintype "bidirectional"))
      (node (ref "DS3") (pin "16") (pinfunction "CATHODE_E_16") (pintype "bidirectional"))
      (node (ref "DS3") (pin "17") (pinfunction "CATHODE_D_17") (pintype "bidirectional"))
      (node (ref "DS3") (pin "18") (pinfunction "CATHODE_C_18") (pintype "bidirectional"))
      (node (ref "DS3") (pin "19") (pinfunction "CATHODE_B_19") (pintype "bidirectional"))
      (node (ref "DS3") (pin "20") (pinfunction "CATHODE_A_20") (pintype "bidirectional"))
      (node (ref "DS3") (pin "7") (pinfunction "ANODE_G_7") (pintype "bidirectional"))
      (node (ref "DS3") (pin "8") (pinfunction "ANODE_H_8") (pintype "bidirectional"))
      (node (ref "DS3") (pin "9") (pinfunction "ANODE_J_9") (pintype "bidirectional"))
      (node (ref "DS4") (pin "1") (pinfunction "ANODE_A_1") (pintype "bidirectional"))
      (node (ref "DS4") (pin "11") (pinfunction "CATHODE_K_11") (pintype "bidirectional"))
      (node (ref "DS4") (pin "12") (pinfunction "CATHODE_J_12") (pintype "bidirectional"))
      (node (ref "DS4") (pin "13") (pinfunction "CATHODE_H_13") (pintype "bidirectional"))
      (node (ref "DS4") (pin "14") (pinfunction "CATHODE_G_14") (pintype "bidirectional"))
      (node (ref "DS4") (pin "15") (pinfunction "CATHODE_F_15") (pintype "bidirectional"))
      (node (ref "DS4") (pin "16") (pinfunction "CATHODE_E_16") (pintype "bidirectional"))
      (node (ref "DS4") (pin "17") (pinfunction "CATHODE_D_17") (pintype "bidirectional"))
      (node (ref "DS4") (pin "18") (pinfunction "CATHODE_C_18") (pintype "bidirectional"))
      (node (ref "DS4") (pin "19") (pinfunction "CATHODE_B_19") (pintype "bidirectional"))
      (node (ref "DS4") (pin "2") (pinfunction "ANODE_B_2") (pintype "bidirectional"))
      (node (ref "DS4") (pin "20") (pinfunction "CATHODE_A_20") (pintype "bidirectional"))
      (node (ref "DS5") (pin "10") (pinfunction "ANODE_K_10") (pintype "bidirectional"))
      (node (ref "DS5") (pin "11") (pinfunction "CATHODE_K_11") (pintype "bidirectional"))
      (node (ref "DS5") (pin "12") (pinfunction "CATHODE_J_12") (pintype "bidirectional"))
      (node (ref "DS5") (pin "13") (pinfunction "CATHODE_H_13") (pintype "bidirectional"))
      (node (ref "DS5") (pin "14") (pinfunction "CATHODE_G_14") (pintype "bidirectional"))
      (node (ref "DS5") (pin "15") (pinfunction "CATHODE_F_15") (pintype "bidirectional"))
      (node (ref "DS5") (pin "16") (pinfunction "CATHODE_E_16") (pintype "bidirectional"))
      (node (ref "DS5") (pin "17") (pinfunction "CATHODE_D_17") (pintype "bidirectional"))
      (node (ref "DS5") (pin "18") (pinfunction "CATHODE_C_18") (pintype "bidirectional"))
      (node (ref "DS5") (pin "19") (pinfunction "CATHODE_B_19") (pintype "bidirectional"))
      (node (ref "DS5") (pin "20") (pinfunction "CATHODE_A_20") (pintype "bidirectional"))
      (node (ref "DS5") (pin "9") (pinfunction "ANODE_J_9") (pintype "bidirectional"))
      (node (ref "DS6") (pin "10") (pinfunction "ANODE_K_10") (pintype "bidirectional"))
      (node (ref "DS6") (pin "11") (pinfunction "CATHODE_K_11") (pintype "bidirectional"))
      (node (ref "DS6") (pin "12") (pinfunction "CATHODE_J_12") (pintype "bidirectional"))
      (node (ref "DS6") (pin "13") (pinfunction "CATHODE_H_13") (pintype "bidirectional"))
      (node (ref "DS6") (pin "14") (pinfunction "CATHODE_G_14") (pintype "bidirectional"))
      (node (ref "DS6") (pin "15") (pinfunction "CATHODE_F_15") (pintype "bidirectional"))
      (node (ref "DS6") (pin "16") (pinfunction "CATHODE_E_16") (pintype "bidirectional"))
      (node (ref "DS6") (pin "17") (pinfunction "CATHODE_D_17") (pintype "bidirectional"))
      (node (ref "DS6") (pin "18") (pinfunction "CATHODE_C_18") (pintype "bidirectional"))
      (node (ref "DS6") (pin "19") (pinfunction "CATHODE_B_19") (pintype "bidirectional"))
      (node (ref "DS6") (pin "20") (pinfunction "CATHODE_A_20") (pintype "bidirectional"))
      (node (ref "DS6") (pin "9") (pinfunction "ANODE_J_9") (pintype "bidirectional"))
      (node (ref "DS7") (pin "10") (pinfunction "ANODE_K_10") (pintype "bidirectional"))
      (node (ref "DS7") (pin "11") (pinfunction "CATHODE_K_11") (pintype "bidirectional"))
      (node (ref "DS7") (pin "12") (pinfunction "CATHODE_J_12") (pintype "bidirectional"))
      (node (ref "DS7") (pin "13") (pinfunction "CATHODE_H_13") (pintype "bidirectional"))
      (node (ref "DS7") (pin "14") (pinfunction "CATHODE_G_14") (pintype "bidirectional"))
      (node (ref "DS7") (pin "15") (pinfunction "CATHODE_F_15") (pintype "bidirectional"))
      (node (ref "DS7") (pin "16") (pinfunction "CATHODE_E_16") (pintype "bidirectional"))
      (node (ref "DS7") (pin "17") (pinfunction "CATHODE_D_17") (pintype "bidirectional"))
      (node (ref "DS7") (pin "18") (pinfunction "CATHODE_C_18") (pintype "bidirectional"))
      (node (ref "DS7") (pin "19") (pinfunction "CATHODE_B_19") (pintype "bidirectional"))
      (node (ref "DS7") (pin "20") (pinfunction "CATHODE_A_20") (pintype "bidirectional"))
      (node (ref "DS7") (pin "9") (pinfunction "ANODE_J_9") (pintype "bidirectional"))
      (node (ref "DS8") (pin "10") (pinfunction "ANODE_K_10") (pintype "bidirectional"))
      (node (ref "DS8") (pin "11") (pinfunction "CATHODE_K_11") (pintype "bidirectional"))
      (node (ref "DS8") (pin "12") (pinfunction "CATHODE_J_12") (pintype "bidirectional"))
      (node (ref "DS8") (pin "13") (pinfunction "CATHODE_H_13") (pintype "bidirectional"))
      (node (ref "DS8") (pin "14") (pinfunction "CATHODE_G_14") (pintype "bidirectional"))
      (node (ref "DS8") (pin "15") (pinfunction "CATHODE_F_15") (pintype "bidirectional"))
      (node (ref "DS8") (pin "16") (pinfunction "CATHODE_E_16") (pintype "bidirectional"))
      (node (ref "DS8") (pin "17") (pinfunction "CATHODE_D_17") (pintype "bidirectional"))
      (node (ref "DS8") (pin "18") (pinfunction "CATHODE_C_18") (pintype "bidirectional"))
      (node (ref "DS8") (pin "19") (pinfunction "CATHODE_B_19") (pintype "bidirectional"))
      (node (ref "DS8") (pin "20") (pinfunction "CATHODE_A_20") (pintype "bidirectional"))
      (node (ref "DS8") (pin "9") (pinfunction "ANODE_J_9") (pintype "bidirectional"))
      (node (ref "DS9") (pin "10") (pinfunction "ANODE_K_10") (pintype "bidirectional"))
      (node (ref "DS9") (pin "11") (pinfunction "CATHODE_K_11") (pintype "bidirectional"))
      (node (ref "DS9") (pin "12") (pinfunction "CATHODE_J_12") (pintype "bidirectional"))
      (node (ref "DS9") (pin "13") (pinfunction "CATHODE_H_13") (pintype "bidirectional"))
      (node (ref "DS9") (pin "14") (pinfunction "CATHODE_G_14") (pintype "bidirectional"))
      (node (ref "DS9") (pin "15") (pinfunction "CATHODE_F_15") (pintype "bidirectional"))
      (node (ref "DS9") (pin "16") (pinfunction "CATHODE_E_16") (pintype "bidirectional"))
      (node (ref "DS9") (pin "17") (pinfunction "CATHODE_D_17") (pintype "bidirectional"))
      (node (ref "DS9") (pin "18") (pinfunction "CATHODE_C_18") (pintype "bidirectional"))
      (node (ref "DS9") (pin "19") (pinfunction "CATHODE_B_19") (pintype "bidirectional"))
      (node (ref "DS9") (pin "20") (pinfunction "CATHODE_A_20") (pintype "bidirectional"))
      (node (ref "DS9") (pin "9") (pinfunction "ANODE_J_9") (pintype "bidirectional"))
      (node (ref "IMM") (pin "10") (pinfunction "GND_10") (pintype "unspecified"))
      (node (ref "IN-SYSTEM") (pin "1") (pinfunction "1_1") (pintype "unspecified"))
      (node (ref "IR") (pin "10") (pinfunction "GND_10") (pintype "unspecified"))
      (node (ref "J1") (pin "C1") (pinfunction "C1_C1") (pintype "bidirectional"))
      (node (ref "J1") (pin "C2") (pinfunction "C2_C2") (pintype "bidirectional"))
      (node (ref "J1") (pin "C32") (pinfunction "C32_C32") (pintype "bidirectional"))
      (node (ref "J1") (pin "MH1") (pinfunction "MH1_MH1") (pintype "bidirectional"))
      (node (ref "J1") (pin "MH2") (pinfunction "MH2_MH2") (pintype "bidirectional"))
      (node (ref "J2") (pin "A20") (pinfunction "A20_A20") (pintype "bidirectional"))
      (node (ref "J2") (pin "A21") (pinfunction "A21_A21") (pintype "bidirectional"))
      (node (ref "J2") (pin "A22") (pinfunction "A22_A22") (pintype "bidirectional"))
      (node (ref "J2") (pin "A23") (pinfunction "A23_A23") (pintype "bidirectional"))
      (node (ref "J2") (pin "C1") (pinfunction "C1_C1") (pintype "bidirectional"))
      (node (ref "J2") (pin "C2") (pinfunction "C2_C2") (pintype "bidirectional"))
      (node (ref "J2") (pin "C20") (pinfunction "C20_C20") (pintype "bidirectional"))
      (node (ref "J2") (pin "C21") (pinfunction "C21_C21") (pintype "bidirectional"))
      (node (ref "J2") (pin "C23") (pinfunction "C23_C23") (pintype "bidirectional"))
      (node (ref "J2") (pin "C32") (pinfunction "C32_C32") (pintype "bidirectional"))
      (node (ref "J2") (pin "MH1") (pinfunction "MH1_MH1") (pintype "bidirectional"))
      (node (ref "J2") (pin "MH2") (pinfunction "MH2_MH2") (pintype "bidirectional"))
      (node (ref "ON") (pin "2") (pinfunction "2_2") (pintype "unspecified"))
      (node (ref "PLA") (pin "1") (pinfunction "I/CLK_1") (pintype "unspecified"))
      (node (ref "PLA") (pin "10") (pinfunction "GND_10") (pintype "unspecified"))
      (node (ref "PLA") (pin "11") (pinfunction "I9/OE#_11") (pintype "unspecified"))
      (node (ref "PWSW") (pin "4") (pinfunction "4_4") (pintype "unspecified"))
      (node (ref "PWSW") (pin "5") (pinfunction "5_5") (pintype "unspecified"))
      (node (ref "REG") (pin "2") (pinfunction "GND_2") (pintype "bidirectional"))
      (node (ref "RN1") (pin "1") (pinfunction "1_1") (pintype "bidirectional"))
      (node (ref "RN10") (pin "1") (pinfunction "1_1") (pintype "bidirectional"))
      (node (ref "RN12") (pin "1") (pinfunction "1_1") (pintype "bidirectional"))
      (node (ref "RN14") (pin "1") (pinfunction "1_1") (pintype "bidirectional"))
      (node (ref "RN16") (pin "1") (pinfunction "1_1") (pintype "bidirectional"))
      (node (ref "RN2") (pin "1") (pinfunction "1_1") (pintype "bidirectional"))
      (node (ref "RN3") (pin "1") (pinfunction "1_1") (pintype "bidirectional"))
      (node (ref "RN5") (pin "14") (pinfunction "14_14") (pintype "bidirectional"))
      (node (ref "RN5") (pin "15") (pinfunction "15_15") (pintype "bidirectional"))
      (node (ref "RN5") (pin "16") (pinfunction "16_16") (pintype "bidirectional"))
      (node (ref "RN6") (pin "1") (pinfunction "1_1") (pintype "bidirectional"))
      (node (ref "RN7") (pin "7") (pinfunction "7_7") (pintype "bidirectional"))
      (node (ref "RN7") (pin "8") (pinfunction "8_8") (pintype "bidirectional"))
      (node (ref "RST") (pin "3") (pinfunction "3_3") (pintype "unspecified"))
      (node (ref "RST") (pin "4") (pinfunction "4_4") (pintype "unspecified"))
      (node (ref "U1") (pin "7") (pinfunction "GND_7") (pintype "unspecified"))
      (node (ref "U10") (pin "11") (pinfunction "2CLK_11") (pintype "unspecified"))
      (node (ref "U10") (pin "12") (pinfunction "2D_12") (pintype "unspecified"))
      (node (ref "U10") (pin "2") (pinfunction "1D_2") (pintype "unspecified"))
      (node (ref "U10") (pin "3") (pinfunction "1CLK_3") (pintype "unspecified"))
      (node (ref "U10") (pin "7") (pinfunction "GND_7") (pintype "unspecified"))
      (node (ref "U11") (pin "1") (pinfunction "DIR_1") (pintype "unspecified"))
      (node (ref "U11") (pin "10") (pinfunction "GND_10") (pintype "unspecified"))
      (node (ref "U12") (pin "1") (pinfunction "DIR_1") (pintype "unspecified"))
      (node (ref "U12") (pin "10") (pinfunction "GND_10") (pintype "unspecified"))
      (node (ref "U12") (pin "17") (pinfunction "B2_17") (pintype "unspecified"))
      (node (ref "U12") (pin "18") (pinfunction "B1_18") (pintype "unspecified"))
      (node (ref "U13") (pin "1") (pinfunction "DIR_1") (pintype "unspecified"))
      (node (ref "U13") (pin "10") (pinfunction "GND_10") (pintype "unspecified"))
      (node (ref "U13") (pin "17") (pinfunction "B2_17") (pintype "unspecified"))
      (node (ref "U13") (pin "18") (pinfunction "B1_18") (pintype "unspecified"))
      (node (ref "U14") (pin "1") (pinfunction "DIR_1") (pintype "unspecified"))
      (node (ref "U14") (pin "10") (pinfunction "GND_10") (pintype "unspecified"))
      (node (ref "U14") (pin "17") (pinfunction "B2_17") (pintype "unspecified"))
      (node (ref "U14") (pin "18") (pinfunction "B1_18") (pintype "unspecified"))
      (node (ref "U14") (pin "19") (pinfunction "OE#_19") (pintype "unspecified"))
      (node (ref "U15") (pin "7") (pinfunction "GND_7") (pintype "unspecified"))
      (node (ref "U16") (pin "7") (pinfunction "GND_7") (pintype "unspecified"))
      (node (ref "U17") (pin "1") (pinfunction "1CLR#_1") (pintype "unspecified"))
      (node (ref "U17") (pin "2") (pinfunction "1D_2") (pintype "unspecified"))
      (node (ref "U17") (pin "3") (pinfunction "1CLK_3") (pintype "unspecified"))
      (node (ref "U17") (pin "7") (pinfunction "GND_7") (pintype "unspecified"))
      (node (ref "U18") (pin "7") (pinfunction "GND_7") (pintype "unspecified"))
      (node (ref "U19") (pin "1") (pinfunction "DIR_1") (pintype "unspecified"))
      (node (ref "U19") (pin "10") (pinfunction "GND_10") (pintype "unspecified"))
      (node (ref "U19") (pin "19") (pinfunction "OE#_19") (pintype "unspecified"))
      (node (ref "U2") (pin "1") (pinfunction "DIR_1") (pintype "unspecified"))
      (node (ref "U2") (pin "10") (pinfunction "GND_10") (pintype "unspecified"))
      (node (ref "U2") (pin "16") (pinfunction "B3_16") (pintype "unspecified"))
      (node (ref "U2") (pin "17") (pinfunction "B2_17") (pintype "unspecified"))
      (node (ref "U2") (pin "18") (pinfunction "B1_18") (pintype "unspecified"))
      (node (ref "U20") (pin "1") (pinfunction "DIR_1") (pintype "unspecified"))
      (node (ref "U20") (pin "10") (pinfunction "GND_10") (pintype "unspecified"))
      (node (ref "U20") (pin "19") (pinfunction "OE#_19") (pintype "unspecified"))
      (node (ref "U21") (pin "1") (pinfunction "DIR_1") (pintype "unspecified"))
      (node (ref "U21") (pin "10") (pinfunction "GND_10") (pintype "unspecified"))
      (node (ref "U22") (pin "1") (pinfunction "DIR_1") (pintype "unspecified"))
      (node (ref "U22") (pin "10") (pinfunction "GND_10") (pintype "unspecified"))
      (node (ref "U22") (pin "19") (pinfunction "OE#_19") (pintype "unspecified"))
      (node (ref "U23") (pin "1") (pinfunction "DIR_1") (pintype "unspecified"))
      (node (ref "U23") (pin "10") (pinfunction "GND_10") (pintype "unspecified"))
      (node (ref "U24") (pin "1") (pinfunction "DIR_1") (pintype "unspecified"))
      (node (ref "U24") (pin "10") (pinfunction "GND_10") (pintype "unspecified"))
      (node (ref "U24") (pin "19") (pinfunction "OE#_19") (pintype "unspecified"))
      (node (ref "U25") (pin "1") (pinfunction "DIR_1") (pintype "unspecified"))
      (node (ref "U25") (pin "10") (pinfunction "GND_10") (pintype "unspecified"))
      (node (ref "U26") (pin "1") (pinfunction "DIR_1") (pintype "unspecified"))
      (node (ref "U26") (pin "10") (pinfunction "GND_10") (pintype "unspecified"))
      (node (ref "U26") (pin "19") (pinfunction "OE#_19") (pintype "unspecified"))
      (node (ref "U27") (pin "1") (pinfunction "DIR_1") (pintype "unspecified"))
      (node (ref "U27") (pin "10") (pinfunction "GND_10") (pintype "unspecified"))
      (node (ref "U28") (pin "7") (pinfunction "GND_7") (pintype "unspecified"))
      (node (ref "U29") (pin "1") (pinfunction "DIR_1") (pintype "unspecified"))
      (node (ref "U29") (pin "10") (pinfunction "GND_10") (pintype "unspecified"))
      (node (ref "U3") (pin "1") (pinfunction "DIR_1") (pintype "unspecified"))
      (node (ref "U3") (pin "10") (pinfunction "GND_10") (pintype "unspecified"))
      (node (ref "U30") (pin "1") (pinfunction "DIR_1") (pintype "unspecified"))
      (node (ref "U30") (pin "10") (pinfunction "GND_10") (pintype "unspecified"))
      (node (ref "U31") (pin "1") (pinfunction "DIR_1") (pintype "unspecified"))
      (node (ref "U31") (pin "10") (pinfunction "GND_10") (pintype "unspecified"))
      (node (ref "U31") (pin "19") (pinfunction "OE#_19") (pintype "unspecified"))
      (node (ref "U32") (pin "1") (pinfunction "1OE#_1") (pintype "unspecified"))
      (node (ref "U32") (pin "10") (pinfunction "GND_10") (pintype "unspecified"))
      (node (ref "U32") (pin "11") (pinfunction "2A1_11") (pintype "unspecified"))
      (node (ref "U32") (pin "13") (pinfunction "2A2_13") (pintype "unspecified"))
      (node (ref "U32") (pin "15") (pinfunction "2A3_15") (pintype "unspecified"))
      (node (ref "U32") (pin "17") (pinfunction "2A4_17") (pintype "unspecified"))
      (node (ref "U32") (pin "6") (pinfunction "1A3_6") (pintype "unspecified"))
      (node (ref "U4") (pin "1") (pinfunction "DIR_1") (pintype "unspecified"))
      (node (ref "U4") (pin "10") (pinfunction "GND_10") (pintype "unspecified"))
      (node (ref "U4") (pin "16") (pinfunction "B3_16") (pintype "unspecified"))
      (node (ref "U4") (pin "17") (pinfunction "B2_17") (pintype "unspecified"))
      (node (ref "U4") (pin "18") (pinfunction "B1_18") (pintype "unspecified"))
      (node (ref "U5") (pin "1") (pinfunction "DIR_1") (pintype "unspecified"))
      (node (ref "U5") (pin "10") (pinfunction "GND_10") (pintype "unspecified"))
      (node (ref "U6") (pin "1") (pinfunction "DIR_1") (pintype "unspecified"))
      (node (ref "U6") (pin "10") (pinfunction "GND_10") (pintype "unspecified"))
      (node (ref "U6") (pin "16") (pinfunction "B3_16") (pintype "unspecified"))
      (node (ref "U6") (pin "17") (pinfunction "B2_17") (pintype "unspecified"))
      (node (ref "U6") (pin "18") (pinfunction "B1_18") (pintype "unspecified"))
      (node (ref "U6") (pin "19") (pinfunction "OE#_19") (pintype "unspecified"))
      (node (ref "U7") (pin "1") (pinfunction "DIR_1") (pintype "unspecified"))
      (node (ref "U7") (pin "10") (pinfunction "GND_10") (pintype "unspecified"))
      (node (ref "U7") (pin "19") (pinfunction "OE#_19") (pintype "unspecified"))
      (node (ref "U8") (pin "1") (pinfunction "1A_1") (pintype "unspecified"))
      (node (ref "U8") (pin "11") (pinfunction "5A_11") (pintype "unspecified"))
      (node (ref "U8") (pin "13") (pinfunction "6A_13") (pintype "unspecified"))
      (node (ref "U8") (pin "7") (pinfunction "GND_7") (pintype "unspecified"))
      (node (ref "U9") (pin "1") (pinfunction "1A_1") (pintype "unspecified"))
      (node (ref "U9") (pin "12") (pinfunction "4A_12") (pintype "unspecified"))
      (node (ref "U9") (pin "13") (pinfunction "4B_13") (pintype "unspecified"))
      (node (ref "U9") (pin "2") (pinfunction "1B_2") (pintype "unspecified"))
      (node (ref "U9") (pin "7") (pinfunction "GND_7") (pintype "unspecified"))
    )
    (net (code "57") (name "IBH0") (class "Default")
      (node (ref "J2") (pin "C6") (pinfunction "C6_C6") (pintype "bidirectional"))
      (node (ref "RN20") (pin "16") (pinfunction "16_16") (pintype "bidirectional"))
    )
    (net (code "58") (name "IBH1") (class "Default")
      (node (ref "J2") (pin "A6") (pinfunction "A6_A6") (pintype "bidirectional"))
      (node (ref "RN20") (pin "15") (pinfunction "15_15") (pintype "bidirectional"))
    )
    (net (code "59") (name "IBH2") (class "Default")
      (node (ref "J2") (pin "C5") (pinfunction "C5_C5") (pintype "bidirectional"))
      (node (ref "RN20") (pin "14") (pinfunction "14_14") (pintype "bidirectional"))
    )
    (net (code "60") (name "IBH3") (class "Default")
      (node (ref "J2") (pin "A5") (pinfunction "A5_A5") (pintype "bidirectional"))
      (node (ref "RN20") (pin "13") (pinfunction "13_13") (pintype "bidirectional"))
    )
    (net (code "61") (name "IBH4") (class "Default")
      (node (ref "J2") (pin "C4") (pinfunction "C4_C4") (pintype "bidirectional"))
      (node (ref "RN20") (pin "12") (pinfunction "12_12") (pintype "bidirectional"))
    )
    (net (code "62") (name "IBH5") (class "Default")
      (node (ref "J2") (pin "A4") (pinfunction "A4_A4") (pintype "bidirectional"))
      (node (ref "RN20") (pin "11") (pinfunction "11_11") (pintype "bidirectional"))
    )
    (net (code "63") (name "IBH6") (class "Default")
      (node (ref "J2") (pin "C3") (pinfunction "C3_C3") (pintype "bidirectional"))
      (node (ref "RN20") (pin "10") (pinfunction "10_10") (pintype "bidirectional"))
    )
    (net (code "64") (name "IBH7") (class "Default")
      (node (ref "J2") (pin "A3") (pinfunction "A3_A3") (pintype "bidirectional"))
      (node (ref "RN20") (pin "9") (pinfunction "9_9") (pintype "bidirectional"))
    )
    (net (code "65") (name "IBHIOE") (class "Default")
      (node (ref "J1") (pin "A8") (pinfunction "A8_A8") (pintype "bidirectional"))
      (node (ref "RN23") (pin "9") (pinfunction "9_9") (pintype "bidirectional"))
    )
    (net (code "66") (name "IBL0") (class "Default")
      (node (ref "J2") (pin "C10") (pinfunction "C10_C10") (pintype "bidirectional"))
      (node (ref "RN21") (pin "16") (pinfunction "16_16") (pintype "bidirectional"))
    )
    (net (code "67") (name "IBL1") (class "Default")
      (node (ref "J2") (pin "A10") (pinfunction "A10_A10") (pintype "bidirectional"))
      (node (ref "RN21") (pin "15") (pinfunction "15_15") (pintype "bidirectional"))
    )
    (net (code "68") (name "IBL2") (class "Default")
      (node (ref "J2") (pin "C9") (pinfunction "C9_C9") (pintype "bidirectional"))
      (node (ref "RN21") (pin "14") (pinfunction "14_14") (pintype "bidirectional"))
    )
    (net (code "69") (name "IBL3") (class "Default")
      (node (ref "J2") (pin "A9") (pinfunction "A9_A9") (pintype "bidirectional"))
      (node (ref "RN21") (pin "13") (pinfunction "13_13") (pintype "bidirectional"))
    )
    (net (code "70") (name "IBL4") (class "Default")
      (node (ref "J2") (pin "C8") (pinfunction "C8_C8") (pintype "bidirectional"))
      (node (ref "RN21") (pin "12") (pinfunction "12_12") (pintype "bidirectional"))
    )
    (net (code "71") (name "IBL5") (class "Default")
      (node (ref "J2") (pin "A8") (pinfunction "A8_A8") (pintype "bidirectional"))
      (node (ref "RN21") (pin "11") (pinfunction "11_11") (pintype "bidirectional"))
    )
    (net (code "72") (name "IBL6") (class "Default")
      (node (ref "J2") (pin "C7") (pinfunction "C7_C7") (pintype "bidirectional"))
      (node (ref "RN21") (pin "10") (pinfunction "10_10") (pintype "bidirectional"))
    )
    (net (code "73") (name "IBL7") (class "Default")
      (node (ref "J2") (pin "A7") (pinfunction "A7_A7") (pintype "bidirectional"))
      (node (ref "RN21") (pin "9") (pinfunction "9_9") (pintype "bidirectional"))
    )
    (net (code "74") (name "IBLIOE") (class "Default")
      (node (ref "J1") (pin "A5") (pinfunction "A5_A5") (pintype "bidirectional"))
      (node (ref "RN22") (pin "16") (pinfunction "16_16") (pintype "bidirectional"))
    )
    (net (code "75") (name "IMF") (class "Default")
      (node (ref "DM0") (pin "6") (pinfunction "A6_6") (pintype "unspecified"))
      (node (ref "DM1") (pin "6") (pinfunction "A6_6") (pintype "unspecified"))
      (node (ref "DM2") (pin "6") (pinfunction "A6_6") (pintype "unspecified"))
      (node (ref "DM3") (pin "6") (pinfunction "A6_6") (pintype "unspecified"))
      (node (ref "J2") (pin "A19") (pinfunction "A19_A19") (pintype "bidirectional"))
      (node (ref "R34") (pin "2") (pinfunction "2_2") (pintype "unspecified"))
    )
    (net (code "76") (name "IMMHOE") (class "Default")
      (node (ref "RN16") (pin "8") (pinfunction "8_8") (pintype "bidirectional"))
      (node (ref "U26") (pin "12") (pinfunction "B7_12") (pintype "unspecified"))
      (node (ref "U27") (pin "8") (pinfunction "A7_8") (pintype "unspecified"))
      (node (ref "U28") (pin "12") (pinfunction "4A_12") (pintype "unspecified"))
      (node (ref "U28") (pin "13") (pinfunction "4B_13") (pintype "unspecified"))
    )
    (net (code "77") (name "IMMLOE") (class "Default")
      (node (ref "RN16") (pin "7") (pinfunction "7_7") (pintype "bidirectional"))
      (node (ref "U26") (pin "13") (pinfunction "B6_13") (pintype "unspecified"))
      (node (ref "U27") (pin "7") (pinfunction "A6_7") (pintype "unspecified"))
      (node (ref "U28") (pin "10") (pinfunction "3B_10") (pintype "unspecified"))
      (node (ref "U28") (pin "9") (pinfunction "3A_9") (pintype "unspecified"))
    )
    (net (code "78") (name "IR0") (class "Default")
      (node (ref "DM0") (pin "27") (pinfunction "A8_27") (pintype "unspecified"))
      (node (ref "DM1") (pin "27") (pinfunction "A8_27") (pintype "unspecified"))
      (node (ref "DM2") (pin "27") (pinfunction "A8_27") (pintype "unspecified"))
      (node (ref "DM3") (pin "27") (pinfunction "A8_27") (pintype "unspecified"))
      (node (ref "IR") (pin "2") (pinfunction "1Q_2") (pintype "unspecified"))
      (node (ref "U19") (pin "18") (pinfunction "B1_18") (pintype "unspecified"))
    )
    (net (code "79") (name "IR1") (class "Default")
      (node (ref "DM0") (pin "26") (pinfunction "A9_26") (pintype "unspecified"))
      (node (ref "DM1") (pin "26") (pinfunction "A9_26") (pintype "unspecified"))
      (node (ref "DM2") (pin "26") (pinfunction "A9_26") (pintype "unspecified"))
      (node (ref "DM3") (pin "26") (pinfunction "A9_26") (pintype "unspecified"))
      (node (ref "IR") (pin "5") (pinfunction "2Q_5") (pintype "unspecified"))
      (node (ref "U19") (pin "17") (pinfunction "B2_17") (pintype "unspecified"))
    )
    (net (code "80") (name "IR2") (class "Default")
      (node (ref "DM0") (pin "23") (pinfunction "A10_23") (pintype "unspecified"))
      (node (ref "DM1") (pin "23") (pinfunction "A10_23") (pintype "unspecified"))
      (node (ref "DM2") (pin "23") (pinfunction "A10_23") (pintype "unspecified"))
      (node (ref "DM3") (pin "23") (pinfunction "A10_23") (pintype "unspecified"))
      (node (ref "IR") (pin "6") (pinfunction "3Q_6") (pintype "unspecified"))
      (node (ref "U19") (pin "16") (pinfunction "B3_16") (pintype "unspecified"))
    )
    (net (code "81") (name "IR3") (class "Default")
      (node (ref "DM0") (pin "25") (pinfunction "A11_25") (pintype "unspecified"))
      (node (ref "DM1") (pin "25") (pinfunction "A11_25") (pintype "unspecified"))
      (node (ref "DM2") (pin "25") (pinfunction "A11_25") (pintype "unspecified"))
      (node (ref "DM3") (pin "25") (pinfunction "A11_25") (pintype "unspecified"))
      (node (ref "IR") (pin "9") (pinfunction "4Q_9") (pintype "unspecified"))
      (node (ref "U19") (pin "15") (pinfunction "B4_15") (pintype "unspecified"))
    )
    (net (code "82") (name "IR4") (class "Default")
      (node (ref "DM0") (pin "4") (pinfunction "A12_4") (pintype "unspecified"))
      (node (ref "DM1") (pin "4") (pinfunction "A12_4") (pintype "unspecified"))
      (node (ref "DM2") (pin "4") (pinfunction "A12_4") (pintype "unspecified"))
      (node (ref "DM3") (pin "4") (pinfunction "A12_4") (pintype "unspecified"))
      (node (ref "IR") (pin "12") (pinfunction "5Q_12") (pintype "unspecified"))
      (node (ref "U19") (pin "14") (pinfunction "B5_14") (pintype "unspecified"))
    )
    (net (code "83") (name "IR5") (class "Default")
      (node (ref "DM0") (pin "28") (pinfunction "A13_28") (pintype "unspecified"))
      (node (ref "DM1") (pin "28") (pinfunction "A13_28") (pintype "unspecified"))
      (node (ref "DM2") (pin "28") (pinfunction "A13_28") (pintype "unspecified"))
      (node (ref "DM3") (pin "28") (pinfunction "A13_28") (pintype "unspecified"))
      (node (ref "IR") (pin "15") (pinfunction "6Q_15") (pintype "unspecified"))
      (node (ref "U19") (pin "13") (pinfunction "B6_13") (pintype "unspecified"))
    )
    (net (code "84") (name "IR6") (class "Default")
      (node (ref "DM0") (pin "29") (pinfunction "A14_29") (pintype "unspecified"))
      (node (ref "DM1") (pin "29") (pinfunction "A14_29") (pintype "unspecified"))
      (node (ref "DM2") (pin "29") (pinfunction "A14_29") (pintype "unspecified"))
      (node (ref "DM3") (pin "29") (pinfunction "A14_29") (pintype "unspecified"))
      (node (ref "IR") (pin "16") (pinfunction "7Q_16") (pintype "unspecified"))
      (node (ref "U19") (pin "12") (pinfunction "B7_12") (pintype "unspecified"))
    )
    (net (code "85") (name "IR7") (class "Default")
      (node (ref "DM0") (pin "3") (pinfunction "A15_3") (pintype "unspecified"))
      (node (ref "DM1") (pin "3") (pinfunction "A15_3") (pintype "unspecified"))
      (node (ref "DM2") (pin "3") (pinfunction "A15_3") (pintype "unspecified"))
      (node (ref "DM3") (pin "3") (pinfunction "A15_3") (pintype "unspecified"))
      (node (ref "IR") (pin "19") (pinfunction "8Q_19") (pintype "unspecified"))
      (node (ref "U19") (pin "11") (pinfunction "B8_11") (pintype "unspecified"))
    )
    (net (code "86") (name "JAHLE") (class "Default")
      (node (ref "J2") (pin "A26") (pinfunction "A26_A26") (pintype "bidirectional"))
      (node (ref "RN22") (pin "15") (pinfunction "15_15") (pintype "bidirectional"))
    )
    (net (code "87") (name "JALLE") (class "Default")
      (node (ref "J2") (pin "A27") (pinfunction "A27_A27") (pintype "bidirectional"))
      (node (ref "RN22") (pin "14") (pinfunction "14_14") (pintype "bidirectional"))
    )
    (net (code "88") (name "Net-(C1-+)") (class "Default")
      (node (ref "C1") (pin "1") (pinfunction "+_1") (pintype "bidirectional"))
      (node (ref "PWSW") (pin "2") (pinfunction "2_2") (pintype "input"))
      (node (ref "REG") (pin "1") (pinfunction "VIN+_1") (pintype "bidirectional"))
    )
    (net (code "89") (name "Net-(CLK-Pad1)") (class "Default")
      (node (ref "CLK") (pin "1") (pinfunction "1_1") (pintype "unspecified"))
      (node (ref "CLK") (pin "2") (pinfunction "2_2") (pintype "unspecified"))
      (node (ref "R2") (pin "1") (pinfunction "1_1") (pintype "unspecified"))
      (node (ref "R3") (pin "2") (pinfunction "2_2") (pintype "unspecified"))
    )
    (net (code "90") (name "Net-(D2-A)") (class "Default")
      (node (ref "9V-12V-DC") (pin "1") (pinfunction "1_1") (pintype "bidirectional"))
      (node (ref "D1") (pin "2") (pinfunction "2_2") (pintype "unspecified"))
      (node (ref "D2") (pin "2") (pinfunction "A_2") (pintype "unspecified"))
    )
    (net (code "91") (name "Net-(D2-C)") (class "Default")
      (node (ref "D2") (pin "1") (pinfunction "C_1") (pintype "unspecified"))
      (node (ref "PWSW") (pin "1") (pinfunction "1_1") (pintype "input"))
    )
    (net (code "92") (name "Net-(DIR0-1D)") (class "Default")
      (node (ref "DIR0") (pin "3") (pinfunction "1D_3") (pintype "unspecified"))
      (node (ref "DM0") (pin "13") (pinfunction "DQ0_13") (pintype "unspecified"))
    )
    (net (code "93") (name "Net-(DIR0-2D)") (class "Default")
      (node (ref "DIR0") (pin "4") (pinfunction "2D_4") (pintype "unspecified"))
      (node (ref "DM0") (pin "14") (pinfunction "DQ1_14") (pintype "unspecified"))
    )
    (net (code "94") (name "Net-(DIR0-3D)") (class "Default")
      (node (ref "DIR0") (pin "7") (pinfunction "3D_7") (pintype "unspecified"))
      (node (ref "DM0") (pin "15") (pinfunction "DQ2_15") (pintype "unspecified"))
    )
    (net (code "95") (name "Net-(DIR0-4D)") (class "Default")
      (node (ref "DIR0") (pin "8") (pinfunction "4D_8") (pintype "unspecified"))
      (node (ref "DM0") (pin "17") (pinfunction "DQ3_17") (pintype "unspecified"))
    )
    (net (code "96") (name "Net-(DIR0-5D)") (class "Default")
      (node (ref "DIR0") (pin "13") (pinfunction "5D_13") (pintype "unspecified"))
      (node (ref "DM0") (pin "18") (pinfunction "DQ4_18") (pintype "unspecified"))
    )
    (net (code "97") (name "Net-(DIR0-6D)") (class "Default")
      (node (ref "DIR0") (pin "14") (pinfunction "6D_14") (pintype "unspecified"))
      (node (ref "DM0") (pin "19") (pinfunction "DQ5_19") (pintype "unspecified"))
    )
    (net (code "98") (name "Net-(DIR0-7D)") (class "Default")
      (node (ref "DIR0") (pin "17") (pinfunction "7D_17") (pintype "unspecified"))
      (node (ref "DM0") (pin "20") (pinfunction "DQ6_20") (pintype "unspecified"))
    )
    (net (code "99") (name "Net-(DIR0-8D)") (class "Default")
      (node (ref "DIR0") (pin "18") (pinfunction "8D_18") (pintype "unspecified"))
      (node (ref "DM0") (pin "21") (pinfunction "DQ7_21") (pintype "unspecified"))
    )
    (net (code "100") (name "Net-(DIR1-1D)") (class "Default")
      (node (ref "DIR1") (pin "3") (pinfunction "1D_3") (pintype "unspecified"))
      (node (ref "DM1") (pin "13") (pinfunction "DQ0_13") (pintype "unspecified"))
    )
    (net (code "101") (name "Net-(DIR1-2D)") (class "Default")
      (node (ref "DIR1") (pin "4") (pinfunction "2D_4") (pintype "unspecified"))
      (node (ref "DM1") (pin "14") (pinfunction "DQ1_14") (pintype "unspecified"))
    )
    (net (code "102") (name "Net-(DIR1-3D)") (class "Default")
      (node (ref "DIR1") (pin "7") (pinfunction "3D_7") (pintype "unspecified"))
      (node (ref "DM1") (pin "15") (pinfunction "DQ2_15") (pintype "unspecified"))
    )
    (net (code "103") (name "Net-(DIR1-4D)") (class "Default")
      (node (ref "DIR1") (pin "8") (pinfunction "4D_8") (pintype "unspecified"))
      (node (ref "DM1") (pin "17") (pinfunction "DQ3_17") (pintype "unspecified"))
    )
    (net (code "104") (name "Net-(DIR1-5D)") (class "Default")
      (node (ref "DIR1") (pin "13") (pinfunction "5D_13") (pintype "unspecified"))
      (node (ref "DM1") (pin "18") (pinfunction "DQ4_18") (pintype "unspecified"))
    )
    (net (code "105") (name "Net-(DIR1-6D)") (class "Default")
      (node (ref "DIR1") (pin "14") (pinfunction "6D_14") (pintype "unspecified"))
      (node (ref "DM1") (pin "19") (pinfunction "DQ5_19") (pintype "unspecified"))
    )
    (net (code "106") (name "Net-(DIR1-7D)") (class "Default")
      (node (ref "DIR1") (pin "17") (pinfunction "7D_17") (pintype "unspecified"))
      (node (ref "DM1") (pin "20") (pinfunction "DQ6_20") (pintype "unspecified"))
    )
    (net (code "107") (name "Net-(DIR1-8D)") (class "Default")
      (node (ref "DIR1") (pin "18") (pinfunction "8D_18") (pintype "unspecified"))
      (node (ref "DM1") (pin "21") (pinfunction "DQ7_21") (pintype "unspecified"))
    )
    (net (code "108") (name "Net-(DIR2-1D)") (class "Default")
      (node (ref "DIR2") (pin "3") (pinfunction "1D_3") (pintype "unspecified"))
      (node (ref "DM2") (pin "13") (pinfunction "DQ0_13") (pintype "unspecified"))
    )
    (net (code "109") (name "Net-(DIR2-2D)") (class "Default")
      (node (ref "DIR2") (pin "4") (pinfunction "2D_4") (pintype "unspecified"))
      (node (ref "DM2") (pin "14") (pinfunction "DQ1_14") (pintype "unspecified"))
    )
    (net (code "110") (name "Net-(DIR2-3D)") (class "Default")
      (node (ref "DIR2") (pin "7") (pinfunction "3D_7") (pintype "unspecified"))
      (node (ref "DM2") (pin "15") (pinfunction "DQ2_15") (pintype "unspecified"))
    )
    (net (code "111") (name "Net-(DIR2-4D)") (class "Default")
      (node (ref "DIR2") (pin "8") (pinfunction "4D_8") (pintype "unspecified"))
      (node (ref "DM2") (pin "17") (pinfunction "DQ3_17") (pintype "unspecified"))
    )
    (net (code "112") (name "Net-(DIR2-5D)") (class "Default")
      (node (ref "DIR2") (pin "13") (pinfunction "5D_13") (pintype "unspecified"))
      (node (ref "DM2") (pin "18") (pinfunction "DQ4_18") (pintype "unspecified"))
    )
    (net (code "113") (name "Net-(DIR2-6D)") (class "Default")
      (node (ref "DIR2") (pin "14") (pinfunction "6D_14") (pintype "unspecified"))
      (node (ref "DM2") (pin "19") (pinfunction "DQ5_19") (pintype "unspecified"))
    )
    (net (code "114") (name "Net-(DIR2-7D)") (class "Default")
      (node (ref "DIR2") (pin "17") (pinfunction "7D_17") (pintype "unspecified"))
      (node (ref "DM2") (pin "20") (pinfunction "DQ6_20") (pintype "unspecified"))
    )
    (net (code "115") (name "Net-(DIR2-8D)") (class "Default")
      (node (ref "DIR2") (pin "18") (pinfunction "8D_18") (pintype "unspecified"))
      (node (ref "DM2") (pin "21") (pinfunction "DQ7_21") (pintype "unspecified"))
    )
    (net (code "116") (name "Net-(DIR3-1D)") (class "Default")
      (node (ref "DIR3") (pin "3") (pinfunction "1D_3") (pintype "unspecified"))
      (node (ref "DM3") (pin "13") (pinfunction "DQ0_13") (pintype "unspecified"))
    )
    (net (code "117") (name "Net-(DIR3-2D)") (class "Default")
      (node (ref "DIR3") (pin "4") (pinfunction "2D_4") (pintype "unspecified"))
      (node (ref "DM3") (pin "14") (pinfunction "DQ1_14") (pintype "unspecified"))
    )
    (net (code "118") (name "Net-(DIR3-3D)") (class "Default")
      (node (ref "DIR3") (pin "7") (pinfunction "3D_7") (pintype "unspecified"))
      (node (ref "DM3") (pin "15") (pinfunction "DQ2_15") (pintype "unspecified"))
    )
    (net (code "119") (name "Net-(DIR3-4D)") (class "Default")
      (node (ref "DIR3") (pin "8") (pinfunction "4D_8") (pintype "unspecified"))
      (node (ref "DM3") (pin "17") (pinfunction "DQ3_17") (pintype "unspecified"))
    )
    (net (code "120") (name "Net-(DIR3-5D)") (class "Default")
      (node (ref "DIR3") (pin "13") (pinfunction "5D_13") (pintype "unspecified"))
      (node (ref "DM3") (pin "18") (pinfunction "DQ4_18") (pintype "unspecified"))
    )
    (net (code "121") (name "Net-(DIR3-6D)") (class "Default")
      (node (ref "DIR3") (pin "14") (pinfunction "6D_14") (pintype "unspecified"))
      (node (ref "DM3") (pin "19") (pinfunction "DQ5_19") (pintype "unspecified"))
    )
    (net (code "122") (name "Net-(DIR3-7D)") (class "Default")
      (node (ref "DIR3") (pin "17") (pinfunction "7D_17") (pintype "unspecified"))
      (node (ref "DM3") (pin "20") (pinfunction "DQ6_20") (pintype "unspecified"))
    )
    (net (code "123") (name "Net-(DIR3-8D)") (class "Default")
      (node (ref "DIR3") (pin "18") (pinfunction "8D_18") (pintype "unspecified"))
      (node (ref "DM3") (pin "21") (pinfunction "DQ7_21") (pintype "unspecified"))
    )
    (net (code "124") (name "Net-(DM0-A16)") (class "Default")
      (node (ref "DM0") (pin "2") (pinfunction "A16_2") (pintype "unspecified"))
      (node (ref "DM0-A16") (pin "2") (pinfunction "2_2") (pintype "unspecified"))
    )
    (net (code "125") (name "Net-(DM0-A16-Pad3)") (class "Default")
      (node (ref "DM0-A16") (pin "3") (pinfunction "3_3") (pintype "unspecified"))
      (node (ref "R26") (pin "2") (pinfunction "2_2") (pintype "unspecified"))
    )
    (net (code "126") (name "Net-(DM0-A17)") (class "Default")
      (node (ref "DM0") (pin "30") (pinfunction "A17_30") (pintype "unspecified"))
      (node (ref "DM0-A17") (pin "2") (pinfunction "2_2") (pintype "unspecified"))
    )
    (net (code "127") (name "Net-(DM0-A17-Pad1)") (class "Default")
      (node (ref "DM0-A17") (pin "1") (pinfunction "1_1") (pintype "unspecified"))
      (node (ref "R27") (pin "1") (pinfunction "1_1") (pintype "unspecified"))
    )
    (net (code "128") (name "Net-(DM0-A18-Pad3)") (class "Default")
      (node (ref "DM0-A18") (pin "3") (pinfunction "3_3") (pintype "unspecified"))
      (node (ref "R42") (pin "2") (pinfunction "2_2") (pintype "unspecified"))
    )
    (net (code "129") (name "Net-(DM0-NC)") (class "Default")
      (node (ref "DM0") (pin "1") (pinfunction "NC_1") (pintype "unspecified"))
      (node (ref "DM0-A18") (pin "2") (pinfunction "2_2") (pintype "unspecified"))
    )
    (net (code "130") (name "Net-(DM0-WE#)") (class "Default")
      (node (ref "DM0") (pin "31") (pinfunction "WE#_31") (pintype "unspecified"))
      (node (ref "R28") (pin "2") (pinfunction "2_2") (pintype "unspecified"))
    )
    (net (code "131") (name "Net-(DM1-A16)") (class "Default")
      (node (ref "DM1") (pin "2") (pinfunction "A16_2") (pintype "unspecified"))
      (node (ref "DM1-A16") (pin "2") (pinfunction "2_2") (pintype "unspecified"))
    )
    (net (code "132") (name "Net-(DM1-A16-Pad3)") (class "Default")
      (node (ref "DM1-A16") (pin "3") (pinfunction "3_3") (pintype "unspecified"))
      (node (ref "R23") (pin "2") (pinfunction "2_2") (pintype "unspecified"))
    )
    (net (code "133") (name "Net-(DM1-A17)") (class "Default")
      (node (ref "DM1") (pin "30") (pinfunction "A17_30") (pintype "unspecified"))
      (node (ref "DM1-A17") (pin "2") (pinfunction "2_2") (pintype "unspecified"))
    )
    (net (code "134") (name "Net-(DM1-A17-Pad1)") (class "Default")
      (node (ref "DM1-A17") (pin "1") (pinfunction "1_1") (pintype "unspecified"))
      (node (ref "R24") (pin "1") (pinfunction "1_1") (pintype "unspecified"))
    )
    (net (code "135") (name "Net-(DM1-A18-Pad3)") (class "Default")
      (node (ref "DM1-A18") (pin "3") (pinfunction "3_3") (pintype "unspecified"))
      (node (ref "R41") (pin "2") (pinfunction "2_2") (pintype "unspecified"))
    )
    (net (code "136") (name "Net-(DM1-NC)") (class "Default")
      (node (ref "DM1") (pin "1") (pinfunction "NC_1") (pintype "unspecified"))
      (node (ref "DM1-A18") (pin "2") (pinfunction "2_2") (pintype "unspecified"))
    )
    (net (code "137") (name "Net-(DM1-WE#)") (class "Default")
      (node (ref "DM1") (pin "31") (pinfunction "WE#_31") (pintype "unspecified"))
      (node (ref "R25") (pin "2") (pinfunction "2_2") (pintype "unspecified"))
    )
    (net (code "138") (name "Net-(DM2-A16)") (class "Default")
      (node (ref "DM2") (pin "2") (pinfunction "A16_2") (pintype "unspecified"))
      (node (ref "DM2-A16") (pin "2") (pinfunction "2_2") (pintype "unspecified"))
    )
    (net (code "139") (name "Net-(DM2-A16-Pad3)") (class "Default")
      (node (ref "DM2-A16") (pin "3") (pinfunction "3_3") (pintype "unspecified"))
      (node (ref "R20") (pin "2") (pinfunction "2_2") (pintype "unspecified"))
    )
    (net (code "140") (name "Net-(DM2-A17)") (class "Default")
      (node (ref "DM2") (pin "30") (pinfunction "A17_30") (pintype "unspecified"))
      (node (ref "DM2-A17") (pin "2") (pinfunction "2_2") (pintype "unspecified"))
    )
    (net (code "141") (name "Net-(DM2-A17-Pad1)") (class "Default")
      (node (ref "DM2-A17") (pin "1") (pinfunction "1_1") (pintype "unspecified"))
      (node (ref "R21") (pin "1") (pinfunction "1_1") (pintype "unspecified"))
    )
    (net (code "142") (name "Net-(DM2-A18-Pad3)") (class "Default")
      (node (ref "DM2-A18") (pin "3") (pinfunction "3_3") (pintype "unspecified"))
      (node (ref "R40") (pin "2") (pinfunction "2_2") (pintype "unspecified"))
    )
    (net (code "143") (name "Net-(DM2-NC)") (class "Default")
      (node (ref "DM2") (pin "1") (pinfunction "NC_1") (pintype "unspecified"))
      (node (ref "DM2-A18") (pin "2") (pinfunction "2_2") (pintype "unspecified"))
    )
    (net (code "144") (name "Net-(DM2-WE#)") (class "Default")
      (node (ref "DM2") (pin "31") (pinfunction "WE#_31") (pintype "unspecified"))
      (node (ref "R22") (pin "2") (pinfunction "2_2") (pintype "unspecified"))
    )
    (net (code "145") (name "Net-(DM3-A16)") (class "Default")
      (node (ref "DM3") (pin "2") (pinfunction "A16_2") (pintype "unspecified"))
      (node (ref "DM3-A16") (pin "2") (pinfunction "2_2") (pintype "unspecified"))
    )
    (net (code "146") (name "Net-(DM3-A16-Pad3)") (class "Default")
      (node (ref "DM3-A16") (pin "3") (pinfunction "3_3") (pintype "unspecified"))
      (node (ref "R17") (pin "2") (pinfunction "2_2") (pintype "unspecified"))
    )
    (net (code "147") (name "Net-(DM3-A17)") (class "Default")
      (node (ref "DM3") (pin "30") (pinfunction "A17_30") (pintype "unspecified"))
      (node (ref "DM3-A17") (pin "2") (pinfunction "2_2") (pintype "unspecified"))
    )
    (net (code "148") (name "Net-(DM3-A17-Pad1)") (class "Default")
      (node (ref "DM3-A17") (pin "1") (pinfunction "1_1") (pintype "unspecified"))
      (node (ref "R18") (pin "1") (pinfunction "1_1") (pintype "unspecified"))
    )
    (net (code "149") (name "Net-(DM3-A18-Pad3)") (class "Default")
      (node (ref "DM3-A18") (pin "3") (pinfunction "3_3") (pintype "unspecified"))
      (node (ref "R39") (pin "2") (pinfunction "2_2") (pintype "unspecified"))
    )
    (net (code "150") (name "Net-(DM3-NC)") (class "Default")
      (node (ref "DM3") (pin "1") (pinfunction "NC_1") (pintype "unspecified"))
      (node (ref "DM3-A18") (pin "2") (pinfunction "2_2") (pintype "unspecified"))
    )
    (net (code "151") (name "Net-(DM3-WE#)") (class "Default")
      (node (ref "DM3") (pin "31") (pinfunction "WE#_31") (pintype "unspecified"))
      (node (ref "R19") (pin "2") (pinfunction "2_2") (pintype "unspecified"))
    )
    (net (code "152") (name "Net-(DS1-ANODE_A)") (class "Default")
      (node (ref "DS1") (pin "1") (pinfunction "ANODE_A_1") (pintype "bidirectional"))
      (node (ref "RN5") (pin "8") (pinfunction "8_8") (pintype "bidirectional"))
    )
    (net (code "153") (name "Net-(DS1-ANODE_B)") (class "Default")
      (node (ref "DS1") (pin "2") (pinfunction "ANODE_B_2") (pintype "bidirectional"))
      (node (ref "RN5") (pin "7") (pinfunction "7_7") (pintype "bidirectional"))
    )
    (net (code "154") (name "Net-(DS1-ANODE_C)") (class "Default")
      (node (ref "DS1") (pin "3") (pinfunction "ANODE_C_3") (pintype "bidirectional"))
      (node (ref "RN5") (pin "6") (pinfunction "6_6") (pintype "bidirectional"))
    )
    (net (code "155") (name "Net-(DS1-ANODE_D)") (class "Default")
      (node (ref "DS1") (pin "4") (pinfunction "ANODE_D_4") (pintype "bidirectional"))
      (node (ref "RN5") (pin "5") (pinfunction "5_5") (pintype "bidirectional"))
    )
    (net (code "156") (name "Net-(DS1-ANODE_E)") (class "Default")
      (node (ref "DS1") (pin "5") (pinfunction "ANODE_E_5") (pintype "bidirectional"))
      (node (ref "RN5") (pin "4") (pinfunction "4_4") (pintype "bidirectional"))
    )
    (net (code "157") (name "Net-(DS2-ANODE_C)") (class "Default")
      (node (ref "DS2") (pin "3") (pinfunction "ANODE_C_3") (pintype "bidirectional"))
      (node (ref "RN4") (pin "16") (pinfunction "16_16") (pintype "bidirectional"))
    )
    (net (code "158") (name "Net-(DS2-ANODE_D)") (class "Default")
      (node (ref "DS2") (pin "4") (pinfunction "ANODE_D_4") (pintype "bidirectional"))
      (node (ref "RN4") (pin "15") (pinfunction "15_15") (pintype "bidirectional"))
    )
    (net (code "159") (name "Net-(DS2-ANODE_E)") (class "Default")
      (node (ref "DS2") (pin "5") (pinfunction "ANODE_E_5") (pintype "bidirectional"))
      (node (ref "RN4") (pin "14") (pinfunction "14_14") (pintype "bidirectional"))
    )
    (net (code "160") (name "Net-(DS2-ANODE_F)") (class "Default")
      (node (ref "DS2") (pin "6") (pinfunction "ANODE_F_6") (pintype "bidirectional"))
      (node (ref "RN4") (pin "13") (pinfunction "13_13") (pintype "bidirectional"))
    )
    (net (code "161") (name "Net-(DS2-ANODE_G)") (class "Default")
      (node (ref "DS2") (pin "7") (pinfunction "ANODE_G_7") (pintype "bidirectional"))
      (node (ref "RN4") (pin "12") (pinfunction "12_12") (pintype "bidirectional"))
    )
    (net (code "162") (name "Net-(DS2-ANODE_H)") (class "Default")
      (node (ref "DS2") (pin "8") (pinfunction "ANODE_H_8") (pintype "bidirectional"))
      (node (ref "RN4") (pin "11") (pinfunction "11_11") (pintype "bidirectional"))
    )
    (net (code "163") (name "Net-(DS2-ANODE_J)") (class "Default")
      (node (ref "DS2") (pin "9") (pinfunction "ANODE_J_9") (pintype "bidirectional"))
      (node (ref "RN4") (pin "10") (pinfunction "10_10") (pintype "bidirectional"))
    )
    (net (code "164") (name "Net-(DS2-ANODE_K)") (class "Default")
      (node (ref "DS2") (pin "10") (pinfunction "ANODE_K_10") (pintype "bidirectional"))
      (node (ref "RN4") (pin "9") (pinfunction "9_9") (pintype "bidirectional"))
    )
    (net (code "165") (name "Net-(DS3-ANODE_A)") (class "Default")
      (node (ref "DS3") (pin "1") (pinfunction "ANODE_A_1") (pintype "bidirectional"))
      (node (ref "RN7") (pin "16") (pinfunction "16_16") (pintype "bidirectional"))
    )
    (net (code "166") (name "Net-(DS3-ANODE_B)") (class "Default")
      (node (ref "DS3") (pin "2") (pinfunction "ANODE_B_2") (pintype "bidirectional"))
      (node (ref "RN7") (pin "15") (pinfunction "15_15") (pintype "bidirectional"))
    )
    (net (code "167") (name "Net-(DS3-ANODE_C)") (class "Default")
      (node (ref "DS3") (pin "3") (pinfunction "ANODE_C_3") (pintype "bidirectional"))
      (node (ref "RN7") (pin "14") (pinfunction "14_14") (pintype "bidirectional"))
    )
    (net (code "168") (name "Net-(DS3-ANODE_D)") (class "Default")
      (node (ref "DS3") (pin "4") (pinfunction "ANODE_D_4") (pintype "bidirectional"))
      (node (ref "RN7") (pin "13") (pinfunction "13_13") (pintype "bidirectional"))
    )
    (net (code "169") (name "Net-(DS3-ANODE_E)") (class "Default")
      (node (ref "DS3") (pin "5") (pinfunction "ANODE_E_5") (pintype "bidirectional"))
      (node (ref "RN7") (pin "12") (pinfunction "12_12") (pintype "bidirectional"))
    )
    (net (code "170") (name "Net-(DS3-ANODE_F)") (class "Default")
      (node (ref "DS3") (pin "6") (pinfunction "ANODE_F_6") (pintype "bidirectional"))
      (node (ref "RN7") (pin "11") (pinfunction "11_11") (pintype "bidirectional"))
    )
    (net (code "171") (name "Net-(DS4-ANODE_C)") (class "Default")
      (node (ref "DS4") (pin "3") (pinfunction "ANODE_C_3") (pintype "bidirectional"))
      (node (ref "RN8") (pin "16") (pinfunction "16_16") (pintype "bidirectional"))
    )
    (net (code "172") (name "Net-(DS4-ANODE_D)") (class "Default")
      (node (ref "DS4") (pin "4") (pinfunction "ANODE_D_4") (pintype "bidirectional"))
      (node (ref "RN8") (pin "15") (pinfunction "15_15") (pintype "bidirectional"))
    )
    (net (code "173") (name "Net-(DS4-ANODE_E)") (class "Default")
      (node (ref "DS4") (pin "5") (pinfunction "ANODE_E_5") (pintype "bidirectional"))
      (node (ref "RN8") (pin "14") (pinfunction "14_14") (pintype "bidirectional"))
    )
    (net (code "174") (name "Net-(DS4-ANODE_F)") (class "Default")
      (node (ref "DS4") (pin "6") (pinfunction "ANODE_F_6") (pintype "bidirectional"))
      (node (ref "RN8") (pin "13") (pinfunction "13_13") (pintype "bidirectional"))
    )
    (net (code "175") (name "Net-(DS4-ANODE_G)") (class "Default")
      (node (ref "DS4") (pin "7") (pinfunction "ANODE_G_7") (pintype "bidirectional"))
      (node (ref "RN8") (pin "12") (pinfunction "12_12") (pintype "bidirectional"))
    )
    (net (code "176") (name "Net-(DS4-ANODE_H)") (class "Default")
      (node (ref "DS4") (pin "8") (pinfunction "ANODE_H_8") (pintype "bidirectional"))
      (node (ref "RN8") (pin "11") (pinfunction "11_11") (pintype "bidirectional"))
    )
    (net (code "177") (name "Net-(DS4-ANODE_J)") (class "Default")
      (node (ref "DS4") (pin "9") (pinfunction "ANODE_J_9") (pintype "bidirectional"))
      (node (ref "RN8") (pin "10") (pinfunction "10_10") (pintype "bidirectional"))
    )
    (net (code "178") (name "Net-(DS4-ANODE_K)") (class "Default")
      (node (ref "DS4") (pin "10") (pinfunction "ANODE_K_10") (pintype "bidirectional"))
      (node (ref "RN8") (pin "9") (pinfunction "9_9") (pintype "bidirectional"))
    )
    (net (code "179") (name "Net-(DS5-ANODE_A)") (class "Default")
      (node (ref "DS5") (pin "1") (pinfunction "ANODE_A_1") (pintype "bidirectional"))
      (node (ref "RN9") (pin "16") (pinfunction "16_16") (pintype "bidirectional"))
    )
    (net (code "180") (name "Net-(DS5-ANODE_B)") (class "Default")
      (node (ref "DS5") (pin "2") (pinfunction "ANODE_B_2") (pintype "bidirectional"))
      (node (ref "RN9") (pin "15") (pinfunction "15_15") (pintype "bidirectional"))
    )
    (net (code "181") (name "Net-(DS5-ANODE_C)") (class "Default")
      (node (ref "DS5") (pin "3") (pinfunction "ANODE_C_3") (pintype "bidirectional"))
      (node (ref "RN9") (pin "14") (pinfunction "14_14") (pintype "bidirectional"))
    )
    (net (code "182") (name "Net-(DS5-ANODE_D)") (class "Default")
      (node (ref "DS5") (pin "4") (pinfunction "ANODE_D_4") (pintype "bidirectional"))
      (node (ref "RN9") (pin "13") (pinfunction "13_13") (pintype "bidirectional"))
    )
    (net (code "183") (name "Net-(DS5-ANODE_E)") (class "Default")
      (node (ref "DS5") (pin "5") (pinfunction "ANODE_E_5") (pintype "bidirectional"))
      (node (ref "RN9") (pin "12") (pinfunction "12_12") (pintype "bidirectional"))
    )
    (net (code "184") (name "Net-(DS5-ANODE_F)") (class "Default")
      (node (ref "DS5") (pin "6") (pinfunction "ANODE_F_6") (pintype "bidirectional"))
      (node (ref "RN9") (pin "11") (pinfunction "11_11") (pintype "bidirectional"))
    )
    (net (code "185") (name "Net-(DS5-ANODE_G)") (class "Default")
      (node (ref "DS5") (pin "7") (pinfunction "ANODE_G_7") (pintype "bidirectional"))
      (node (ref "RN9") (pin "10") (pinfunction "10_10") (pintype "bidirectional"))
    )
    (net (code "186") (name "Net-(DS5-ANODE_H)") (class "Default")
      (node (ref "DS5") (pin "8") (pinfunction "ANODE_H_8") (pintype "bidirectional"))
      (node (ref "RN9") (pin "9") (pinfunction "9_9") (pintype "bidirectional"))
    )
    (net (code "187") (name "Net-(DS6-ANODE_A)") (class "Default")
      (node (ref "DS6") (pin "1") (pinfunction "ANODE_A_1") (pintype "bidirectional"))
      (node (ref "RN11") (pin "16") (pinfunction "16_16") (pintype "bidirectional"))
    )
    (net (code "188") (name "Net-(DS6-ANODE_B)") (class "Default")
      (node (ref "DS6") (pin "2") (pinfunction "ANODE_B_2") (pintype "bidirectional"))
      (node (ref "RN11") (pin "15") (pinfunction "15_15") (pintype "bidirectional"))
    )
    (net (code "189") (name "Net-(DS6-ANODE_C)") (class "Default")
      (node (ref "DS6") (pin "3") (pinfunction "ANODE_C_3") (pintype "bidirectional"))
      (node (ref "RN11") (pin "14") (pinfunction "14_14") (pintype "bidirectional"))
    )
    (net (code "190") (name "Net-(DS6-ANODE_D)") (class "Default")
      (node (ref "DS6") (pin "4") (pinfunction "ANODE_D_4") (pintype "bidirectional"))
      (node (ref "RN11") (pin "13") (pinfunction "13_13") (pintype "bidirectional"))
    )
    (net (code "191") (name "Net-(DS6-ANODE_E)") (class "Default")
      (node (ref "DS6") (pin "5") (pinfunction "ANODE_E_5") (pintype "bidirectional"))
      (node (ref "RN11") (pin "12") (pinfunction "12_12") (pintype "bidirectional"))
    )
    (net (code "192") (name "Net-(DS6-ANODE_F)") (class "Default")
      (node (ref "DS6") (pin "6") (pinfunction "ANODE_F_6") (pintype "bidirectional"))
      (node (ref "RN11") (pin "11") (pinfunction "11_11") (pintype "bidirectional"))
    )
    (net (code "193") (name "Net-(DS6-ANODE_G)") (class "Default")
      (node (ref "DS6") (pin "7") (pinfunction "ANODE_G_7") (pintype "bidirectional"))
      (node (ref "RN11") (pin "10") (pinfunction "10_10") (pintype "bidirectional"))
    )
    (net (code "194") (name "Net-(DS6-ANODE_H)") (class "Default")
      (node (ref "DS6") (pin "8") (pinfunction "ANODE_H_8") (pintype "bidirectional"))
      (node (ref "RN11") (pin "9") (pinfunction "9_9") (pintype "bidirectional"))
    )
    (net (code "195") (name "Net-(DS7-ANODE_A)") (class "Default")
      (node (ref "DS7") (pin "1") (pinfunction "ANODE_A_1") (pintype "bidirectional"))
      (node (ref "RN13") (pin "16") (pinfunction "16_16") (pintype "bidirectional"))
    )
    (net (code "196") (name "Net-(DS7-ANODE_B)") (class "Default")
      (node (ref "DS7") (pin "2") (pinfunction "ANODE_B_2") (pintype "bidirectional"))
      (node (ref "RN13") (pin "15") (pinfunction "15_15") (pintype "bidirectional"))
    )
    (net (code "197") (name "Net-(DS7-ANODE_C)") (class "Default")
      (node (ref "DS7") (pin "3") (pinfunction "ANODE_C_3") (pintype "bidirectional"))
      (node (ref "RN13") (pin "14") (pinfunction "14_14") (pintype "bidirectional"))
    )
    (net (code "198") (name "Net-(DS7-ANODE_D)") (class "Default")
      (node (ref "DS7") (pin "4") (pinfunction "ANODE_D_4") (pintype "bidirectional"))
      (node (ref "RN13") (pin "13") (pinfunction "13_13") (pintype "bidirectional"))
    )
    (net (code "199") (name "Net-(DS7-ANODE_E)") (class "Default")
      (node (ref "DS7") (pin "5") (pinfunction "ANODE_E_5") (pintype "bidirectional"))
      (node (ref "RN13") (pin "12") (pinfunction "12_12") (pintype "bidirectional"))
    )
    (net (code "200") (name "Net-(DS7-ANODE_F)") (class "Default")
      (node (ref "DS7") (pin "6") (pinfunction "ANODE_F_6") (pintype "bidirectional"))
      (node (ref "RN13") (pin "11") (pinfunction "11_11") (pintype "bidirectional"))
    )
    (net (code "201") (name "Net-(DS7-ANODE_G)") (class "Default")
      (node (ref "DS7") (pin "7") (pinfunction "ANODE_G_7") (pintype "bidirectional"))
      (node (ref "RN13") (pin "10") (pinfunction "10_10") (pintype "bidirectional"))
    )
    (net (code "202") (name "Net-(DS7-ANODE_H)") (class "Default")
      (node (ref "DS7") (pin "8") (pinfunction "ANODE_H_8") (pintype "bidirectional"))
      (node (ref "RN13") (pin "9") (pinfunction "9_9") (pintype "bidirectional"))
    )
    (net (code "203") (name "Net-(DS8-ANODE_A)") (class "Default")
      (node (ref "DS8") (pin "1") (pinfunction "ANODE_A_1") (pintype "bidirectional"))
      (node (ref "RN15") (pin "16") (pinfunction "16_16") (pintype "bidirectional"))
    )
    (net (code "204") (name "Net-(DS8-ANODE_B)") (class "Default")
      (node (ref "DS8") (pin "2") (pinfunction "ANODE_B_2") (pintype "bidirectional"))
      (node (ref "RN15") (pin "15") (pinfunction "15_15") (pintype "bidirectional"))
    )
    (net (code "205") (name "Net-(DS8-ANODE_C)") (class "Default")
      (node (ref "DS8") (pin "3") (pinfunction "ANODE_C_3") (pintype "bidirectional"))
      (node (ref "RN15") (pin "14") (pinfunction "14_14") (pintype "bidirectional"))
    )
    (net (code "206") (name "Net-(DS8-ANODE_D)") (class "Default")
      (node (ref "DS8") (pin "4") (pinfunction "ANODE_D_4") (pintype "bidirectional"))
      (node (ref "RN15") (pin "13") (pinfunction "13_13") (pintype "bidirectional"))
    )
    (net (code "207") (name "Net-(DS8-ANODE_E)") (class "Default")
      (node (ref "DS8") (pin "5") (pinfunction "ANODE_E_5") (pintype "bidirectional"))
      (node (ref "RN15") (pin "12") (pinfunction "12_12") (pintype "bidirectional"))
    )
    (net (code "208") (name "Net-(DS8-ANODE_F)") (class "Default")
      (node (ref "DS8") (pin "6") (pinfunction "ANODE_F_6") (pintype "bidirectional"))
      (node (ref "RN15") (pin "11") (pinfunction "11_11") (pintype "bidirectional"))
    )
    (net (code "209") (name "Net-(DS8-ANODE_G)") (class "Default")
      (node (ref "DS8") (pin "7") (pinfunction "ANODE_G_7") (pintype "bidirectional"))
      (node (ref "RN15") (pin "10") (pinfunction "10_10") (pintype "bidirectional"))
    )
    (net (code "210") (name "Net-(DS8-ANODE_H)") (class "Default")
      (node (ref "DS8") (pin "8") (pinfunction "ANODE_H_8") (pintype "bidirectional"))
      (node (ref "RN15") (pin "9") (pinfunction "9_9") (pintype "bidirectional"))
    )
    (net (code "211") (name "Net-(DS9-ANODE_A)") (class "Default")
      (node (ref "DS9") (pin "1") (pinfunction "ANODE_A_1") (pintype "bidirectional"))
      (node (ref "RN17") (pin "16") (pinfunction "16_16") (pintype "bidirectional"))
    )
    (net (code "212") (name "Net-(DS9-ANODE_B)") (class "Default")
      (node (ref "DS9") (pin "2") (pinfunction "ANODE_B_2") (pintype "bidirectional"))
      (node (ref "RN17") (pin "15") (pinfunction "15_15") (pintype "bidirectional"))
    )
    (net (code "213") (name "Net-(DS9-ANODE_C)") (class "Default")
      (node (ref "DS9") (pin "3") (pinfunction "ANODE_C_3") (pintype "bidirectional"))
      (node (ref "RN17") (pin "14") (pinfunction "14_14") (pintype "bidirectional"))
    )
    (net (code "214") (name "Net-(DS9-ANODE_D)") (class "Default")
      (node (ref "DS9") (pin "4") (pinfunction "ANODE_D_4") (pintype "bidirectional"))
      (node (ref "RN17") (pin "13") (pinfunction "13_13") (pintype "bidirectional"))
    )
    (net (code "215") (name "Net-(DS9-ANODE_E)") (class "Default")
      (node (ref "DS9") (pin "5") (pinfunction "ANODE_E_5") (pintype "bidirectional"))
      (node (ref "RN17") (pin "12") (pinfunction "12_12") (pintype "bidirectional"))
    )
    (net (code "216") (name "Net-(DS9-ANODE_F)") (class "Default")
      (node (ref "DS9") (pin "6") (pinfunction "ANODE_F_6") (pintype "bidirectional"))
      (node (ref "RN17") (pin "11") (pinfunction "11_11") (pintype "bidirectional"))
    )
    (net (code "217") (name "Net-(DS9-ANODE_G)") (class "Default")
      (node (ref "DS9") (pin "7") (pinfunction "ANODE_G_7") (pintype "bidirectional"))
      (node (ref "RN17") (pin "10") (pinfunction "10_10") (pintype "bidirectional"))
    )
    (net (code "218") (name "Net-(DS9-ANODE_H)") (class "Default")
      (node (ref "DS9") (pin "8") (pinfunction "ANODE_H_8") (pintype "bidirectional"))
      (node (ref "RN17") (pin "9") (pinfunction "9_9") (pintype "bidirectional"))
    )
    (net (code "219") (name "Net-(IMM-1Q)") (class "Default")
      (node (ref "IMM") (pin "2") (pinfunction "1Q_2") (pintype "unspecified"))
      (node (ref "U29") (pin "11") (pinfunction "B8_11") (pintype "unspecified"))
      (node (ref "U30") (pin "11") (pinfunction "B8_11") (pintype "unspecified"))
      (node (ref "U31") (pin "11") (pinfunction "B8_11") (pintype "unspecified"))
    )
    (net (code "220") (name "Net-(IMM-2Q)") (class "Default")
      (node (ref "IMM") (pin "5") (pinfunction "2Q_5") (pintype "unspecified"))
      (node (ref "U29") (pin "12") (pinfunction "B7_12") (pintype "unspecified"))
      (node (ref "U30") (pin "12") (pinfunction "B7_12") (pintype "unspecified"))
      (node (ref "U31") (pin "12") (pinfunction "B7_12") (pintype "unspecified"))
    )
    (net (code "221") (name "Net-(IMM-3Q)") (class "Default")
      (node (ref "IMM") (pin "6") (pinfunction "3Q_6") (pintype "unspecified"))
      (node (ref "U29") (pin "13") (pinfunction "B6_13") (pintype "unspecified"))
      (node (ref "U30") (pin "13") (pinfunction "B6_13") (pintype "unspecified"))
      (node (ref "U31") (pin "13") (pinfunction "B6_13") (pintype "unspecified"))
    )
    (net (code "222") (name "Net-(IMM-4Q)") (class "Default")
      (node (ref "IMM") (pin "9") (pinfunction "4Q_9") (pintype "unspecified"))
      (node (ref "U29") (pin "14") (pinfunction "B5_14") (pintype "unspecified"))
      (node (ref "U30") (pin "14") (pinfunction "B5_14") (pintype "unspecified"))
      (node (ref "U31") (pin "14") (pinfunction "B5_14") (pintype "unspecified"))
    )
    (net (code "223") (name "Net-(IMM-5Q)") (class "Default")
      (node (ref "IMM") (pin "12") (pinfunction "5Q_12") (pintype "unspecified"))
      (node (ref "U29") (pin "15") (pinfunction "B4_15") (pintype "unspecified"))
      (node (ref "U30") (pin "15") (pinfunction "B4_15") (pintype "unspecified"))
      (node (ref "U31") (pin "15") (pinfunction "B4_15") (pintype "unspecified"))
    )
    (net (code "224") (name "Net-(IMM-6Q)") (class "Default")
      (node (ref "IMM") (pin "15") (pinfunction "6Q_15") (pintype "unspecified"))
      (node (ref "U29") (pin "16") (pinfunction "B3_16") (pintype "unspecified"))
      (node (ref "U30") (pin "16") (pinfunction "B3_16") (pintype "unspecified"))
      (node (ref "U31") (pin "16") (pinfunction "B3_16") (pintype "unspecified"))
    )
    (net (code "225") (name "Net-(IMM-7Q)") (class "Default")
      (node (ref "IMM") (pin "16") (pinfunction "7Q_16") (pintype "unspecified"))
      (node (ref "U29") (pin "17") (pinfunction "B2_17") (pintype "unspecified"))
      (node (ref "U30") (pin "17") (pinfunction "B2_17") (pintype "unspecified"))
      (node (ref "U31") (pin "17") (pinfunction "B2_17") (pintype "unspecified"))
    )
    (net (code "226") (name "Net-(IMM-8Q)") (class "Default")
      (node (ref "IMM") (pin "19") (pinfunction "8Q_19") (pintype "unspecified"))
      (node (ref "U29") (pin "18") (pinfunction "B1_18") (pintype "unspecified"))
      (node (ref "U30") (pin "18") (pinfunction "B1_18") (pintype "unspecified"))
      (node (ref "U31") (pin "18") (pinfunction "B1_18") (pintype "unspecified"))
    )
    (net (code "227") (name "Net-(IR-1D)") (class "Default")
      (node (ref "IR") (pin "3") (pinfunction "1D_3") (pintype "unspecified"))
      (node (ref "RN1") (pin "9") (pinfunction "9_9") (pintype "bidirectional"))
      (node (ref "U11") (pin "2") (pinfunction "A1_2") (pintype "unspecified"))
    )
    (net (code "228") (name "Net-(IR-2D)") (class "Default")
      (node (ref "IR") (pin "4") (pinfunction "2D_4") (pintype "unspecified"))
      (node (ref "RN1") (pin "8") (pinfunction "8_8") (pintype "bidirectional"))
      (node (ref "U11") (pin "3") (pinfunction "A2_3") (pintype "unspecified"))
    )
    (net (code "229") (name "Net-(IR-3D)") (class "Default")
      (node (ref "IR") (pin "7") (pinfunction "3D_7") (pintype "unspecified"))
      (node (ref "RN1") (pin "7") (pinfunction "7_7") (pintype "bidirectional"))
      (node (ref "U11") (pin "4") (pinfunction "A3_4") (pintype "unspecified"))
    )
    (net (code "230") (name "Net-(IR-4D)") (class "Default")
      (node (ref "IR") (pin "8") (pinfunction "4D_8") (pintype "unspecified"))
      (node (ref "RN1") (pin "6") (pinfunction "6_6") (pintype "bidirectional"))
      (node (ref "U11") (pin "5") (pinfunction "A4_5") (pintype "unspecified"))
    )
    (net (code "231") (name "Net-(IR-5D)") (class "Default")
      (node (ref "IR") (pin "13") (pinfunction "5D_13") (pintype "unspecified"))
      (node (ref "RN1") (pin "5") (pinfunction "5_5") (pintype "bidirectional"))
      (node (ref "U11") (pin "6") (pinfunction "A5_6") (pintype "unspecified"))
    )
    (net (code "232") (name "Net-(IR-6D)") (class "Default")
      (node (ref "IR") (pin "14") (pinfunction "6D_14") (pintype "unspecified"))
      (node (ref "RN1") (pin "4") (pinfunction "4_4") (pintype "bidirectional"))
      (node (ref "U11") (pin "7") (pinfunction "A6_7") (pintype "unspecified"))
    )
    (net (code "233") (name "Net-(IR-7D)") (class "Default")
      (node (ref "IR") (pin "17") (pinfunction "7D_17") (pintype "unspecified"))
      (node (ref "RN1") (pin "3") (pinfunction "3_3") (pintype "bidirectional"))
      (node (ref "U11") (pin "8") (pinfunction "A7_8") (pintype "unspecified"))
    )
    (net (code "234") (name "Net-(IR-8D)") (class "Default")
      (node (ref "IR") (pin "18") (pinfunction "8D_18") (pintype "unspecified"))
      (node (ref "RN1") (pin "2") (pinfunction "2_2") (pintype "bidirectional"))
      (node (ref "U11") (pin "9") (pinfunction "A8_9") (pintype "unspecified"))
    )
    (net (code "235") (name "Net-(ON-Pad1)") (class "Default")
      (node (ref "ON") (pin "1") (pinfunction "1_1") (pintype "unspecified"))
      (node (ref "R6") (pin "2") (pinfunction "2_2") (pintype "unspecified"))
    )
    (net (code "236") (name "Net-(R4-Pad1)") (class "Default")
      (node (ref "R4") (pin "1") (pinfunction "1_1") (pintype "unspecified"))
      (node (ref "R5") (pin "2") (pinfunction "2_2") (pintype "unspecified"))
      (node (ref "RST") (pin "1") (pinfunction "1_1") (pintype "unspecified"))
      (node (ref "RST") (pin "2") (pinfunction "2_2") (pintype "unspecified"))
    )
    (net (code "237") (name "Net-(S1-1_2_NO)") (class "Default")
      (node (ref "RN3") (pin "2") (pinfunction "2_2") (pintype "bidirectional"))
      (node (ref "S1") (pin "9") (pinfunction "1_2_NO_9") (pintype "bidirectional"))
      (node (ref "U4") (pin "13") (pinfunction "B6_13") (pintype "unspecified"))
    )
    (net (code "238") (name "Net-(S1-2_2_NO)") (class "Default")
      (node (ref "RN3") (pin "3") (pinfunction "3_3") (pintype "bidirectional"))
      (node (ref "S1") (pin "10") (pinfunction "2_2_NO_10") (pintype "bidirectional"))
      (node (ref "U4") (pin "14") (pinfunction "B5_14") (pintype "unspecified"))
    )
    (net (code "239") (name "Net-(S1-3_2_NO)") (class "Default")
      (node (ref "RN3") (pin "4") (pinfunction "4_4") (pintype "bidirectional"))
      (node (ref "S1") (pin "11") (pinfunction "3_2_NO_11") (pintype "bidirectional"))
      (node (ref "U4") (pin "15") (pinfunction "B4_15") (pintype "unspecified"))
    )
    (net (code "240") (name "Net-(S2-1_2_NO)") (class "Default")
      (node (ref "RN2") (pin "2") (pinfunction "2_2") (pintype "bidirectional"))
      (node (ref "S2") (pin "9") (pinfunction "1_2_NO_9") (pintype "bidirectional"))
      (node (ref "U5") (pin "11") (pinfunction "B8_11") (pintype "unspecified"))
    )
    (net (code "241") (name "Net-(S2-2_2_NO)") (class "Default")
      (node (ref "RN2") (pin "3") (pinfunction "3_3") (pintype "bidirectional"))
      (node (ref "S2") (pin "10") (pinfunction "2_2_NO_10") (pintype "bidirectional"))
      (node (ref "U5") (pin "12") (pinfunction "B7_12") (pintype "unspecified"))
    )
    (net (code "242") (name "Net-(S2-3_2_NO)") (class "Default")
      (node (ref "RN2") (pin "4") (pinfunction "4_4") (pintype "bidirectional"))
      (node (ref "S2") (pin "11") (pinfunction "3_2_NO_11") (pintype "bidirectional"))
      (node (ref "U5") (pin "13") (pinfunction "B6_13") (pintype "unspecified"))
    )
    (net (code "243") (name "Net-(S2-4_2_NO)") (class "Default")
      (node (ref "RN2") (pin "5") (pinfunction "5_5") (pintype "bidirectional"))
      (node (ref "S2") (pin "12") (pinfunction "4_2_NO_12") (pintype "bidirectional"))
      (node (ref "U5") (pin "14") (pinfunction "B5_14") (pintype "unspecified"))
    )
    (net (code "244") (name "Net-(S2-5_2_NO)") (class "Default")
      (node (ref "RN2") (pin "6") (pinfunction "6_6") (pintype "bidirectional"))
      (node (ref "S2") (pin "13") (pinfunction "5_2_NO_13") (pintype "bidirectional"))
      (node (ref "U5") (pin "15") (pinfunction "B4_15") (pintype "unspecified"))
    )
    (net (code "245") (name "Net-(S2-6_2_NO)") (class "Default")
      (node (ref "RN2") (pin "7") (pinfunction "7_7") (pintype "bidirectional"))
      (node (ref "S2") (pin "14") (pinfunction "6_2_NO_14") (pintype "bidirectional"))
      (node (ref "U5") (pin "16") (pinfunction "B3_16") (pintype "unspecified"))
    )
    (net (code "246") (name "Net-(S2-7_2_NO)") (class "Default")
      (node (ref "RN2") (pin "8") (pinfunction "8_8") (pintype "bidirectional"))
      (node (ref "S2") (pin "15") (pinfunction "7_2_NO_15") (pintype "bidirectional"))
      (node (ref "U5") (pin "17") (pinfunction "B2_17") (pintype "unspecified"))
    )
    (net (code "247") (name "Net-(S2-8_2_NO)") (class "Default")
      (node (ref "RN2") (pin "9") (pinfunction "9_9") (pintype "bidirectional"))
      (node (ref "S2") (pin "16") (pinfunction "8_2_NO_16") (pintype "bidirectional"))
      (node (ref "U5") (pin "18") (pinfunction "B1_18") (pintype "unspecified"))
    )
    (net (code "248") (name "Net-(S3-1_2_NO)") (class "Default")
      (node (ref "RN6") (pin "2") (pinfunction "2_2") (pintype "bidirectional"))
      (node (ref "S3") (pin "9") (pinfunction "1_2_NO_9") (pintype "bidirectional"))
      (node (ref "U13") (pin "11") (pinfunction "B8_11") (pintype "unspecified"))
    )
    (net (code "249") (name "Net-(S3-2_2_NO)") (class "Default")
      (node (ref "RN6") (pin "3") (pinfunction "3_3") (pintype "bidirectional"))
      (node (ref "S3") (pin "10") (pinfunction "2_2_NO_10") (pintype "bidirectional"))
      (node (ref "U13") (pin "12") (pinfunction "B7_12") (pintype "unspecified"))
    )
    (net (code "250") (name "Net-(S3-3_2_NO)") (class "Default")
      (node (ref "RN6") (pin "4") (pinfunction "4_4") (pintype "bidirectional"))
      (node (ref "S3") (pin "11") (pinfunction "3_2_NO_11") (pintype "bidirectional"))
      (node (ref "U13") (pin "13") (pinfunction "B6_13") (pintype "unspecified"))
    )
    (net (code "251") (name "Net-(S3-4_2_NO)") (class "Default")
      (node (ref "RN6") (pin "5") (pinfunction "5_5") (pintype "bidirectional"))
      (node (ref "S3") (pin "12") (pinfunction "4_2_NO_12") (pintype "bidirectional"))
      (node (ref "U13") (pin "14") (pinfunction "B5_14") (pintype "unspecified"))
    )
    (net (code "252") (name "Net-(S3-5_2_NO)") (class "Default")
      (node (ref "RN6") (pin "6") (pinfunction "6_6") (pintype "bidirectional"))
      (node (ref "S3") (pin "13") (pinfunction "5_2_NO_13") (pintype "bidirectional"))
      (node (ref "U13") (pin "15") (pinfunction "B4_15") (pintype "unspecified"))
    )
    (net (code "253") (name "Net-(S3-6_2_NO)") (class "Default")
      (node (ref "RN6") (pin "7") (pinfunction "7_7") (pintype "bidirectional"))
      (node (ref "S3") (pin "14") (pinfunction "6_2_NO_14") (pintype "bidirectional"))
      (node (ref "U13") (pin "16") (pinfunction "B3_16") (pintype "unspecified"))
    )
    (net (code "254") (name "Net-(U1-1A)") (class "Default")
      (node (ref "IN-SYSTEM") (pin "2") (pinfunction "2_2") (pintype "unspecified"))
      (node (ref "R1") (pin "1") (pinfunction "1_1") (pintype "unspecified"))
      (node (ref "U1") (pin "1") (pinfunction "1A_1") (pintype "unspecified"))
    )
    (net (code "255") (name "Net-(U1-1Y)") (class "Default")
      (node (ref "U1") (pin "2") (pinfunction "1Y_2") (pintype "unspecified"))
      (node (ref "U1") (pin "3") (pinfunction "2A_3") (pintype "unspecified"))
    )
    (net (code "256") (name "Net-(U1-4A)") (class "Default")
      (node (ref "C4") (pin "1") (pinfunction "1_1") (pintype "unspecified"))
      (node (ref "R5") (pin "1") (pinfunction "1_1") (pintype "unspecified"))
      (node (ref "U1") (pin "9") (pinfunction "4A_9") (pintype "unspecified"))
    )
    (net (code "257") (name "Net-(U1-4Y)") (class "Default")
      (node (ref "U1") (pin "8") (pinfunction "4Y_8") (pintype "unspecified"))
      (node (ref "U4") (pin "12") (pinfunction "B7_12") (pintype "unspecified"))
    )
    (net (code "258") (name "Net-(U1-5A)") (class "Default")
      (node (ref "U1") (pin "11") (pinfunction "5A_11") (pintype "unspecified"))
      (node (ref "U1") (pin "12") (pinfunction "6Y_12") (pintype "unspecified"))
    )
    (net (code "259") (name "Net-(U1-5Y)") (class "Default")
      (node (ref "U1") (pin "10") (pinfunction "5Y_10") (pintype "unspecified"))
      (node (ref "U4") (pin "11") (pinfunction "B8_11") (pintype "unspecified"))
    )
    (net (code "260") (name "Net-(U1-6A)") (class "Default")
      (node (ref "C3") (pin "1") (pinfunction "1_1") (pintype "unspecified"))
      (node (ref "R3") (pin "1") (pinfunction "1_1") (pintype "unspecified"))
      (node (ref "U1") (pin "13") (pinfunction "6A_13") (pintype "unspecified"))
    )
    (net (code "261") (name "Net-(U2-A8)") (class "Default")
      (node (ref "R7") (pin "2") (pinfunction "2_2") (pintype "unspecified"))
      (node (ref "U2") (pin "9") (pinfunction "A8_9") (pintype "unspecified"))
      (node (ref "U4") (pin "9") (pinfunction "A8_9") (pintype "unspecified"))
      (node (ref "U6") (pin "11") (pinfunction "B8_11") (pintype "unspecified"))
    )
    (net (code "262") (name "Net-(U6-A4)") (class "Default")
      (node (ref "RN5") (pin "13") (pinfunction "13_13") (pintype "bidirectional"))
      (node (ref "U6") (pin "5") (pinfunction "A4_5") (pintype "unspecified"))
    )
    (net (code "263") (name "Net-(U6-A5)") (class "Default")
      (node (ref "RN5") (pin "12") (pinfunction "12_12") (pintype "bidirectional"))
      (node (ref "U6") (pin "6") (pinfunction "A5_6") (pintype "unspecified"))
    )
    (net (code "264") (name "Net-(U6-A6)") (class "Default")
      (node (ref "RN5") (pin "11") (pinfunction "11_11") (pintype "bidirectional"))
      (node (ref "U6") (pin "7") (pinfunction "A6_7") (pintype "unspecified"))
    )
    (net (code "265") (name "Net-(U6-A7)") (class "Default")
      (node (ref "RN5") (pin "10") (pinfunction "10_10") (pintype "bidirectional"))
      (node (ref "U6") (pin "8") (pinfunction "A7_8") (pintype "unspecified"))
    )
    (net (code "266") (name "Net-(U6-A8)") (class "Default")
      (node (ref "RN5") (pin "9") (pinfunction "9_9") (pintype "bidirectional"))
      (node (ref "U6") (pin "9") (pinfunction "A8_9") (pintype "unspecified"))
    )
    (net (code "267") (name "Net-(U7-A1)") (class "Default")
      (node (ref "RN4") (pin "8") (pinfunction "8_8") (pintype "bidirectional"))
      (node (ref "U7") (pin "2") (pinfunction "A1_2") (pintype "unspecified"))
    )
    (net (code "268") (name "Net-(U7-A2)") (class "Default")
      (node (ref "RN4") (pin "7") (pinfunction "7_7") (pintype "bidirectional"))
      (node (ref "U7") (pin "3") (pinfunction "A2_3") (pintype "unspecified"))
    )
    (net (code "269") (name "Net-(U7-A3)") (class "Default")
      (node (ref "RN4") (pin "6") (pinfunction "6_6") (pintype "bidirectional"))
      (node (ref "U7") (pin "4") (pinfunction "A3_4") (pintype "unspecified"))
    )
    (net (code "270") (name "Net-(U7-A4)") (class "Default")
      (node (ref "RN4") (pin "5") (pinfunction "5_5") (pintype "bidirectional"))
      (node (ref "U7") (pin "5") (pinfunction "A4_5") (pintype "unspecified"))
    )
    (net (code "271") (name "Net-(U7-A5)") (class "Default")
      (node (ref "RN4") (pin "4") (pinfunction "4_4") (pintype "bidirectional"))
      (node (ref "U7") (pin "6") (pinfunction "A5_6") (pintype "unspecified"))
    )
    (net (code "272") (name "Net-(U7-A6)") (class "Default")
      (node (ref "RN4") (pin "3") (pinfunction "3_3") (pintype "bidirectional"))
      (node (ref "U7") (pin "7") (pinfunction "A6_7") (pintype "unspecified"))
    )
    (net (code "273") (name "Net-(U7-A7)") (class "Default")
      (node (ref "RN4") (pin "2") (pinfunction "2_2") (pintype "bidirectional"))
      (node (ref "U7") (pin "8") (pinfunction "A7_8") (pintype "unspecified"))
    )
    (net (code "274") (name "Net-(U7-A8)") (class "Default")
      (node (ref "RN4") (pin "1") (pinfunction "1_1") (pintype "bidirectional"))
      (node (ref "U7") (pin "9") (pinfunction "A8_9") (pintype "unspecified"))
    )
    (net (code "275") (name "Net-(U8-2Y)") (class "Default")
      (node (ref "U8") (pin "4") (pinfunction "2Y_4") (pintype "unspecified"))
      (node (ref "U9") (pin "4") (pinfunction "2A_4") (pintype "unspecified"))
    )
    (net (code "276") (name "Net-(U10-1CLR#)") (class "Default")
      (node (ref "U10") (pin "1") (pinfunction "1CLR#_1") (pintype "unspecified"))
      (node (ref "U9") (pin "6") (pinfunction "2Y_6") (pintype "unspecified"))
    )
    (net (code "277") (name "Net-(U10-1Q)") (class "Default")
      (node (ref "R34") (pin "1") (pinfunction "1_1") (pintype "unspecified"))
      (node (ref "R9") (pin "2") (pinfunction "2_2") (pintype "unspecified"))
      (node (ref "U10") (pin "5") (pinfunction "1Q_5") (pintype "unspecified"))
    )
    (net (code "278") (name "Net-(U10-2CLR#)") (class "Default")
      (node (ref "U10") (pin "13") (pinfunction "2CLR#_13") (pintype "unspecified"))
      (node (ref "U9") (pin "8") (pinfunction "3Y_8") (pintype "unspecified"))
    )
    (net (code "279") (name "Net-(U10-2PRE#)") (class "Default")
      (node (ref "U10") (pin "10") (pinfunction "2PRE#_10") (pintype "unspecified"))
      (node (ref "U8") (pin "6") (pinfunction "3Y_6") (pintype "unspecified"))
    )
    (net (code "280") (name "Net-(U10-2Q)") (class "Default")
      (node (ref "R33") (pin "2") (pinfunction "2_2") (pintype "unspecified"))
      (node (ref "R8") (pin "1") (pinfunction "1_1") (pintype "unspecified"))
      (node (ref "U10") (pin "9") (pinfunction "2Q_9") (pintype "unspecified"))
    )
    (net (code "281") (name "Net-(U14-A3)") (class "Default")
      (node (ref "RN7") (pin "6") (pinfunction "6_6") (pintype "bidirectional"))
      (node (ref "U14") (pin "4") (pinfunction "A3_4") (pintype "unspecified"))
    )
    (net (code "282") (name "Net-(U14-A4)") (class "Default")
      (node (ref "RN7") (pin "5") (pinfunction "5_5") (pintype "bidirectional"))
      (node (ref "U14") (pin "5") (pinfunction "A4_5") (pintype "unspecified"))
    )
    (net (code "283") (name "Net-(U14-A5)") (class "Default")
      (node (ref "RN7") (pin "4") (pinfunction "4_4") (pintype "bidirectional"))
      (node (ref "U14") (pin "6") (pinfunction "A5_6") (pintype "unspecified"))
    )
    (net (code "284") (name "Net-(U14-A6)") (class "Default")
      (node (ref "RN7") (pin "3") (pinfunction "3_3") (pintype "bidirectional"))
      (node (ref "U14") (pin "7") (pinfunction "A6_7") (pintype "unspecified"))
    )
    (net (code "285") (name "Net-(U14-A7)") (class "Default")
      (node (ref "RN7") (pin "2") (pinfunction "2_2") (pintype "bidirectional"))
      (node (ref "U14") (pin "8") (pinfunction "A7_8") (pintype "unspecified"))
    )
    (net (code "286") (name "Net-(U14-A8)") (class "Default")
      (node (ref "RN7") (pin "1") (pinfunction "1_1") (pintype "bidirectional"))
      (node (ref "U14") (pin "9") (pinfunction "A8_9") (pintype "unspecified"))
    )
    (net (code "287") (name "Net-(U15-1CLR#)") (class "Default")
      (node (ref "R13") (pin "1") (pinfunction "1_1") (pintype "unspecified"))
      (node (ref "U15") (pin "1") (pinfunction "1CLR#_1") (pintype "unspecified"))
    )
    (net (code "288") (name "Net-(U15-1D)") (class "Default")
      (node (ref "U15") (pin "2") (pinfunction "1D_2") (pintype "unspecified"))
      (node (ref "U15") (pin "8") (pinfunction "2Q#_8") (pintype "unspecified"))
    )
    (net (code "289") (name "Net-(U15-1Q#)") (class "Default")
      (node (ref "U15") (pin "6") (pinfunction "1Q#_6") (pintype "unspecified"))
      (node (ref "U16") (pin "9") (pinfunction "3A_9") (pintype "unspecified"))
    )
    (net (code "290") (name "Net-(U15-2PRE#)") (class "Default")
      (node (ref "R12") (pin "1") (pinfunction "1_1") (pintype "unspecified"))
      (node (ref "U15") (pin "10") (pinfunction "2PRE#_10") (pintype "unspecified"))
    )
    (net (code "291") (name "Net-(U15-2Q)") (class "Default")
      (node (ref "U15") (pin "9") (pinfunction "2Q_9") (pintype "unspecified"))
      (node (ref "U16") (pin "13") (pinfunction "4B_13") (pintype "unspecified"))
    )
    (net (code "292") (name "Net-(U16-1Y)") (class "Default")
      (node (ref "U16") (pin "3") (pinfunction "1Y_3") (pintype "unspecified"))
      (node (ref "U16") (pin "4") (pinfunction "2A_4") (pintype "unspecified"))
      (node (ref "U16") (pin "5") (pinfunction "2B_5") (pintype "unspecified"))
    )
    (net (code "293") (name "Net-(U16-2Y)") (class "Default")
      (node (ref "U16") (pin "6") (pinfunction "2Y_6") (pintype "unspecified"))
      (node (ref "U32") (pin "8") (pinfunction "1A4_8") (pintype "unspecified"))
    )
    (net (code "294") (name "Net-(U16-3Y)") (class "Default")
      (node (ref "U16") (pin "8") (pinfunction "3Y_8") (pintype "unspecified"))
      (node (ref "U32") (pin "4") (pinfunction "1A2_4") (pintype "unspecified"))
    )
    (net (code "295") (name "Net-(U16-4Y)") (class "Default")
      (node (ref "U16") (pin "11") (pinfunction "4Y_11") (pintype "unspecified"))
      (node (ref "U32") (pin "2") (pinfunction "1A1_2") (pintype "unspecified"))
    )
    (net (code "296") (name "Net-(U17-1PRE#)") (class "Default")
      (node (ref "R11") (pin "1") (pinfunction "1_1") (pintype "unspecified"))
      (node (ref "U17") (pin "4") (pinfunction "1PRE#_4") (pintype "unspecified"))
    )
    (net (code "297") (name "Net-(U17-2D)") (class "Default")
      (node (ref "U17") (pin "12") (pinfunction "2D_12") (pintype "unspecified"))
      (node (ref "U18") (pin "11") (pinfunction "4Y_11") (pintype "unspecified"))
    )
    (net (code "298") (name "Net-(U17-2PRE#)") (class "Default")
      (node (ref "R10") (pin "2") (pinfunction "2_2") (pintype "unspecified"))
      (node (ref "U17") (pin "10") (pinfunction "2PRE#_10") (pintype "unspecified"))
    )
    (net (code "299") (name "Net-(U17-2Q#)") (class "Default")
      (node (ref "U17") (pin "8") (pinfunction "2Q#_8") (pintype "unspecified"))
      (node (ref "U18") (pin "13") (pinfunction "4B_13") (pintype "unspecified"))
    )
    (net (code "300") (name "Net-(U17-2Q)") (class "Default")
      (node (ref "U17") (pin "9") (pinfunction "2Q_9") (pintype "unspecified"))
      (node (ref "U18") (pin "10") (pinfunction "3B_10") (pintype "unspecified"))
      (node (ref "U18") (pin "9") (pinfunction "3A_9") (pintype "unspecified"))
    )
    (net (code "301") (name "Net-(U18-1A)") (class "Default")
      (node (ref "U18") (pin "1") (pinfunction "1A_1") (pintype "unspecified"))
      (node (ref "U18") (pin "2") (pinfunction "1B_2") (pintype "unspecified"))
      (node (ref "U18") (pin "8") (pinfunction "3Y_8") (pintype "unspecified"))
    )
    (net (code "302") (name "Net-(U18-1Y)") (class "Default")
      (node (ref "U18") (pin "3") (pinfunction "1Y_3") (pintype "unspecified"))
      (node (ref "U18") (pin "4") (pinfunction "2A_4") (pintype "unspecified"))
      (node (ref "U18") (pin "5") (pinfunction "2B_5") (pintype "unspecified"))
    )
    (net (code "303") (name "Net-(U18-4A)") (class "Default")
      (node (ref "PLA") (pin "12") (pinfunction "I/O_12") (pintype "unspecified"))
      (node (ref "U18") (pin "12") (pinfunction "4A_12") (pintype "unspecified"))
    )
    (net (code "304") (name "Net-(U19-A1)") (class "Default")
      (node (ref "RN8") (pin "8") (pinfunction "8_8") (pintype "bidirectional"))
      (node (ref "U19") (pin "2") (pinfunction "A1_2") (pintype "unspecified"))
    )
    (net (code "305") (name "Net-(U19-A2)") (class "Default")
      (node (ref "RN8") (pin "7") (pinfunction "7_7") (pintype "bidirectional"))
      (node (ref "U19") (pin "3") (pinfunction "A2_3") (pintype "unspecified"))
    )
    (net (code "306") (name "Net-(U19-A3)") (class "Default")
      (node (ref "RN8") (pin "6") (pinfunction "6_6") (pintype "bidirectional"))
      (node (ref "U19") (pin "4") (pinfunction "A3_4") (pintype "unspecified"))
    )
    (net (code "307") (name "Net-(U19-A4)") (class "Default")
      (node (ref "RN8") (pin "5") (pinfunction "5_5") (pintype "bidirectional"))
      (node (ref "U19") (pin "5") (pinfunction "A4_5") (pintype "unspecified"))
    )
    (net (code "308") (name "Net-(U19-A5)") (class "Default")
      (node (ref "RN8") (pin "4") (pinfunction "4_4") (pintype "bidirectional"))
      (node (ref "U19") (pin "6") (pinfunction "A5_6") (pintype "unspecified"))
    )
    (net (code "309") (name "Net-(U19-A6)") (class "Default")
      (node (ref "RN8") (pin "3") (pinfunction "3_3") (pintype "bidirectional"))
      (node (ref "U19") (pin "7") (pinfunction "A6_7") (pintype "unspecified"))
    )
    (net (code "310") (name "Net-(U19-A7)") (class "Default")
      (node (ref "RN8") (pin "2") (pinfunction "2_2") (pintype "bidirectional"))
      (node (ref "U19") (pin "8") (pinfunction "A7_8") (pintype "unspecified"))
    )
    (net (code "311") (name "Net-(U19-A8)") (class "Default")
      (node (ref "RN8") (pin "1") (pinfunction "1_1") (pintype "bidirectional"))
      (node (ref "U19") (pin "9") (pinfunction "A8_9") (pintype "unspecified"))
    )
    (net (code "312") (name "Net-(U20-A1)") (class "Default")
      (node (ref "RN9") (pin "8") (pinfunction "8_8") (pintype "bidirectional"))
      (node (ref "U20") (pin "2") (pinfunction "A1_2") (pintype "unspecified"))
    )
    (net (code "313") (name "Net-(U20-A2)") (class "Default")
      (node (ref "RN9") (pin "7") (pinfunction "7_7") (pintype "bidirectional"))
      (node (ref "U20") (pin "3") (pinfunction "A2_3") (pintype "unspecified"))
    )
    (net (code "314") (name "Net-(U20-A3)") (class "Default")
      (node (ref "RN9") (pin "6") (pinfunction "6_6") (pintype "bidirectional"))
      (node (ref "U20") (pin "4") (pinfunction "A3_4") (pintype "unspecified"))
    )
    (net (code "315") (name "Net-(U20-A4)") (class "Default")
      (node (ref "RN9") (pin "5") (pinfunction "5_5") (pintype "bidirectional"))
      (node (ref "U20") (pin "5") (pinfunction "A4_5") (pintype "unspecified"))
    )
    (net (code "316") (name "Net-(U20-A5)") (class "Default")
      (node (ref "RN9") (pin "4") (pinfunction "4_4") (pintype "bidirectional"))
      (node (ref "U20") (pin "6") (pinfunction "A5_6") (pintype "unspecified"))
    )
    (net (code "317") (name "Net-(U20-A6)") (class "Default")
      (node (ref "RN9") (pin "3") (pinfunction "3_3") (pintype "bidirectional"))
      (node (ref "U20") (pin "7") (pinfunction "A6_7") (pintype "unspecified"))
    )
    (net (code "318") (name "Net-(U20-A7)") (class "Default")
      (node (ref "RN9") (pin "2") (pinfunction "2_2") (pintype "bidirectional"))
      (node (ref "U20") (pin "8") (pinfunction "A7_8") (pintype "unspecified"))
    )
    (net (code "319") (name "Net-(U20-A8)") (class "Default")
      (node (ref "RN9") (pin "1") (pinfunction "1_1") (pintype "bidirectional"))
      (node (ref "U20") (pin "9") (pinfunction "A8_9") (pintype "unspecified"))
    )
    (net (code "320") (name "Net-(U20-B1)") (class "Default")
      (node (ref "RN10") (pin "2") (pinfunction "2_2") (pintype "bidirectional"))
      (node (ref "RN24") (pin "8") (pinfunction "8_8") (pintype "bidirectional"))
      (node (ref "U20") (pin "18") (pinfunction "B1_18") (pintype "unspecified"))
      (node (ref "U21") (pin "2") (pinfunction "A1_2") (pintype "unspecified"))
    )
    (net (code "321") (name "Net-(U20-B2)") (class "Default")
      (node (ref "RN10") (pin "3") (pinfunction "3_3") (pintype "bidirectional"))
      (node (ref "RN24") (pin "7") (pinfunction "7_7") (pintype "bidirectional"))
      (node (ref "U20") (pin "17") (pinfunction "B2_17") (pintype "unspecified"))
      (node (ref "U21") (pin "3") (pinfunction "A2_3") (pintype "unspecified"))
    )
    (net (code "322") (name "Net-(U20-B3)") (class "Default")
      (node (ref "RN10") (pin "4") (pinfunction "4_4") (pintype "bidirectional"))
      (node (ref "RN24") (pin "6") (pinfunction "6_6") (pintype "bidirectional"))
      (node (ref "U20") (pin "16") (pinfunction "B3_16") (pintype "unspecified"))
      (node (ref "U21") (pin "4") (pinfunction "A3_4") (pintype "unspecified"))
    )
    (net (code "323") (name "Net-(U20-B4)") (class "Default")
      (node (ref "RN10") (pin "5") (pinfunction "5_5") (pintype "bidirectional"))
      (node (ref "RN24") (pin "5") (pinfunction "5_5") (pintype "bidirectional"))
      (node (ref "U20") (pin "15") (pinfunction "B4_15") (pintype "unspecified"))
      (node (ref "U21") (pin "5") (pinfunction "A4_5") (pintype "unspecified"))
    )
    (net (code "324") (name "Net-(U20-B5)") (class "Default")
      (node (ref "RN10") (pin "6") (pinfunction "6_6") (pintype "bidirectional"))
      (node (ref "RN24") (pin "4") (pinfunction "4_4") (pintype "bidirectional"))
      (node (ref "U20") (pin "14") (pinfunction "B5_14") (pintype "unspecified"))
      (node (ref "U21") (pin "6") (pinfunction "A5_6") (pintype "unspecified"))
    )
    (net (code "325") (name "Net-(U20-B6)") (class "Default")
      (node (ref "RN10") (pin "7") (pinfunction "7_7") (pintype "bidirectional"))
      (node (ref "RN24") (pin "3") (pinfunction "3_3") (pintype "bidirectional"))
      (node (ref "U20") (pin "13") (pinfunction "B6_13") (pintype "unspecified"))
      (node (ref "U21") (pin "7") (pinfunction "A6_7") (pintype "unspecified"))
    )
    (net (code "326") (name "Net-(U20-B7)") (class "Default")
      (node (ref "RN10") (pin "8") (pinfunction "8_8") (pintype "bidirectional"))
      (node (ref "RN24") (pin "2") (pinfunction "2_2") (pintype "bidirectional"))
      (node (ref "U20") (pin "12") (pinfunction "B7_12") (pintype "unspecified"))
      (node (ref "U21") (pin "8") (pinfunction "A7_8") (pintype "unspecified"))
    )
    (net (code "327") (name "Net-(U20-B8)") (class "Default")
      (node (ref "RN10") (pin "9") (pinfunction "9_9") (pintype "bidirectional"))
      (node (ref "RN24") (pin "1") (pinfunction "1_1") (pintype "bidirectional"))
      (node (ref "U20") (pin "11") (pinfunction "B8_11") (pintype "unspecified"))
      (node (ref "U21") (pin "9") (pinfunction "A8_9") (pintype "unspecified"))
    )
    (net (code "328") (name "Net-(U22-A1)") (class "Default")
      (node (ref "RN11") (pin "8") (pinfunction "8_8") (pintype "bidirectional"))
      (node (ref "U22") (pin "2") (pinfunction "A1_2") (pintype "unspecified"))
    )
    (net (code "329") (name "Net-(U22-A2)") (class "Default")
      (node (ref "RN11") (pin "7") (pinfunction "7_7") (pintype "bidirectional"))
      (node (ref "U22") (pin "3") (pinfunction "A2_3") (pintype "unspecified"))
    )
    (net (code "330") (name "Net-(U22-A3)") (class "Default")
      (node (ref "RN11") (pin "6") (pinfunction "6_6") (pintype "bidirectional"))
      (node (ref "U22") (pin "4") (pinfunction "A3_4") (pintype "unspecified"))
    )
    (net (code "331") (name "Net-(U22-A4)") (class "Default")
      (node (ref "RN11") (pin "5") (pinfunction "5_5") (pintype "bidirectional"))
      (node (ref "U22") (pin "5") (pinfunction "A4_5") (pintype "unspecified"))
    )
    (net (code "332") (name "Net-(U22-A5)") (class "Default")
      (node (ref "RN11") (pin "4") (pinfunction "4_4") (pintype "bidirectional"))
      (node (ref "U22") (pin "6") (pinfunction "A5_6") (pintype "unspecified"))
    )
    (net (code "333") (name "Net-(U22-A6)") (class "Default")
      (node (ref "RN11") (pin "3") (pinfunction "3_3") (pintype "bidirectional"))
      (node (ref "U22") (pin "7") (pinfunction "A6_7") (pintype "unspecified"))
    )
    (net (code "334") (name "Net-(U22-A7)") (class "Default")
      (node (ref "RN11") (pin "2") (pinfunction "2_2") (pintype "bidirectional"))
      (node (ref "U22") (pin "8") (pinfunction "A7_8") (pintype "unspecified"))
    )
    (net (code "335") (name "Net-(U22-A8)") (class "Default")
      (node (ref "RN11") (pin "1") (pinfunction "1_1") (pintype "bidirectional"))
      (node (ref "U22") (pin "9") (pinfunction "A8_9") (pintype "unspecified"))
    )
    (net (code "336") (name "Net-(U22-B1)") (class "Default")
      (node (ref "RN12") (pin "2") (pinfunction "2_2") (pintype "bidirectional"))
      (node (ref "RN23") (pin "8") (pinfunction "8_8") (pintype "bidirectional"))
      (node (ref "U22") (pin "18") (pinfunction "B1_18") (pintype "unspecified"))
      (node (ref "U23") (pin "2") (pinfunction "A1_2") (pintype "unspecified"))
    )
    (net (code "337") (name "Net-(U22-B2)") (class "Default")
      (node (ref "RN12") (pin "3") (pinfunction "3_3") (pintype "bidirectional"))
      (node (ref "RN23") (pin "7") (pinfunction "7_7") (pintype "bidirectional"))
      (node (ref "U22") (pin "17") (pinfunction "B2_17") (pintype "unspecified"))
      (node (ref "U23") (pin "3") (pinfunction "A2_3") (pintype "unspecified"))
    )
    (net (code "338") (name "Net-(U22-B3)") (class "Default")
      (node (ref "RN12") (pin "4") (pinfunction "4_4") (pintype "bidirectional"))
      (node (ref "RN23") (pin "6") (pinfunction "6_6") (pintype "bidirectional"))
      (node (ref "U22") (pin "16") (pinfunction "B3_16") (pintype "unspecified"))
      (node (ref "U23") (pin "4") (pinfunction "A3_4") (pintype "unspecified"))
    )
    (net (code "339") (name "Net-(U22-B4)") (class "Default")
      (node (ref "RN12") (pin "5") (pinfunction "5_5") (pintype "bidirectional"))
      (node (ref "RN23") (pin "5") (pinfunction "5_5") (pintype "bidirectional"))
      (node (ref "U22") (pin "15") (pinfunction "B4_15") (pintype "unspecified"))
      (node (ref "U23") (pin "5") (pinfunction "A4_5") (pintype "unspecified"))
    )
    (net (code "340") (name "Net-(U22-B5)") (class "Default")
      (node (ref "RN12") (pin "6") (pinfunction "6_6") (pintype "bidirectional"))
      (node (ref "RN23") (pin "4") (pinfunction "4_4") (pintype "bidirectional"))
      (node (ref "U22") (pin "14") (pinfunction "B5_14") (pintype "unspecified"))
      (node (ref "U23") (pin "6") (pinfunction "A5_6") (pintype "unspecified"))
    )
    (net (code "341") (name "Net-(U22-B6)") (class "Default")
      (node (ref "RN12") (pin "7") (pinfunction "7_7") (pintype "bidirectional"))
      (node (ref "RN23") (pin "3") (pinfunction "3_3") (pintype "bidirectional"))
      (node (ref "U22") (pin "13") (pinfunction "B6_13") (pintype "unspecified"))
      (node (ref "U23") (pin "7") (pinfunction "A6_7") (pintype "unspecified"))
    )
    (net (code "342") (name "Net-(U22-B7)") (class "Default")
      (node (ref "RN12") (pin "8") (pinfunction "8_8") (pintype "bidirectional"))
      (node (ref "RN23") (pin "2") (pinfunction "2_2") (pintype "bidirectional"))
      (node (ref "U22") (pin "12") (pinfunction "B7_12") (pintype "unspecified"))
      (node (ref "U23") (pin "8") (pinfunction "A7_8") (pintype "unspecified"))
    )
    (net (code "343") (name "Net-(U22-B8)") (class "Default")
      (node (ref "RN12") (pin "9") (pinfunction "9_9") (pintype "bidirectional"))
      (node (ref "RN23") (pin "1") (pinfunction "1_1") (pintype "bidirectional"))
      (node (ref "U22") (pin "11") (pinfunction "B8_11") (pintype "unspecified"))
      (node (ref "U23") (pin "9") (pinfunction "A8_9") (pintype "unspecified"))
    )
    (net (code "344") (name "Net-(U24-A1)") (class "Default")
      (node (ref "RN13") (pin "8") (pinfunction "8_8") (pintype "bidirectional"))
      (node (ref "U24") (pin "2") (pinfunction "A1_2") (pintype "unspecified"))
    )
    (net (code "345") (name "Net-(U24-A2)") (class "Default")
      (node (ref "RN13") (pin "7") (pinfunction "7_7") (pintype "bidirectional"))
      (node (ref "U24") (pin "3") (pinfunction "A2_3") (pintype "unspecified"))
    )
    (net (code "346") (name "Net-(U24-A3)") (class "Default")
      (node (ref "RN13") (pin "6") (pinfunction "6_6") (pintype "bidirectional"))
      (node (ref "U24") (pin "4") (pinfunction "A3_4") (pintype "unspecified"))
    )
    (net (code "347") (name "Net-(U24-A4)") (class "Default")
      (node (ref "RN13") (pin "5") (pinfunction "5_5") (pintype "bidirectional"))
      (node (ref "U24") (pin "5") (pinfunction "A4_5") (pintype "unspecified"))
    )
    (net (code "348") (name "Net-(U24-A5)") (class "Default")
      (node (ref "RN13") (pin "4") (pinfunction "4_4") (pintype "bidirectional"))
      (node (ref "U24") (pin "6") (pinfunction "A5_6") (pintype "unspecified"))
    )
    (net (code "349") (name "Net-(U24-A6)") (class "Default")
      (node (ref "RN13") (pin "3") (pinfunction "3_3") (pintype "bidirectional"))
      (node (ref "U24") (pin "7") (pinfunction "A6_7") (pintype "unspecified"))
    )
    (net (code "350") (name "Net-(U24-A7)") (class "Default")
      (node (ref "RN13") (pin "2") (pinfunction "2_2") (pintype "bidirectional"))
      (node (ref "U24") (pin "8") (pinfunction "A7_8") (pintype "unspecified"))
    )
    (net (code "351") (name "Net-(U24-A8)") (class "Default")
      (node (ref "RN13") (pin "1") (pinfunction "1_1") (pintype "bidirectional"))
      (node (ref "U24") (pin "9") (pinfunction "A8_9") (pintype "unspecified"))
    )
    (net (code "352") (name "Net-(U24-B1)") (class "Default")
      (node (ref "RN14") (pin "2") (pinfunction "2_2") (pintype "bidirectional"))
      (node (ref "RN22") (pin "8") (pinfunction "8_8") (pintype "bidirectional"))
      (node (ref "U24") (pin "18") (pinfunction "B1_18") (pintype "unspecified"))
      (node (ref "U25") (pin "2") (pinfunction "A1_2") (pintype "unspecified"))
    )
    (net (code "353") (name "Net-(U24-B2)") (class "Default")
      (node (ref "RN14") (pin "3") (pinfunction "3_3") (pintype "bidirectional"))
      (node (ref "RN22") (pin "7") (pinfunction "7_7") (pintype "bidirectional"))
      (node (ref "U24") (pin "17") (pinfunction "B2_17") (pintype "unspecified"))
      (node (ref "U25") (pin "3") (pinfunction "A2_3") (pintype "unspecified"))
    )
    (net (code "354") (name "Net-(U24-B3)") (class "Default")
      (node (ref "RN14") (pin "4") (pinfunction "4_4") (pintype "bidirectional"))
      (node (ref "RN22") (pin "6") (pinfunction "6_6") (pintype "bidirectional"))
      (node (ref "U24") (pin "16") (pinfunction "B3_16") (pintype "unspecified"))
      (node (ref "U25") (pin "4") (pinfunction "A3_4") (pintype "unspecified"))
    )
    (net (code "355") (name "Net-(U24-B4)") (class "Default")
      (node (ref "RN14") (pin "5") (pinfunction "5_5") (pintype "bidirectional"))
      (node (ref "RN22") (pin "5") (pinfunction "5_5") (pintype "bidirectional"))
      (node (ref "U24") (pin "15") (pinfunction "B4_15") (pintype "unspecified"))
      (node (ref "U25") (pin "5") (pinfunction "A4_5") (pintype "unspecified"))
    )
    (net (code "356") (name "Net-(U24-B5)") (class "Default")
      (node (ref "RN14") (pin "6") (pinfunction "6_6") (pintype "bidirectional"))
      (node (ref "RN22") (pin "4") (pinfunction "4_4") (pintype "bidirectional"))
      (node (ref "U24") (pin "14") (pinfunction "B5_14") (pintype "unspecified"))
      (node (ref "U25") (pin "6") (pinfunction "A5_6") (pintype "unspecified"))
    )
    (net (code "357") (name "Net-(U24-B6)") (class "Default")
      (node (ref "RN14") (pin "7") (pinfunction "7_7") (pintype "bidirectional"))
      (node (ref "RN22") (pin "3") (pinfunction "3_3") (pintype "bidirectional"))
      (node (ref "U24") (pin "13") (pinfunction "B6_13") (pintype "unspecified"))
      (node (ref "U25") (pin "7") (pinfunction "A6_7") (pintype "unspecified"))
    )
    (net (code "358") (name "Net-(U24-B7)") (class "Default")
      (node (ref "RN14") (pin "8") (pinfunction "8_8") (pintype "bidirectional"))
      (node (ref "RN22") (pin "2") (pinfunction "2_2") (pintype "bidirectional"))
      (node (ref "U24") (pin "12") (pinfunction "B7_12") (pintype "unspecified"))
      (node (ref "U25") (pin "8") (pinfunction "A7_8") (pintype "unspecified"))
    )
    (net (code "359") (name "Net-(U24-B8)") (class "Default")
      (node (ref "RN14") (pin "9") (pinfunction "9_9") (pintype "bidirectional"))
      (node (ref "RN22") (pin "1") (pinfunction "1_1") (pintype "bidirectional"))
      (node (ref "U24") (pin "11") (pinfunction "B8_11") (pintype "unspecified"))
      (node (ref "U25") (pin "9") (pinfunction "A8_9") (pintype "unspecified"))
    )
    (net (code "360") (name "Net-(U26-A1)") (class "Default")
      (node (ref "RN15") (pin "8") (pinfunction "8_8") (pintype "bidirectional"))
      (node (ref "U26") (pin "2") (pinfunction "A1_2") (pintype "unspecified"))
    )
    (net (code "361") (name "Net-(U26-A2)") (class "Default")
      (node (ref "RN15") (pin "7") (pinfunction "7_7") (pintype "bidirectional"))
      (node (ref "U26") (pin "3") (pinfunction "A2_3") (pintype "unspecified"))
    )
    (net (code "362") (name "Net-(U26-A3)") (class "Default")
      (node (ref "RN15") (pin "6") (pinfunction "6_6") (pintype "bidirectional"))
      (node (ref "U26") (pin "4") (pinfunction "A3_4") (pintype "unspecified"))
    )
    (net (code "363") (name "Net-(U26-A4)") (class "Default")
      (node (ref "RN15") (pin "5") (pinfunction "5_5") (pintype "bidirectional"))
      (node (ref "U26") (pin "5") (pinfunction "A4_5") (pintype "unspecified"))
    )
    (net (code "364") (name "Net-(U26-A5)") (class "Default")
      (node (ref "RN15") (pin "4") (pinfunction "4_4") (pintype "bidirectional"))
      (node (ref "U26") (pin "6") (pinfunction "A5_6") (pintype "unspecified"))
    )
    (net (code "365") (name "Net-(U26-A6)") (class "Default")
      (node (ref "RN15") (pin "3") (pinfunction "3_3") (pintype "bidirectional"))
      (node (ref "U26") (pin "7") (pinfunction "A6_7") (pintype "unspecified"))
    )
    (net (code "366") (name "Net-(U26-A7)") (class "Default")
      (node (ref "RN15") (pin "2") (pinfunction "2_2") (pintype "bidirectional"))
      (node (ref "U26") (pin "8") (pinfunction "A7_8") (pintype "unspecified"))
    )
    (net (code "367") (name "Net-(U26-A8)") (class "Default")
      (node (ref "RN15") (pin "1") (pinfunction "1_1") (pintype "bidirectional"))
      (node (ref "U26") (pin "9") (pinfunction "A8_9") (pintype "unspecified"))
    )
    (net (code "368") (name "Net-(U26-B1)") (class "Default")
      (node (ref "R32") (pin "1") (pinfunction "1_1") (pintype "unspecified"))
      (node (ref "RN16") (pin "2") (pinfunction "2_2") (pintype "bidirectional"))
      (node (ref "U26") (pin "18") (pinfunction "B1_18") (pintype "unspecified"))
      (node (ref "U27") (pin "2") (pinfunction "A1_2") (pintype "unspecified"))
    )
    (net (code "369") (name "Net-(U26-B8)") (class "Default")
      (node (ref "R31") (pin "1") (pinfunction "1_1") (pintype "unspecified"))
      (node (ref "RN16") (pin "9") (pinfunction "9_9") (pintype "bidirectional"))
      (node (ref "U26") (pin "11") (pinfunction "B8_11") (pintype "unspecified"))
      (node (ref "U27") (pin "9") (pinfunction "A8_9") (pintype "unspecified"))
    )
    (net (code "370") (name "Net-(U28-1Y)") (class "Default")
      (node (ref "R29") (pin "1") (pinfunction "1_1") (pintype "unspecified"))
      (node (ref "R36") (pin "2") (pinfunction "2_2") (pintype "unspecified"))
      (node (ref "U28") (pin "3") (pinfunction "1Y_3") (pintype "unspecified"))
    )
    (net (code "371") (name "Net-(U28-2Y)") (class "Default")
      (node (ref "R30") (pin "1") (pinfunction "1_1") (pintype "unspecified"))
      (node (ref "R37") (pin "1") (pinfunction "1_1") (pintype "unspecified"))
      (node (ref "U28") (pin "6") (pinfunction "2Y_6") (pintype "unspecified"))
    )
    (net (code "372") (name "Net-(U28-3Y)") (class "Default")
      (node (ref "U28") (pin "8") (pinfunction "3Y_8") (pintype "unspecified"))
      (node (ref "U30") (pin "19") (pinfunction "OE#_19") (pintype "unspecified"))
    )
    (net (code "373") (name "Net-(U28-4Y)") (class "Default")
      (node (ref "U28") (pin "11") (pinfunction "4Y_11") (pintype "unspecified"))
      (node (ref "U29") (pin "19") (pinfunction "OE#_19") (pintype "unspecified"))
    )
    (net (code "374") (name "Net-(U29-A1)") (class "Default")
      (node (ref "RN18") (pin "2") (pinfunction "2_2") (pintype "bidirectional"))
      (node (ref "RN20") (pin "8") (pinfunction "8_8") (pintype "bidirectional"))
      (node (ref "U29") (pin "2") (pinfunction "A1_2") (pintype "unspecified"))
    )
    (net (code "375") (name "Net-(U29-A2)") (class "Default")
      (node (ref "RN18") (pin "3") (pinfunction "3_3") (pintype "bidirectional"))
      (node (ref "RN20") (pin "7") (pinfunction "7_7") (pintype "bidirectional"))
      (node (ref "U29") (pin "3") (pinfunction "A2_3") (pintype "unspecified"))
    )
    (net (code "376") (name "Net-(U29-A3)") (class "Default")
      (node (ref "RN18") (pin "4") (pinfunction "4_4") (pintype "bidirectional"))
      (node (ref "RN20") (pin "6") (pinfunction "6_6") (pintype "bidirectional"))
      (node (ref "U29") (pin "4") (pinfunction "A3_4") (pintype "unspecified"))
    )
    (net (code "377") (name "Net-(U29-A4)") (class "Default")
      (node (ref "RN18") (pin "5") (pinfunction "5_5") (pintype "bidirectional"))
      (node (ref "RN20") (pin "5") (pinfunction "5_5") (pintype "bidirectional"))
      (node (ref "U29") (pin "5") (pinfunction "A4_5") (pintype "unspecified"))
    )
    (net (code "378") (name "Net-(U29-A5)") (class "Default")
      (node (ref "RN18") (pin "6") (pinfunction "6_6") (pintype "bidirectional"))
      (node (ref "RN20") (pin "4") (pinfunction "4_4") (pintype "bidirectional"))
      (node (ref "U29") (pin "6") (pinfunction "A5_6") (pintype "unspecified"))
    )
    (net (code "379") (name "Net-(U29-A6)") (class "Default")
      (node (ref "RN18") (pin "7") (pinfunction "7_7") (pintype "bidirectional"))
      (node (ref "RN20") (pin "3") (pinfunction "3_3") (pintype "bidirectional"))
      (node (ref "U29") (pin "7") (pinfunction "A6_7") (pintype "unspecified"))
    )
    (net (code "380") (name "Net-(U29-A7)") (class "Default")
      (node (ref "RN18") (pin "8") (pinfunction "8_8") (pintype "bidirectional"))
      (node (ref "RN20") (pin "2") (pinfunction "2_2") (pintype "bidirectional"))
      (node (ref "U29") (pin "8") (pinfunction "A7_8") (pintype "unspecified"))
    )
    (net (code "381") (name "Net-(U29-A8)") (class "Default")
      (node (ref "RN18") (pin "9") (pinfunction "9_9") (pintype "bidirectional"))
      (node (ref "RN20") (pin "1") (pinfunction "1_1") (pintype "bidirectional"))
      (node (ref "U29") (pin "9") (pinfunction "A8_9") (pintype "unspecified"))
    )
    (net (code "382") (name "Net-(U30-A1)") (class "Default")
      (node (ref "RN19") (pin "2") (pinfunction "2_2") (pintype "bidirectional"))
      (node (ref "RN21") (pin "8") (pinfunction "8_8") (pintype "bidirectional"))
      (node (ref "U30") (pin "2") (pinfunction "A1_2") (pintype "unspecified"))
    )
    (net (code "383") (name "Net-(U30-A2)") (class "Default")
      (node (ref "RN19") (pin "3") (pinfunction "3_3") (pintype "bidirectional"))
      (node (ref "RN21") (pin "7") (pinfunction "7_7") (pintype "bidirectional"))
      (node (ref "U30") (pin "3") (pinfunction "A2_3") (pintype "unspecified"))
    )
    (net (code "384") (name "Net-(U30-A3)") (class "Default")
      (node (ref "RN19") (pin "4") (pinfunction "4_4") (pintype "bidirectional"))
      (node (ref "RN21") (pin "6") (pinfunction "6_6") (pintype "bidirectional"))
      (node (ref "U30") (pin "4") (pinfunction "A3_4") (pintype "unspecified"))
    )
    (net (code "385") (name "Net-(U30-A4)") (class "Default")
      (node (ref "RN19") (pin "5") (pinfunction "5_5") (pintype "bidirectional"))
      (node (ref "RN21") (pin "5") (pinfunction "5_5") (pintype "bidirectional"))
      (node (ref "U30") (pin "5") (pinfunction "A4_5") (pintype "unspecified"))
    )
    (net (code "386") (name "Net-(U30-A5)") (class "Default")
      (node (ref "RN19") (pin "6") (pinfunction "6_6") (pintype "bidirectional"))
      (node (ref "RN21") (pin "4") (pinfunction "4_4") (pintype "bidirectional"))
      (node (ref "U30") (pin "6") (pinfunction "A5_6") (pintype "unspecified"))
    )
    (net (code "387") (name "Net-(U30-A6)") (class "Default")
      (node (ref "RN19") (pin "7") (pinfunction "7_7") (pintype "bidirectional"))
      (node (ref "RN21") (pin "3") (pinfunction "3_3") (pintype "bidirectional"))
      (node (ref "U30") (pin "7") (pinfunction "A6_7") (pintype "unspecified"))
    )
    (net (code "388") (name "Net-(U30-A7)") (class "Default")
      (node (ref "RN19") (pin "8") (pinfunction "8_8") (pintype "bidirectional"))
      (node (ref "RN21") (pin "2") (pinfunction "2_2") (pintype "bidirectional"))
      (node (ref "U30") (pin "8") (pinfunction "A7_8") (pintype "unspecified"))
    )
    (net (code "389") (name "Net-(U30-A8)") (class "Default")
      (node (ref "RN19") (pin "9") (pinfunction "9_9") (pintype "bidirectional"))
      (node (ref "RN21") (pin "1") (pinfunction "1_1") (pintype "bidirectional"))
      (node (ref "U30") (pin "9") (pinfunction "A8_9") (pintype "unspecified"))
    )
    (net (code "390") (name "Net-(U31-A1)") (class "Default")
      (node (ref "RN17") (pin "8") (pinfunction "8_8") (pintype "bidirectional"))
      (node (ref "U31") (pin "2") (pinfunction "A1_2") (pintype "unspecified"))
    )
    (net (code "391") (name "Net-(U31-A2)") (class "Default")
      (node (ref "RN17") (pin "7") (pinfunction "7_7") (pintype "bidirectional"))
      (node (ref "U31") (pin "3") (pinfunction "A2_3") (pintype "unspecified"))
    )
    (net (code "392") (name "Net-(U31-A3)") (class "Default")
      (node (ref "RN17") (pin "6") (pinfunction "6_6") (pintype "bidirectional"))
      (node (ref "U31") (pin "4") (pinfunction "A3_4") (pintype "unspecified"))
    )
    (net (code "393") (name "Net-(U31-A4)") (class "Default")
      (node (ref "RN17") (pin "5") (pinfunction "5_5") (pintype "bidirectional"))
      (node (ref "U31") (pin "5") (pinfunction "A4_5") (pintype "unspecified"))
    )
    (net (code "394") (name "Net-(U31-A5)") (class "Default")
      (node (ref "RN17") (pin "4") (pinfunction "4_4") (pintype "bidirectional"))
      (node (ref "U31") (pin "6") (pinfunction "A5_6") (pintype "unspecified"))
    )
    (net (code "395") (name "Net-(U31-A6)") (class "Default")
      (node (ref "RN17") (pin "3") (pinfunction "3_3") (pintype "bidirectional"))
      (node (ref "U31") (pin "7") (pinfunction "A6_7") (pintype "unspecified"))
    )
    (net (code "396") (name "Net-(U31-A7)") (class "Default")
      (node (ref "RN17") (pin "2") (pinfunction "2_2") (pintype "bidirectional"))
      (node (ref "U31") (pin "8") (pinfunction "A7_8") (pintype "unspecified"))
    )
    (net (code "397") (name "Net-(U31-A8)") (class "Default")
      (node (ref "RN17") (pin "1") (pinfunction "1_1") (pintype "bidirectional"))
      (node (ref "U31") (pin "9") (pinfunction "A8_9") (pintype "unspecified"))
    )
    (net (code "398") (name "Net-(U32-1Y1)") (class "Default")
      (node (ref "R15") (pin "2") (pinfunction "2_2") (pintype "unspecified"))
      (node (ref "U32") (pin "18") (pinfunction "1Y1_18") (pintype "unspecified"))
    )
    (net (code "399") (name "Net-(U32-1Y2)") (class "Default")
      (node (ref "R14") (pin "2") (pinfunction "2_2") (pintype "unspecified"))
      (node (ref "U32") (pin "16") (pinfunction "1Y2_16") (pintype "unspecified"))
    )
    (net (code "400") (name "Net-(U32-1Y4)") (class "Default")
      (node (ref "R35") (pin "1") (pinfunction "1_1") (pintype "unspecified"))
      (node (ref "R38") (pin "1") (pinfunction "1_1") (pintype "unspecified"))
      (node (ref "U32") (pin "12") (pinfunction "1Y4_12") (pintype "unspecified"))
    )
    (net (code "401") (name "Net-(U32-2OE#)") (class "Default")
      (node (ref "R16") (pin "2") (pinfunction "2_2") (pintype "unspecified"))
      (node (ref "U32") (pin "19") (pinfunction "2OE#_19") (pintype "unspecified"))
    )
    (net (code "402") (name "OMF") (class "Default")
      (node (ref "DM0") (pin "5") (pinfunction "A7_5") (pintype "unspecified"))
      (node (ref "DM1") (pin "5") (pinfunction "A7_5") (pintype "unspecified"))
      (node (ref "DM2") (pin "5") (pinfunction "A7_5") (pintype "unspecified"))
      (node (ref "DM3") (pin "5") (pinfunction "A7_5") (pintype "unspecified"))
      (node (ref "J2") (pin "C19") (pinfunction "C19_C19") (pintype "bidirectional"))
      (node (ref "R33") (pin "1") (pinfunction "1_1") (pintype "unspecified"))
    )
    (net (code "403") (name "OPIMM0") (class "Default")
      (node (ref "J2") (pin "C15") (pinfunction "C15_C15") (pintype "bidirectional"))
      (node (ref "U3") (pin "11") (pinfunction "B8_11") (pintype "unspecified"))
    )
    (net (code "404") (name "OPIMM1") (class "Default")
      (node (ref "J2") (pin "A15") (pinfunction "A15_A15") (pintype "bidirectional"))
      (node (ref "U3") (pin "12") (pinfunction "B7_12") (pintype "unspecified"))
    )
    (net (code "405") (name "OPIMM2") (class "Default")
      (node (ref "J2") (pin "C16") (pinfunction "C16_C16") (pintype "bidirectional"))
      (node (ref "U3") (pin "13") (pinfunction "B6_13") (pintype "unspecified"))
    )
    (net (code "406") (name "OPIMM3") (class "Default")
      (node (ref "J2") (pin "A16") (pinfunction "A16_A16") (pintype "bidirectional"))
      (node (ref "U3") (pin "14") (pinfunction "B5_14") (pintype "unspecified"))
    )
    (net (code "407") (name "OPIMM4") (class "Default")
      (node (ref "J2") (pin "C17") (pinfunction "C17_C17") (pintype "bidirectional"))
      (node (ref "U3") (pin "15") (pinfunction "B4_15") (pintype "unspecified"))
    )
    (net (code "408") (name "OPIMM5") (class "Default")
      (node (ref "J2") (pin "A17") (pinfunction "A17_A17") (pintype "bidirectional"))
      (node (ref "U3") (pin "16") (pinfunction "B3_16") (pintype "unspecified"))
    )
    (net (code "409") (name "OPIMM6") (class "Default")
      (node (ref "J2") (pin "C18") (pinfunction "C18_C18") (pintype "bidirectional"))
      (node (ref "U3") (pin "17") (pinfunction "B2_17") (pintype "unspecified"))
    )
    (net (code "410") (name "OPIMM7") (class "Default")
      (node (ref "J2") (pin "A18") (pinfunction "A18_A18") (pintype "bidirectional"))
      (node (ref "U3") (pin "18") (pinfunction "B1_18") (pintype "unspecified"))
    )
    (net (code "411") (name "PCLE") (class "Default")
      (node (ref "J2") (pin "C28") (pinfunction "C28_C28") (pintype "bidirectional"))
      (node (ref "RN22") (pin "13") (pinfunction "13_13") (pintype "bidirectional"))
    )
    (net (code "412") (name "PCOE") (class "Default")
      (node (ref "J2") (pin "C29") (pinfunction "C29_C29") (pintype "bidirectional"))
      (node (ref "R35") (pin "2") (pinfunction "2_2") (pintype "unspecified"))
    )
    (net (code "413") (name "RD") (class "Default")
      (node (ref "RN16") (pin "6") (pinfunction "6_6") (pintype "bidirectional"))
      (node (ref "U26") (pin "14") (pinfunction "B5_14") (pintype "unspecified"))
      (node (ref "U27") (pin "6") (pinfunction "A5_6") (pintype "unspecified"))
      (node (ref "U28") (pin "1") (pinfunction "1A_1") (pintype "unspecified"))
      (node (ref "U28") (pin "2") (pinfunction "1B_2") (pintype "unspecified"))
    )
    (net (code "414") (name "RHOE") (class "Default")
      (node (ref "J1") (pin "C13") (pinfunction "C13_C13") (pintype "bidirectional"))
      (node (ref "RN22") (pin "12") (pinfunction "12_12") (pintype "bidirectional"))
    )
    (net (code "415") (name "RLOE") (class "Default")
      (node (ref "J1") (pin "C14") (pinfunction "C14_C14") (pintype "bidirectional"))
      (node (ref "RN22") (pin "11") (pinfunction "11_11") (pintype "bidirectional"))
    )
    (net (code "416") (name "SFH") (class "Default")
      (node (ref "J1") (pin "A12") (pinfunction "A12_A12") (pintype "bidirectional"))
      (node (ref "U12") (pin "13") (pinfunction "B6_13") (pintype "unspecified"))
    )
    (net (code "417") (name "SFL") (class "Default")
      (node (ref "J1") (pin "C12") (pinfunction "C12_C12") (pintype "bidirectional"))
      (node (ref "U12") (pin "14") (pinfunction "B5_14") (pintype "unspecified"))
    )
    (net (code "418") (name "SFW") (class "Default")
      (node (ref "J1") (pin "A14") (pinfunction "A14_A14") (pintype "bidirectional"))
      (node (ref "RN22") (pin "10") (pinfunction "10_10") (pintype "bidirectional"))
    )
    (net (code "419") (name "SIMF") (class "Default")
      (node (ref "J2") (pin "A24") (pinfunction "A24_A24") (pintype "bidirectional"))
      (node (ref "U2") (pin "15") (pinfunction "B4_15") (pintype "unspecified"))
    )
    (net (code "420") (name "SNH") (class "Default")
      (node (ref "J1") (pin "A13") (pinfunction "A13_A13") (pintype "bidirectional"))
      (node (ref "RN22") (pin "9") (pinfunction "9_9") (pintype "bidirectional"))
    )
    (net (code "421") (name "SNL") (class "Default")
      (node (ref "J1") (pin "C15") (pinfunction "C15_C15") (pintype "bidirectional"))
      (node (ref "R31") (pin "2") (pinfunction "2_2") (pintype "unspecified"))
    )
    (net (code "422") (name "SOMF") (class "Default")
      (node (ref "RN16") (pin "3") (pinfunction "3_3") (pintype "bidirectional"))
      (node (ref "U26") (pin "17") (pinfunction "B2_17") (pintype "unspecified"))
      (node (ref "U27") (pin "3") (pinfunction "A2_3") (pintype "unspecified"))
      (node (ref "U8") (pin "5") (pinfunction "3A_5") (pintype "unspecified"))
    )
    (net (code "423") (name "SWOE") (class "Default")
      (node (ref "U1") (pin "6") (pinfunction "3Y_6") (pintype "unspecified"))
      (node (ref "U13") (pin "19") (pinfunction "OE#_19") (pintype "unspecified"))
      (node (ref "U4") (pin "19") (pinfunction "OE#_19") (pintype "unspecified"))
      (node (ref "U5") (pin "19") (pinfunction "OE#_19") (pintype "unspecified"))
    )
    (net (code "424") (name "SYSCLK") (class "Default")
      (node (ref "J2") (pin "C22") (pinfunction "C22_C22") (pintype "bidirectional"))
      (node (ref "U2") (pin "11") (pinfunction "B8_11") (pintype "unspecified"))
    )
    (net (code "425") (name "VCC") (class "Default")
      (node (ref "C10") (pin "1") (pinfunction "1_1") (pintype "input"))
      (node (ref "C11") (pin "1") (pinfunction "1_1") (pintype "input"))
      (node (ref "C12") (pin "1") (pinfunction "1_1") (pintype "input"))
      (node (ref "C13") (pin "1") (pinfunction "1_1") (pintype "input"))
      (node (ref "C14") (pin "1") (pinfunction "1_1") (pintype "input"))
      (node (ref "C15") (pin "1") (pinfunction "1_1") (pintype "unspecified"))
      (node (ref "C16") (pin "1") (pinfunction "1_1") (pintype "unspecified"))
      (node (ref "C17") (pin "1") (pinfunction "1_1") (pintype "unspecified"))
      (node (ref "C18") (pin "1") (pinfunction "1_1") (pintype "unspecified"))
      (node (ref "C19") (pin "1") (pinfunction "1_1") (pintype "unspecified"))
      (node (ref "C2") (pin "1") (pinfunction "+_1") (pintype "bidirectional"))
      (node (ref "C20") (pin "1") (pinfunction "1_1") (pintype "unspecified"))
      (node (ref "C21") (pin "1") (pinfunction "1_1") (pintype "unspecified"))
      (node (ref "C22") (pin "1") (pinfunction "1_1") (pintype "unspecified"))
      (node (ref "C23") (pin "1") (pinfunction "1_1") (pintype "unspecified"))
      (node (ref "C24") (pin "1") (pinfunction "1_1") (pintype "unspecified"))
      (node (ref "C25") (pin "1") (pinfunction "1_1") (pintype "unspecified"))
      (node (ref "C26") (pin "1") (pinfunction "1_1") (pintype "unspecified"))
      (node (ref "C27") (pin "1") (pinfunction "1_1") (pintype "unspecified"))
      (node (ref "C28") (pin "1") (pinfunction "1_1") (pintype "unspecified"))
      (node (ref "C29") (pin "1") (pinfunction "1_1") (pintype "unspecified"))
      (node (ref "C30") (pin "1") (pinfunction "1_1") (pintype "unspecified"))
      (node (ref "C31") (pin "1") (pinfunction "1_1") (pintype "unspecified"))
      (node (ref "C32") (pin "1") (pinfunction "1_1") (pintype "unspecified"))
      (node (ref "C33") (pin "1") (pinfunction "1_1") (pintype "unspecified"))
      (node (ref "C34") (pin "1") (pinfunction "1_1") (pintype "unspecified"))
      (node (ref "C35") (pin "1") (pinfunction "1_1") (pintype "unspecified"))
      (node (ref "C36") (pin "1") (pinfunction "1_1") (pintype "unspecified"))
      (node (ref "C37") (pin "1") (pinfunction "1_1") (pintype "unspecified"))
      (node (ref "C38") (pin "1") (pinfunction "1_1") (pintype "unspecified"))
      (node (ref "C39") (pin "1") (pinfunction "1_1") (pintype "unspecified"))
      (node (ref "C40") (pin "1") (pinfunction "1_1") (pintype "unspecified"))
      (node (ref "C41") (pin "1") (pinfunction "1_1") (pintype "unspecified"))
      (node (ref "C42") (pin "1") (pinfunction "1_1") (pintype "unspecified"))
      (node (ref "C43") (pin "1") (pinfunction "1_1") (pintype "unspecified"))
      (node (ref "C44") (pin "1") (pinfunction "1_1") (pintype "unspecified"))
      (node (ref "C45") (pin "1") (pinfunction "1_1") (pintype "unspecified"))
      (node (ref "C46") (pin "1") (pinfunction "1_1") (pintype "unspecified"))
      (node (ref "C47") (pin "1") (pinfunction "1_1") (pintype "unspecified"))
      (node (ref "C48") (pin "1") (pinfunction "1_1") (pintype "unspecified"))
      (node (ref "C49") (pin "1") (pinfunction "1_1") (pintype "unspecified"))
      (node (ref "C5") (pin "1") (pinfunction "1_1") (pintype "input"))
      (node (ref "C50") (pin "1") (pinfunction "1_1") (pintype "unspecified"))
      (node (ref "C51") (pin "1") (pinfunction "1_1") (pintype "unspecified"))
      (node (ref "C52") (pin "1") (pinfunction "1_1") (pintype "unspecified"))
      (node (ref "C53") (pin "1") (pinfunction "1_1") (pintype "unspecified"))
      (node (ref "C54") (pin "1") (pinfunction "1_1") (pintype "unspecified"))
      (node (ref "C55") (pin "1") (pinfunction "1_1") (pintype "unspecified"))
      (node (ref "C56") (pin "1") (pinfunction "1_1") (pintype "unspecified"))
      (node (ref "C57") (pin "1") (pinfunction "1_1") (pintype "unspecified"))
      (node (ref "C6") (pin "1") (pinfunction "1_1") (pintype "input"))
      (node (ref "C7") (pin "1") (pinfunction "1_1") (pintype "input"))
      (node (ref "C8") (pin "1") (pinfunction "1_1") (pintype "input"))
      (node (ref "C9") (pin "1") (pinfunction "1_1") (pintype "input"))
      (node (ref "D3") (pin "1") (pinfunction "K_1") (pintype "unspecified"))
      (node (ref "DIR0") (pin "20") (pinfunction "VCC_20") (pintype "unspecified"))
      (node (ref "DIR1") (pin "20") (pinfunction "VCC_20") (pintype "unspecified"))
      (node (ref "DIR2") (pin "20") (pinfunction "VCC_20") (pintype "unspecified"))
      (node (ref "DIR3") (pin "20") (pinfunction "VCC_20") (pintype "unspecified"))
      (node (ref "DM0") (pin "32") (pinfunction "VDD_32") (pintype "unspecified"))
      (node (ref "DM1") (pin "32") (pinfunction "VDD_32") (pintype "unspecified"))
      (node (ref "DM2") (pin "32") (pinfunction "VDD_32") (pintype "unspecified"))
      (node (ref "DM3") (pin "32") (pinfunction "VDD_32") (pintype "unspecified"))
      (node (ref "IMM") (pin "20") (pinfunction "VCC_20") (pintype "unspecified"))
      (node (ref "IR") (pin "20") (pinfunction "VCC_20") (pintype "unspecified"))
      (node (ref "PLA") (pin "20") (pinfunction "VCC_20") (pintype "unspecified"))
      (node (ref "R1") (pin "2") (pinfunction "2_2") (pintype "unspecified"))
      (node (ref "R10") (pin "1") (pinfunction "1_1") (pintype "unspecified"))
      (node (ref "R11") (pin "2") (pinfunction "2_2") (pintype "unspecified"))
      (node (ref "R12") (pin "2") (pinfunction "2_2") (pintype "unspecified"))
      (node (ref "R13") (pin "2") (pinfunction "2_2") (pintype "unspecified"))
      (node (ref "R16") (pin "1") (pinfunction "1_1") (pintype "unspecified"))
      (node (ref "R17") (pin "1") (pinfunction "1_1") (pintype "unspecified"))
      (node (ref "R18") (pin "2") (pinfunction "2_2") (pintype "unspecified"))
      (node (ref "R19") (pin "1") (pinfunction "1_1") (pintype "unspecified"))
      (node (ref "R2") (pin "2") (pinfunction "2_2") (pintype "unspecified"))
      (node (ref "R20") (pin "1") (pinfunction "1_1") (pintype "unspecified"))
      (node (ref "R21") (pin "2") (pinfunction "2_2") (pintype "unspecified"))
      (node (ref "R22") (pin "1") (pinfunction "1_1") (pintype "unspecified"))
      (node (ref "R23") (pin "1") (pinfunction "1_1") (pintype "unspecified"))
      (node (ref "R24") (pin "2") (pinfunction "2_2") (pintype "unspecified"))
      (node (ref "R25") (pin "1") (pinfunction "1_1") (pintype "unspecified"))
      (node (ref "R26") (pin "1") (pinfunction "1_1") (pintype "unspecified"))
      (node (ref "R27") (pin "2") (pinfunction "2_2") (pintype "unspecified"))
      (node (ref "R28") (pin "1") (pinfunction "1_1") (pintype "unspecified"))
      (node (ref "R29") (pin "2") (pinfunction "2_2") (pintype "unspecified"))
      (node (ref "R30") (pin "2") (pinfunction "2_2") (pintype "unspecified"))
      (node (ref "R38") (pin "2") (pinfunction "2_2") (pintype "unspecified"))
      (node (ref "R39") (pin "1") (pinfunction "1_1") (pintype "unspecified"))
      (node (ref "R4") (pin "2") (pinfunction "2_2") (pintype "unspecified"))
      (node (ref "R40") (pin "1") (pinfunction "1_1") (pintype "unspecified"))
      (node (ref "R41") (pin "1") (pinfunction "1_1") (pintype "unspecified"))
      (node (ref "R42") (pin "1") (pinfunction "1_1") (pintype "unspecified"))
      (node (ref "R6") (pin "1") (pinfunction "1_1") (pintype "unspecified"))
      (node (ref "R8") (pin "2") (pinfunction "2_2") (pintype "unspecified"))
      (node (ref "R9") (pin "1") (pinfunction "1_1") (pintype "unspecified"))
      (node (ref "REG") (pin "3") (pinfunction "VOUT+_3") (pintype "bidirectional"))
      (node (ref "RN18") (pin "1") (pinfunction "1_1") (pintype "bidirectional"))
      (node (ref "RN19") (pin "1") (pinfunction "1_1") (pintype "bidirectional"))
      (node (ref "S1") (pin "1") (pinfunction "1_1_COM_1") (pintype "bidirectional"))
      (node (ref "S1") (pin "2") (pinfunction "2_1_COM_2") (pintype "bidirectional"))
      (node (ref "S1") (pin "3") (pinfunction "3_1_COM_3") (pintype "bidirectional"))
      (node (ref "S1") (pin "4") (pinfunction "4_1_COM_4") (pintype "bidirectional"))
      (node (ref "S1") (pin "5") (pinfunction "5_1_COM_5") (pintype "bidirectional"))
      (node (ref "S1") (pin "6") (pinfunction "6_1_COM_6") (pintype "bidirectional"))
      (node (ref "S1") (pin "7") (pinfunction "7_1_COM_7") (pintype "bidirectional"))
      (node (ref "S1") (pin "8") (pinfunction "8_1_COM_8") (pintype "bidirectional"))
      (node (ref "S2") (pin "1") (pinfunction "1_1_COM_1") (pintype "bidirectional"))
      (node (ref "S2") (pin "2") (pinfunction "2_1_COM_2") (pintype "bidirectional"))
      (node (ref "S2") (pin "3") (pinfunction "3_1_COM_3") (pintype "bidirectional"))
      (node (ref "S2") (pin "4") (pinfunction "4_1_COM_4") (pintype "bidirectional"))
      (node (ref "S2") (pin "5") (pinfunction "5_1_COM_5") (pintype "bidirectional"))
      (node (ref "S2") (pin "6") (pinfunction "6_1_COM_6") (pintype "bidirectional"))
      (node (ref "S2") (pin "7") (pinfunction "7_1_COM_7") (pintype "bidirectional"))
      (node (ref "S2") (pin "8") (pinfunction "8_1_COM_8") (pintype "bidirectional"))
      (node (ref "S3") (pin "1") (pinfunction "1_1_COM_1") (pintype "bidirectional"))
      (node (ref "S3") (pin "2") (pinfunction "2_1_COM_2") (pintype "bidirectional"))
      (node (ref "S3") (pin "3") (pinfunction "3_1_COM_3") (pintype "bidirectional"))
      (node (ref "S3") (pin "4") (pinfunction "4_1_COM_4") (pintype "bidirectional"))
      (node (ref "S3") (pin "5") (pinfunction "5_1_COM_5") (pintype "bidirectional"))
      (node (ref "S3") (pin "6") (pinfunction "6_1_COM_6") (pintype "bidirectional"))
      (node (ref "S3") (pin "7") (pinfunction "7_1_COM_7") (pintype "bidirectional"))
      (node (ref "S3") (pin "8") (pinfunction "8_1_COM_8") (pintype "bidirectional"))
      (node (ref "U1") (pin "14") (pinfunction "VCC_14") (pintype "unspecified"))
      (node (ref "U10") (pin "14") (pinfunction "VCC_14") (pintype "unspecified"))
      (node (ref "U11") (pin "20") (pinfunction "VCC_20") (pintype "unspecified"))
      (node (ref "U12") (pin "20") (pinfunction "VCC_20") (pintype "unspecified"))
      (node (ref "U13") (pin "20") (pinfunction "VCC_20") (pintype "unspecified"))
      (node (ref "U14") (pin "20") (pinfunction "VCC_20") (pintype "unspecified"))
      (node (ref "U15") (pin "14") (pinfunction "VCC_14") (pintype "unspecified"))
      (node (ref "U16") (pin "14") (pinfunction "VCC_14") (pintype "unspecified"))
      (node (ref "U17") (pin "14") (pinfunction "VCC_14") (pintype "unspecified"))
      (node (ref "U18") (pin "14") (pinfunction "VCC_14") (pintype "unspecified"))
      (node (ref "U19") (pin "20") (pinfunction "VCC_20") (pintype "unspecified"))
      (node (ref "U2") (pin "20") (pinfunction "VCC_20") (pintype "unspecified"))
      (node (ref "U20") (pin "20") (pinfunction "VCC_20") (pintype "unspecified"))
      (node (ref "U21") (pin "20") (pinfunction "VCC_20") (pintype "unspecified"))
      (node (ref "U22") (pin "20") (pinfunction "VCC_20") (pintype "unspecified"))
      (node (ref "U23") (pin "20") (pinfunction "VCC_20") (pintype "unspecified"))
      (node (ref "U24") (pin "20") (pinfunction "VCC_20") (pintype "unspecified"))
      (node (ref "U25") (pin "20") (pinfunction "VCC_20") (pintype "unspecified"))
      (node (ref "U26") (pin "20") (pinfunction "VCC_20") (pintype "unspecified"))
      (node (ref "U27") (pin "20") (pinfunction "VCC_20") (pintype "unspecified"))
      (node (ref "U28") (pin "14") (pinfunction "VCC_14") (pintype "unspecified"))
      (node (ref "U29") (pin "20") (pinfunction "VCC_20") (pintype "unspecified"))
      (node (ref "U3") (pin "20") (pinfunction "VCC_20") (pintype "unspecified"))
      (node (ref "U30") (pin "20") (pinfunction "VCC_20") (pintype "unspecified"))
      (node (ref "U31") (pin "20") (pinfunction "VCC_20") (pintype "unspecified"))
      (node (ref "U32") (pin "20") (pinfunction "VCC_20") (pintype "unspecified"))
      (node (ref "U4") (pin "20") (pinfunction "VCC_20") (pintype "unspecified"))
      (node (ref "U5") (pin "20") (pinfunction "VCC_20") (pintype "unspecified"))
      (node (ref "U6") (pin "20") (pinfunction "VCC_20") (pintype "unspecified"))
      (node (ref "U7") (pin "20") (pinfunction "VCC_20") (pintype "unspecified"))
      (node (ref "U8") (pin "14") (pinfunction "VCC_14") (pintype "unspecified"))
      (node (ref "U9") (pin "14") (pinfunction "VCC_14") (pintype "unspecified"))
    )
    (net (code "426") (name "WR") (class "Default")
      (node (ref "RN16") (pin "5") (pinfunction "5_5") (pintype "bidirectional"))
      (node (ref "U26") (pin "15") (pinfunction "B4_15") (pintype "unspecified"))
      (node (ref "U27") (pin "5") (pinfunction "A4_5") (pintype "unspecified"))
      (node (ref "U28") (pin "5") (pinfunction "2B_5") (pintype "unspecified"))
    )
    (net (code "427") (name "ZFH") (class "Default")
      (node (ref "J1") (pin "A10") (pinfunction "A10_A10") (pintype "bidirectional"))
      (node (ref "U12") (pin "15") (pinfunction "B4_15") (pintype "unspecified"))
    )
    (net (code "428") (name "ZFL") (class "Default")
      (node (ref "J1") (pin "C10") (pinfunction "C10_C10") (pintype "bidirectional"))
      (node (ref "U12") (pin "16") (pinfunction "B3_16") (pintype "unspecified"))
    )
    (net (code "429") (name "lCFH") (class "Default")
      (node (ref "DM0") (pin "7") (pinfunction "A5_7") (pintype "unspecified"))
      (node (ref "DM1") (pin "7") (pinfunction "A5_7") (pintype "unspecified"))
      (node (ref "DM2") (pin "7") (pinfunction "A5_7") (pintype "unspecified"))
      (node (ref "DM3") (pin "7") (pinfunction "A5_7") (pintype "unspecified"))
      (node (ref "U12") (pin "9") (pinfunction "A8_9") (pintype "unspecified"))
      (node (ref "U13") (pin "9") (pinfunction "A8_9") (pintype "unspecified"))
      (node (ref "U14") (pin "11") (pinfunction "B8_11") (pintype "unspecified"))
    )
    (net (code "430") (name "lCFL") (class "Default")
      (node (ref "DM0") (pin "8") (pinfunction "A4_8") (pintype "unspecified"))
      (node (ref "DM1") (pin "8") (pinfunction "A4_8") (pintype "unspecified"))
      (node (ref "DM2") (pin "8") (pinfunction "A4_8") (pintype "unspecified"))
      (node (ref "DM3") (pin "8") (pinfunction "A4_8") (pintype "unspecified"))
      (node (ref "U12") (pin "8") (pinfunction "A7_8") (pintype "unspecified"))
      (node (ref "U13") (pin "8") (pinfunction "A7_8") (pintype "unspecified"))
      (node (ref "U14") (pin "12") (pinfunction "B7_12") (pintype "unspecified"))
    )
    (net (code "431") (name "lCOMF") (class "Default")
      (node (ref "U2") (pin "6") (pinfunction "A5_6") (pintype "unspecified"))
      (node (ref "U4") (pin "6") (pinfunction "A5_6") (pintype "unspecified"))
      (node (ref "U6") (pin "14") (pinfunction "B5_14") (pintype "unspecified"))
      (node (ref "U9") (pin "9") (pinfunction "3A_9") (pintype "unspecified"))
    )
    (net (code "432") (name "lOPIMM0") (class "Default")
      (node (ref "IMM") (pin "3") (pinfunction "1D_3") (pintype "unspecified"))
      (node (ref "PLA") (pin "9") (pinfunction "I8_9") (pintype "unspecified"))
      (node (ref "U11") (pin "18") (pinfunction "B1_18") (pintype "unspecified"))
      (node (ref "U3") (pin "9") (pinfunction "A8_9") (pintype "unspecified"))
      (node (ref "U5") (pin "2") (pinfunction "A1_2") (pintype "unspecified"))
      (node (ref "U7") (pin "18") (pinfunction "B1_18") (pintype "unspecified"))
    )
    (net (code "433") (name "lOPIMM1") (class "Default")
      (node (ref "IMM") (pin "4") (pinfunction "2D_4") (pintype "unspecified"))
      (node (ref "PLA") (pin "8") (pinfunction "I7_8") (pintype "unspecified"))
      (node (ref "U11") (pin "17") (pinfunction "B2_17") (pintype "unspecified"))
      (node (ref "U3") (pin "8") (pinfunction "A7_8") (pintype "unspecified"))
      (node (ref "U5") (pin "3") (pinfunction "A2_3") (pintype "unspecified"))
      (node (ref "U7") (pin "17") (pinfunction "B2_17") (pintype "unspecified"))
    )
    (net (code "434") (name "lOPIMM2") (class "Default")
      (node (ref "IMM") (pin "7") (pinfunction "3D_7") (pintype "unspecified"))
      (node (ref "PLA") (pin "7") (pinfunction "I6_7") (pintype "unspecified"))
      (node (ref "U11") (pin "16") (pinfunction "B3_16") (pintype "unspecified"))
      (node (ref "U3") (pin "7") (pinfunction "A6_7") (pintype "unspecified"))
      (node (ref "U5") (pin "4") (pinfunction "A3_4") (pintype "unspecified"))
      (node (ref "U7") (pin "16") (pinfunction "B3_16") (pintype "unspecified"))
    )
    (net (code "435") (name "lOPIMM3") (class "Default")
      (node (ref "IMM") (pin "8") (pinfunction "4D_8") (pintype "unspecified"))
      (node (ref "PLA") (pin "6") (pinfunction "I5_6") (pintype "unspecified"))
      (node (ref "U11") (pin "15") (pinfunction "B4_15") (pintype "unspecified"))
      (node (ref "U3") (pin "6") (pinfunction "A5_6") (pintype "unspecified"))
      (node (ref "U5") (pin "5") (pinfunction "A4_5") (pintype "unspecified"))
      (node (ref "U7") (pin "15") (pinfunction "B4_15") (pintype "unspecified"))
    )
    (net (code "436") (name "lOPIMM4") (class "Default")
      (node (ref "IMM") (pin "13") (pinfunction "5D_13") (pintype "unspecified"))
      (node (ref "PLA") (pin "5") (pinfunction "I4_5") (pintype "unspecified"))
      (node (ref "U11") (pin "14") (pinfunction "B5_14") (pintype "unspecified"))
      (node (ref "U3") (pin "5") (pinfunction "A4_5") (pintype "unspecified"))
      (node (ref "U5") (pin "6") (pinfunction "A5_6") (pintype "unspecified"))
      (node (ref "U7") (pin "14") (pinfunction "B5_14") (pintype "unspecified"))
    )
    (net (code "437") (name "lOPIMM5") (class "Default")
      (node (ref "IMM") (pin "14") (pinfunction "6D_14") (pintype "unspecified"))
      (node (ref "PLA") (pin "4") (pinfunction "I3_4") (pintype "unspecified"))
      (node (ref "U11") (pin "13") (pinfunction "B6_13") (pintype "unspecified"))
      (node (ref "U3") (pin "4") (pinfunction "A3_4") (pintype "unspecified"))
      (node (ref "U5") (pin "7") (pinfunction "A6_7") (pintype "unspecified"))
      (node (ref "U7") (pin "13") (pinfunction "B6_13") (pintype "unspecified"))
    )
    (net (code "438") (name "lOPIMM6") (class "Default")
      (node (ref "IMM") (pin "17") (pinfunction "7D_17") (pintype "unspecified"))
      (node (ref "PLA") (pin "3") (pinfunction "I2_3") (pintype "unspecified"))
      (node (ref "U11") (pin "12") (pinfunction "B7_12") (pintype "unspecified"))
      (node (ref "U3") (pin "3") (pinfunction "A2_3") (pintype "unspecified"))
      (node (ref "U5") (pin "8") (pinfunction "A7_8") (pintype "unspecified"))
      (node (ref "U7") (pin "12") (pinfunction "B7_12") (pintype "unspecified"))
    )
    (net (code "439") (name "lOPIMM7") (class "Default")
      (node (ref "IMM") (pin "18") (pinfunction "8D_18") (pintype "unspecified"))
      (node (ref "PLA") (pin "2") (pinfunction "I1_2") (pintype "unspecified"))
      (node (ref "U11") (pin "11") (pinfunction "B8_11") (pintype "unspecified"))
      (node (ref "U3") (pin "2") (pinfunction "A1_2") (pintype "unspecified"))
      (node (ref "U5") (pin "9") (pinfunction "A8_9") (pintype "unspecified"))
      (node (ref "U7") (pin "11") (pinfunction "B8_11") (pintype "unspecified"))
    )
    (net (code "440") (name "lSFH") (class "Default")
      (node (ref "DM0") (pin "9") (pinfunction "A3_9") (pintype "unspecified"))
      (node (ref "DM1") (pin "9") (pinfunction "A3_9") (pintype "unspecified"))
      (node (ref "DM2") (pin "9") (pinfunction "A3_9") (pintype "unspecified"))
      (node (ref "DM3") (pin "9") (pinfunction "A3_9") (pintype "unspecified"))
      (node (ref "U12") (pin "7") (pinfunction "A6_7") (pintype "unspecified"))
      (node (ref "U13") (pin "7") (pinfunction "A6_7") (pintype "unspecified"))
      (node (ref "U14") (pin "13") (pinfunction "B6_13") (pintype "unspecified"))
    )
    (net (code "441") (name "lSFL") (class "Default")
      (node (ref "DM0") (pin "10") (pinfunction "A2_10") (pintype "unspecified"))
      (node (ref "DM1") (pin "10") (pinfunction "A2_10") (pintype "unspecified"))
      (node (ref "DM2") (pin "10") (pinfunction "A2_10") (pintype "unspecified"))
      (node (ref "DM3") (pin "10") (pinfunction "A2_10") (pintype "unspecified"))
      (node (ref "U12") (pin "6") (pinfunction "A5_6") (pintype "unspecified"))
      (node (ref "U13") (pin "6") (pinfunction "A5_6") (pintype "unspecified"))
      (node (ref "U14") (pin "14") (pinfunction "B5_14") (pintype "unspecified"))
    )
    (net (code "442") (name "lSIMF") (class "Default")
      (node (ref "U10") (pin "4") (pinfunction "1PRE#_4") (pintype "unspecified"))
      (node (ref "U2") (pin "5") (pinfunction "A4_5") (pintype "unspecified"))
      (node (ref "U4") (pin "5") (pinfunction "A4_5") (pintype "unspecified"))
      (node (ref "U6") (pin "15") (pinfunction "B4_15") (pintype "unspecified"))
    )
    (net (code "443") (name "lSYSCLK") (class "Default")
      (node (ref "R7") (pin "1") (pinfunction "1_1") (pintype "unspecified"))
      (node (ref "U15") (pin "11") (pinfunction "2CLK_11") (pintype "unspecified"))
      (node (ref "U16") (pin "10") (pinfunction "3B_10") (pintype "unspecified"))
      (node (ref "U8") (pin "9") (pinfunction "4A_9") (pintype "unspecified"))
    )
    (net (code "444") (name "lZFH") (class "Default")
      (node (ref "DM0") (pin "11") (pinfunction "A1_11") (pintype "unspecified"))
      (node (ref "DM1") (pin "11") (pinfunction "A1_11") (pintype "unspecified"))
      (node (ref "DM2") (pin "11") (pinfunction "A1_11") (pintype "unspecified"))
      (node (ref "DM3") (pin "11") (pinfunction "A1_11") (pintype "unspecified"))
      (node (ref "U12") (pin "5") (pinfunction "A4_5") (pintype "unspecified"))
      (node (ref "U13") (pin "5") (pinfunction "A4_5") (pintype "unspecified"))
      (node (ref "U14") (pin "15") (pinfunction "B4_15") (pintype "unspecified"))
    )
    (net (code "445") (name "lZFL") (class "Default")
      (node (ref "DM0") (pin "12") (pinfunction "A0_12") (pintype "unspecified"))
      (node (ref "DM1") (pin "12") (pinfunction "A0_12") (pintype "unspecified"))
      (node (ref "DM2") (pin "12") (pinfunction "A0_12") (pintype "unspecified"))
      (node (ref "DM3") (pin "12") (pinfunction "A0_12") (pintype "unspecified"))
      (node (ref "U12") (pin "4") (pinfunction "A3_4") (pintype "unspecified"))
      (node (ref "U13") (pin "4") (pinfunction "A3_4") (pintype "unspecified"))
      (node (ref "U14") (pin "16") (pinfunction "B3_16") (pintype "unspecified"))
    )
    (net (code "446") (name "lnHLT") (class "Default")
      (node (ref "U15") (pin "12") (pinfunction "2D_12") (pintype "unspecified"))
      (node (ref "U2") (pin "7") (pinfunction "A6_7") (pintype "unspecified"))
      (node (ref "U4") (pin "7") (pinfunction "A6_7") (pintype "unspecified"))
      (node (ref "U6") (pin "13") (pinfunction "B6_13") (pintype "unspecified"))
    )
    (net (code "447") (name "lnRST") (class "Default")
      (node (ref "DIR0") (pin "1") (pinfunction "CLR#_1") (pintype "unspecified"))
      (node (ref "DIR1") (pin "1") (pinfunction "CLR#_1") (pintype "unspecified"))
      (node (ref "DIR2") (pin "1") (pinfunction "CLR#_1") (pintype "unspecified"))
      (node (ref "DIR3") (pin "1") (pinfunction "CLR#_1") (pintype "unspecified"))
      (node (ref "IMM") (pin "1") (pinfunction "CLR#_1") (pintype "unspecified"))
      (node (ref "IR") (pin "1") (pinfunction "CLR#_1") (pintype "unspecified"))
      (node (ref "U15") (pin "13") (pinfunction "2CLR#_13") (pintype "unspecified"))
      (node (ref "U15") (pin "4") (pinfunction "1PRE#_4") (pintype "unspecified"))
      (node (ref "U16") (pin "1") (pinfunction "1A_1") (pintype "unspecified"))
      (node (ref "U16") (pin "2") (pinfunction "1B_2") (pintype "unspecified"))
      (node (ref "U17") (pin "13") (pinfunction "2CLR#_13") (pintype "unspecified"))
      (node (ref "U2") (pin "8") (pinfunction "A7_8") (pintype "unspecified"))
      (node (ref "U4") (pin "8") (pinfunction "A7_8") (pintype "unspecified"))
      (node (ref "U6") (pin "12") (pinfunction "B7_12") (pintype "unspecified"))
      (node (ref "U9") (pin "10") (pinfunction "3B_10") (pintype "unspecified"))
      (node (ref "U9") (pin "5") (pinfunction "2B_5") (pintype "unspecified"))
    )
    (net (code "448") (name "lnSYSCLK") (class "Default")
      (node (ref "U15") (pin "3") (pinfunction "1CLK_3") (pintype "unspecified"))
      (node (ref "U16") (pin "12") (pinfunction "4A_12") (pintype "unspecified"))
      (node (ref "U8") (pin "8") (pinfunction "4Y_8") (pintype "unspecified"))
    )
    (net (code "449") (name "nCLK") (class "Default")
      (node (ref "DIR0") (pin "11") (pinfunction "CLK_11") (pintype "unspecified"))
      (node (ref "DIR1") (pin "11") (pinfunction "CLK_11") (pintype "unspecified"))
      (node (ref "DIR2") (pin "11") (pinfunction "CLK_11") (pintype "unspecified"))
      (node (ref "DIR3") (pin "11") (pinfunction "CLK_11") (pintype "unspecified"))
      (node (ref "IMM") (pin "11") (pinfunction "CLK_11") (pintype "unspecified"))
      (node (ref "IR") (pin "11") (pinfunction "CLK_11") (pintype "unspecified"))
      (node (ref "R15") (pin "1") (pinfunction "1_1") (pintype "unspecified"))
      (node (ref "U17") (pin "11") (pinfunction "2CLK_11") (pintype "unspecified"))
    )
    (net (code "450") (name "nDIROE") (class "Default")
      (node (ref "U15") (pin "5") (pinfunction "1Q_5") (pintype "unspecified"))
      (node (ref "U21") (pin "19") (pinfunction "OE#_19") (pintype "unspecified"))
      (node (ref "U23") (pin "19") (pinfunction "OE#_19") (pintype "unspecified"))
      (node (ref "U25") (pin "19") (pinfunction "OE#_19") (pintype "unspecified"))
      (node (ref "U27") (pin "19") (pinfunction "OE#_19") (pintype "unspecified"))
    )
    (net (code "451") (name "nHLT") (class "Default")
      (node (ref "J2") (pin "C26") (pinfunction "C26_C26") (pintype "bidirectional"))
      (node (ref "U2") (pin "13") (pinfunction "B6_13") (pintype "unspecified"))
    )
    (net (code "452") (name "nNOPOE") (class "Default")
      (node (ref "U11") (pin "19") (pinfunction "OE#_19") (pintype "unspecified"))
      (node (ref "U18") (pin "6") (pinfunction "2Y_6") (pintype "unspecified"))
    )
    (net (code "453") (name "nRD") (class "Default")
      (node (ref "J2") (pin "C27") (pinfunction "C27_C27") (pintype "bidirectional"))
      (node (ref "R36") (pin "1") (pinfunction "1_1") (pintype "unspecified"))
    )
    (net (code "454") (name "nRST") (class "Default")
      (node (ref "J2") (pin "A30") (pinfunction "A30_A30") (pintype "bidirectional"))
      (node (ref "U2") (pin "12") (pinfunction "B7_12") (pintype "unspecified"))
    )
    (net (code "455") (name "nWR") (class "Default")
      (node (ref "J2") (pin "A25") (pinfunction "A25_A25") (pintype "bidirectional"))
      (node (ref "R37") (pin "2") (pinfunction "2_2") (pintype "unspecified"))
    )
    (net (code "456") (name "unconnected-(J1-PadA15)") (class "Default")
      (node (ref "J1") (pin "A15") (pinfunction "A15_A15") (pintype "bidirectional+no_connect"))
    )
    (net (code "457") (name "unconnected-(J1-PadA16)") (class "Default")
      (node (ref "J1") (pin "A16") (pinfunction "A16_A16") (pintype "bidirectional+no_connect"))
    )
    (net (code "458") (name "unconnected-(J1-PadA17)") (class "Default")
      (node (ref "J1") (pin "A17") (pinfunction "A17_A17") (pintype "bidirectional+no_connect"))
    )
    (net (code "459") (name "unconnected-(J1-PadA18)") (class "Default")
      (node (ref "J1") (pin "A18") (pinfunction "A18_A18") (pintype "bidirectional+no_connect"))
    )
    (net (code "460") (name "unconnected-(J1-PadA19)") (class "Default")
      (node (ref "J1") (pin "A19") (pinfunction "A19_A19") (pintype "bidirectional+no_connect"))
    )
    (net (code "461") (name "unconnected-(J1-PadA20)") (class "Default")
      (node (ref "J1") (pin "A20") (pinfunction "A20_A20") (pintype "bidirectional+no_connect"))
    )
    (net (code "462") (name "unconnected-(J1-PadA21)") (class "Default")
      (node (ref "J1") (pin "A21") (pinfunction "A21_A21") (pintype "bidirectional+no_connect"))
    )
    (net (code "463") (name "unconnected-(J1-PadA22)") (class "Default")
      (node (ref "J1") (pin "A22") (pinfunction "A22_A22") (pintype "bidirectional+no_connect"))
    )
    (net (code "464") (name "unconnected-(J1-PadA23)") (class "Default")
      (node (ref "J1") (pin "A23") (pinfunction "A23_A23") (pintype "bidirectional+no_connect"))
    )
    (net (code "465") (name "unconnected-(J1-PadA24)") (class "Default")
      (node (ref "J1") (pin "A24") (pinfunction "A24_A24") (pintype "bidirectional+no_connect"))
    )
    (net (code "466") (name "unconnected-(J1-PadA25)") (class "Default")
      (node (ref "J1") (pin "A25") (pinfunction "A25_A25") (pintype "bidirectional+no_connect"))
    )
    (net (code "467") (name "unconnected-(J1-PadA26)") (class "Default")
      (node (ref "J1") (pin "A26") (pinfunction "A26_A26") (pintype "bidirectional+no_connect"))
    )
    (net (code "468") (name "unconnected-(J1-PadA27)") (class "Default")
      (node (ref "J1") (pin "A27") (pinfunction "A27_A27") (pintype "bidirectional+no_connect"))
    )
    (net (code "469") (name "unconnected-(J1-PadA28)") (class "Default")
      (node (ref "J1") (pin "A28") (pinfunction "A28_A28") (pintype "bidirectional+no_connect"))
    )
    (net (code "470") (name "unconnected-(J1-PadA29)") (class "Default")
      (node (ref "J1") (pin "A29") (pinfunction "A29_A29") (pintype "bidirectional+no_connect"))
    )
    (net (code "471") (name "unconnected-(J1-PadA30)") (class "Default")
      (node (ref "J1") (pin "A30") (pinfunction "A30_A30") (pintype "bidirectional+no_connect"))
    )
    (net (code "472") (name "unconnected-(J1-PadC16)") (class "Default")
      (node (ref "J1") (pin "C16") (pinfunction "C16_C16") (pintype "bidirectional+no_connect"))
    )
    (net (code "473") (name "unconnected-(J1-PadC17)") (class "Default")
      (node (ref "J1") (pin "C17") (pinfunction "C17_C17") (pintype "bidirectional+no_connect"))
    )
    (net (code "474") (name "unconnected-(J1-PadC18)") (class "Default")
      (node (ref "J1") (pin "C18") (pinfunction "C18_C18") (pintype "bidirectional+no_connect"))
    )
    (net (code "475") (name "unconnected-(J1-PadC19)") (class "Default")
      (node (ref "J1") (pin "C19") (pinfunction "C19_C19") (pintype "bidirectional+no_connect"))
    )
    (net (code "476") (name "unconnected-(J1-PadC20)") (class "Default")
      (node (ref "J1") (pin "C20") (pinfunction "C20_C20") (pintype "bidirectional+no_connect"))
    )
    (net (code "477") (name "unconnected-(J1-PadC21)") (class "Default")
      (node (ref "J1") (pin "C21") (pinfunction "C21_C21") (pintype "bidirectional+no_connect"))
    )
    (net (code "478") (name "unconnected-(J1-PadC22)") (class "Default")
      (node (ref "J1") (pin "C22") (pinfunction "C22_C22") (pintype "bidirectional+no_connect"))
    )
    (net (code "479") (name "unconnected-(J1-PadC23)") (class "Default")
      (node (ref "J1") (pin "C23") (pinfunction "C23_C23") (pintype "bidirectional+no_connect"))
    )
    (net (code "480") (name "unconnected-(J1-PadC24)") (class "Default")
      (node (ref "J1") (pin "C24") (pinfunction "C24_C24") (pintype "bidirectional+no_connect"))
    )
    (net (code "481") (name "unconnected-(J1-PadC25)") (class "Default")
      (node (ref "J1") (pin "C25") (pinfunction "C25_C25") (pintype "bidirectional+no_connect"))
    )
    (net (code "482") (name "unconnected-(J1-PadC26)") (class "Default")
      (node (ref "J1") (pin "C26") (pinfunction "C26_C26") (pintype "bidirectional+no_connect"))
    )
    (net (code "483") (name "unconnected-(J1-PadC27)") (class "Default")
      (node (ref "J1") (pin "C27") (pinfunction "C27_C27") (pintype "bidirectional+no_connect"))
    )
    (net (code "484") (name "unconnected-(J1-PadC28)") (class "Default")
      (node (ref "J1") (pin "C28") (pinfunction "C28_C28") (pintype "bidirectional+no_connect"))
    )
    (net (code "485") (name "unconnected-(J1-PadC29)") (class "Default")
      (node (ref "J1") (pin "C29") (pinfunction "C29_C29") (pintype "bidirectional+no_connect"))
    )
    (net (code "486") (name "unconnected-(J1-PadC30)") (class "Default")
      (node (ref "J1") (pin "C30") (pinfunction "C30_C30") (pintype "bidirectional+no_connect"))
    )
    (net (code "487") (name "unconnected-(J1-PadC31)") (class "Default")
      (node (ref "J1") (pin "C31") (pinfunction "C31_C31") (pintype "bidirectional+no_connect"))
    )
    (net (code "488") (name "unconnected-(J2-PadA11)") (class "Default")
      (node (ref "J2") (pin "A11") (pinfunction "A11_A11") (pintype "bidirectional+no_connect"))
    )
    (net (code "489") (name "unconnected-(J2-PadA12)") (class "Default")
      (node (ref "J2") (pin "A12") (pinfunction "A12_A12") (pintype "bidirectional+no_connect"))
    )
    (net (code "490") (name "unconnected-(J2-PadA13)") (class "Default")
      (node (ref "J2") (pin "A13") (pinfunction "A13_A13") (pintype "bidirectional+no_connect"))
    )
    (net (code "491") (name "unconnected-(J2-PadA14)") (class "Default")
      (node (ref "J2") (pin "A14") (pinfunction "A14_A14") (pintype "bidirectional+no_connect"))
    )
    (net (code "492") (name "unconnected-(J2-PadC11)") (class "Default")
      (node (ref "J2") (pin "C11") (pinfunction "C11_C11") (pintype "bidirectional+no_connect"))
    )
    (net (code "493") (name "unconnected-(J2-PadC12)") (class "Default")
      (node (ref "J2") (pin "C12") (pinfunction "C12_C12") (pintype "bidirectional+no_connect"))
    )
    (net (code "494") (name "unconnected-(J2-PadC13)") (class "Default")
      (node (ref "J2") (pin "C13") (pinfunction "C13_C13") (pintype "bidirectional+no_connect"))
    )
    (net (code "495") (name "unconnected-(J2-PadC14)") (class "Default")
      (node (ref "J2") (pin "C14") (pinfunction "C14_C14") (pintype "bidirectional+no_connect"))
    )
    (net (code "496") (name "unconnected-(PLA-I{slash}O-Pad13)") (class "Default")
      (node (ref "PLA") (pin "13") (pinfunction "I/O_13") (pintype "unspecified+no_connect"))
    )
    (net (code "497") (name "unconnected-(PLA-I{slash}O-Pad14)") (class "Default")
      (node (ref "PLA") (pin "14") (pinfunction "I/O_14") (pintype "unspecified+no_connect"))
    )
    (net (code "498") (name "unconnected-(PLA-I{slash}O-Pad15)") (class "Default")
      (node (ref "PLA") (pin "15") (pinfunction "I/O_15") (pintype "unspecified+no_connect"))
    )
    (net (code "499") (name "unconnected-(PLA-I{slash}O-Pad16)") (class "Default")
      (node (ref "PLA") (pin "16") (pinfunction "I/O_16") (pintype "unspecified+no_connect"))
    )
    (net (code "500") (name "unconnected-(PLA-I{slash}O-Pad17)") (class "Default")
      (node (ref "PLA") (pin "17") (pinfunction "I/O_17") (pintype "unspecified+no_connect"))
    )
    (net (code "501") (name "unconnected-(PLA-I{slash}O-Pad18)") (class "Default")
      (node (ref "PLA") (pin "18") (pinfunction "I/O_18") (pintype "unspecified+no_connect"))
    )
    (net (code "502") (name "unconnected-(PLA-I{slash}O-Pad19)") (class "Default")
      (node (ref "PLA") (pin "19") (pinfunction "I/O_19") (pintype "unspecified+no_connect"))
    )
    (net (code "503") (name "unconnected-(RN3-Pad5)") (class "Default")
      (node (ref "RN3") (pin "5") (pinfunction "5_5") (pintype "bidirectional+no_connect"))
    )
    (net (code "504") (name "unconnected-(RN3-Pad6)") (class "Default")
      (node (ref "RN3") (pin "6") (pinfunction "6_6") (pintype "bidirectional+no_connect"))
    )
    (net (code "505") (name "unconnected-(RN3-Pad7)") (class "Default")
      (node (ref "RN3") (pin "7") (pinfunction "7_7") (pintype "bidirectional+no_connect"))
    )
    (net (code "506") (name "unconnected-(RN3-Pad8)") (class "Default")
      (node (ref "RN3") (pin "8") (pinfunction "8_8") (pintype "bidirectional+no_connect"))
    )
    (net (code "507") (name "unconnected-(RN3-Pad9)") (class "Default")
      (node (ref "RN3") (pin "9") (pinfunction "9_9") (pintype "bidirectional+no_connect"))
    )
    (net (code "508") (name "unconnected-(RN5-Pad1)") (class "Default")
      (node (ref "RN5") (pin "1") (pinfunction "1_1") (pintype "bidirectional+no_connect"))
    )
    (net (code "509") (name "unconnected-(RN5-Pad2)") (class "Default")
      (node (ref "RN5") (pin "2") (pinfunction "2_2") (pintype "bidirectional+no_connect"))
    )
    (net (code "510") (name "unconnected-(RN5-Pad3)") (class "Default")
      (node (ref "RN5") (pin "3") (pinfunction "3_3") (pintype "bidirectional+no_connect"))
    )
    (net (code "511") (name "unconnected-(RN6-Pad8)") (class "Default")
      (node (ref "RN6") (pin "8") (pinfunction "8_8") (pintype "bidirectional+no_connect"))
    )
    (net (code "512") (name "unconnected-(RN6-Pad9)") (class "Default")
      (node (ref "RN6") (pin "9") (pinfunction "9_9") (pintype "bidirectional+no_connect"))
    )
    (net (code "513") (name "unconnected-(RN7-Pad9)") (class "Default")
      (node (ref "RN7") (pin "9") (pinfunction "9_9") (pintype "bidirectional+no_connect"))
    )
    (net (code "514") (name "unconnected-(RN7-Pad10)") (class "Default")
      (node (ref "RN7") (pin "10") (pinfunction "10_10") (pintype "bidirectional+no_connect"))
    )
    (net (code "515") (name "unconnected-(S1-4_2_NO-Pad12)") (class "Default")
      (node (ref "S1") (pin "12") (pinfunction "4_2_NO_12") (pintype "bidirectional+no_connect"))
    )
    (net (code "516") (name "unconnected-(S1-5_2_NO-Pad13)") (class "Default")
      (node (ref "S1") (pin "13") (pinfunction "5_2_NO_13") (pintype "bidirectional+no_connect"))
    )
    (net (code "517") (name "unconnected-(S1-6_2_NO-Pad14)") (class "Default")
      (node (ref "S1") (pin "14") (pinfunction "6_2_NO_14") (pintype "bidirectional+no_connect"))
    )
    (net (code "518") (name "unconnected-(S1-7_2_NO-Pad15)") (class "Default")
      (node (ref "S1") (pin "15") (pinfunction "7_2_NO_15") (pintype "bidirectional+no_connect"))
    )
    (net (code "519") (name "unconnected-(S1-8_2_NO-Pad16)") (class "Default")
      (node (ref "S1") (pin "16") (pinfunction "8_2_NO_16") (pintype "bidirectional+no_connect"))
    )
    (net (code "520") (name "unconnected-(S3-7_2_NO-Pad15)") (class "Default")
      (node (ref "S3") (pin "15") (pinfunction "7_2_NO_15") (pintype "bidirectional+no_connect"))
    )
    (net (code "521") (name "unconnected-(S3-8_2_NO-Pad16)") (class "Default")
      (node (ref "S3") (pin "16") (pinfunction "8_2_NO_16") (pintype "bidirectional+no_connect"))
    )
    (net (code "522") (name "unconnected-(U2-A1-Pad2)") (class "Default")
      (node (ref "U2") (pin "2") (pinfunction "A1_2") (pintype "unspecified+no_connect"))
    )
    (net (code "523") (name "unconnected-(U2-A2-Pad3)") (class "Default")
      (node (ref "U2") (pin "3") (pinfunction "A2_3") (pintype "unspecified+no_connect"))
    )
    (net (code "524") (name "unconnected-(U2-A3-Pad4)") (class "Default")
      (node (ref "U2") (pin "4") (pinfunction "A3_4") (pintype "unspecified+no_connect"))
    )
    (net (code "525") (name "unconnected-(U4-A1-Pad2)") (class "Default")
      (node (ref "U4") (pin "2") (pinfunction "A1_2") (pintype "unspecified+no_connect"))
    )
    (net (code "526") (name "unconnected-(U4-A2-Pad3)") (class "Default")
      (node (ref "U4") (pin "3") (pinfunction "A2_3") (pintype "unspecified+no_connect"))
    )
    (net (code "527") (name "unconnected-(U4-A3-Pad4)") (class "Default")
      (node (ref "U4") (pin "4") (pinfunction "A3_4") (pintype "unspecified+no_connect"))
    )
    (net (code "528") (name "unconnected-(U6-A1-Pad2)") (class "Default")
      (node (ref "U6") (pin "2") (pinfunction "A1_2") (pintype "unspecified+no_connect"))
    )
    (net (code "529") (name "unconnected-(U6-A2-Pad3)") (class "Default")
      (node (ref "U6") (pin "3") (pinfunction "A2_3") (pintype "unspecified+no_connect"))
    )
    (net (code "530") (name "unconnected-(U6-A3-Pad4)") (class "Default")
      (node (ref "U6") (pin "4") (pinfunction "A3_4") (pintype "unspecified+no_connect"))
    )
    (net (code "531") (name "unconnected-(U8-1Y-Pad2)") (class "Default")
      (node (ref "U8") (pin "2") (pinfunction "1Y_2") (pintype "unspecified+no_connect"))
    )
    (net (code "532") (name "unconnected-(U8-5Y-Pad10)") (class "Default")
      (node (ref "U8") (pin "10") (pinfunction "5Y_10") (pintype "unspecified+no_connect"))
    )
    (net (code "533") (name "unconnected-(U8-6Y-Pad12)") (class "Default")
      (node (ref "U8") (pin "12") (pinfunction "6Y_12") (pintype "unspecified+no_connect"))
    )
    (net (code "534") (name "unconnected-(U9-1Y-Pad3)") (class "Default")
      (node (ref "U9") (pin "3") (pinfunction "1Y_3") (pintype "unspecified+no_connect"))
    )
    (net (code "535") (name "unconnected-(U9-4Y-Pad11)") (class "Default")
      (node (ref "U9") (pin "11") (pinfunction "4Y_11") (pintype "unspecified+no_connect"))
    )
    (net (code "536") (name "unconnected-(U10-1Q#-Pad6)") (class "Default")
      (node (ref "U10") (pin "6") (pinfunction "1Q#_6") (pintype "unspecified+no_connect"))
    )
    (net (code "537") (name "unconnected-(U10-2Q#-Pad8)") (class "Default")
      (node (ref "U10") (pin "8") (pinfunction "2Q#_8") (pintype "unspecified+no_connect"))
    )
    (net (code "538") (name "unconnected-(U12-A1-Pad2)") (class "Default")
      (node (ref "U12") (pin "2") (pinfunction "A1_2") (pintype "unspecified+no_connect"))
    )
    (net (code "539") (name "unconnected-(U12-A2-Pad3)") (class "Default")
      (node (ref "U12") (pin "3") (pinfunction "A2_3") (pintype "unspecified+no_connect"))
    )
    (net (code "540") (name "unconnected-(U13-A1-Pad2)") (class "Default")
      (node (ref "U13") (pin "2") (pinfunction "A1_2") (pintype "unspecified+no_connect"))
    )
    (net (code "541") (name "unconnected-(U13-A2-Pad3)") (class "Default")
      (node (ref "U13") (pin "3") (pinfunction "A2_3") (pintype "unspecified+no_connect"))
    )
    (net (code "542") (name "unconnected-(U14-A1-Pad2)") (class "Default")
      (node (ref "U14") (pin "2") (pinfunction "A1_2") (pintype "unspecified+no_connect"))
    )
    (net (code "543") (name "unconnected-(U14-A2-Pad3)") (class "Default")
      (node (ref "U14") (pin "3") (pinfunction "A2_3") (pintype "unspecified+no_connect"))
    )
    (net (code "544") (name "unconnected-(U17-1Q#-Pad6)") (class "Default")
      (node (ref "U17") (pin "6") (pinfunction "1Q#_6") (pintype "unspecified+no_connect"))
    )
    (net (code "545") (name "unconnected-(U17-1Q-Pad5)") (class "Default")
      (node (ref "U17") (pin "5") (pinfunction "1Q_5") (pintype "unspecified+no_connect"))
    )
    (net (code "546") (name "unconnected-(U32-1Y3-Pad14)") (class "Default")
      (node (ref "U32") (pin "14") (pinfunction "1Y3_14") (pintype "unspecified+no_connect"))
    )
    (net (code "547") (name "unconnected-(U32-2Y1-Pad9)") (class "Default")
      (node (ref "U32") (pin "9") (pinfunction "2Y1_9") (pintype "unspecified+no_connect"))
    )
    (net (code "548") (name "unconnected-(U32-2Y2-Pad7)") (class "Default")
      (node (ref "U32") (pin "7") (pinfunction "2Y2_7") (pintype "unspecified+no_connect"))
    )
    (net (code "549") (name "unconnected-(U32-2Y3-Pad5)") (class "Default")
      (node (ref "U32") (pin "5") (pinfunction "2Y3_5") (pintype "unspecified+no_connect"))
    )
    (net (code "550") (name "unconnected-(U32-2Y4-Pad3)") (class "Default")
      (node (ref "U32") (pin "3") (pinfunction "2Y4_3") (pintype "unspecified+no_connect"))
    )
  )
)
